# cpu.net
KiCad netlist of a schematic drawn in EAGLE
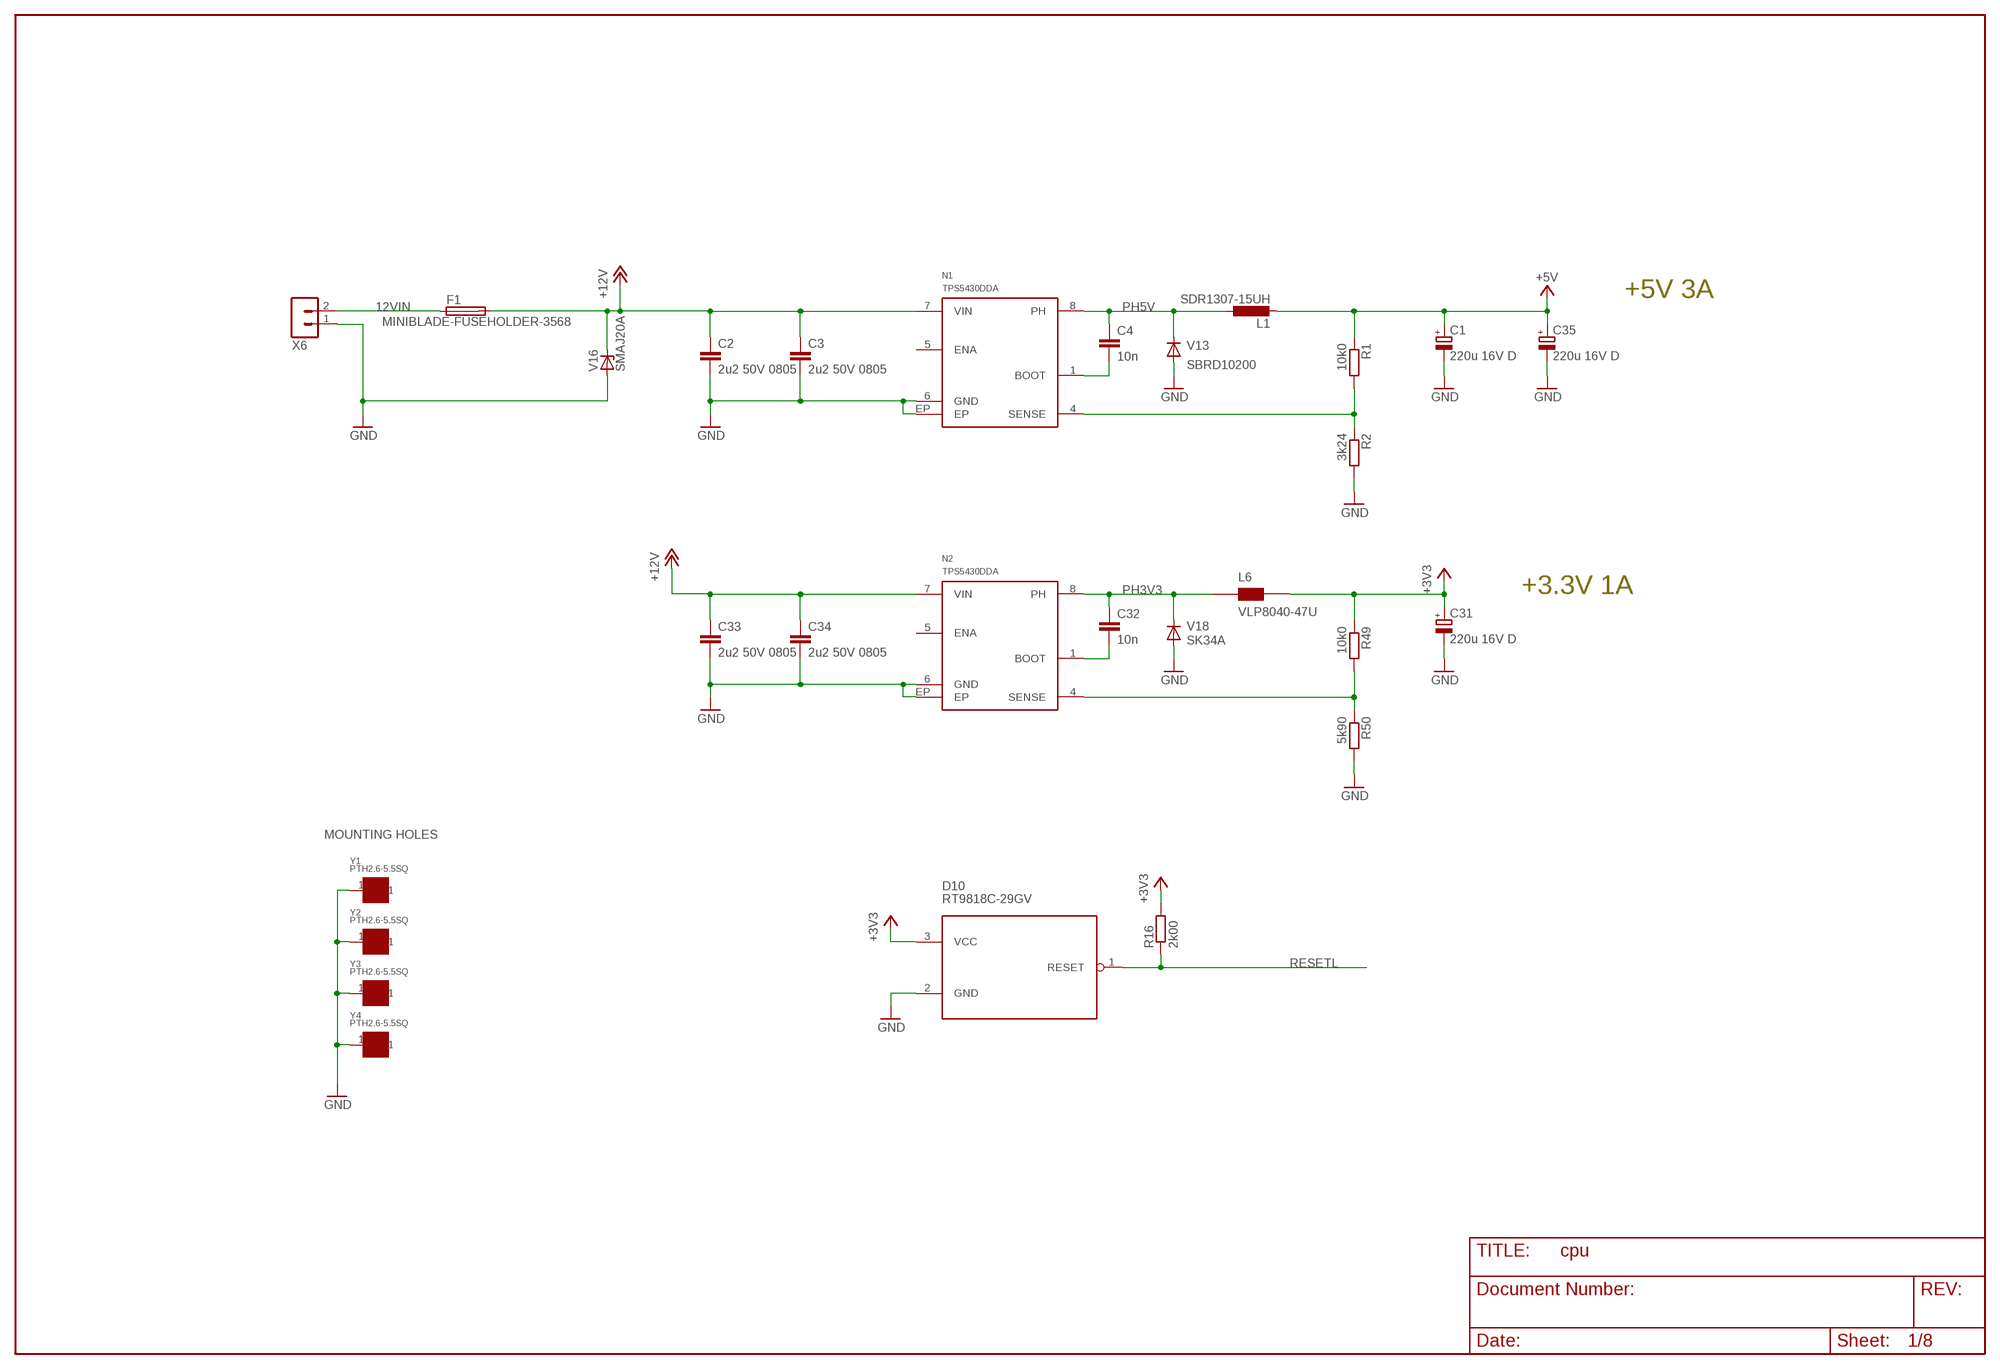
[diagram p0: schematic, sheet 1]
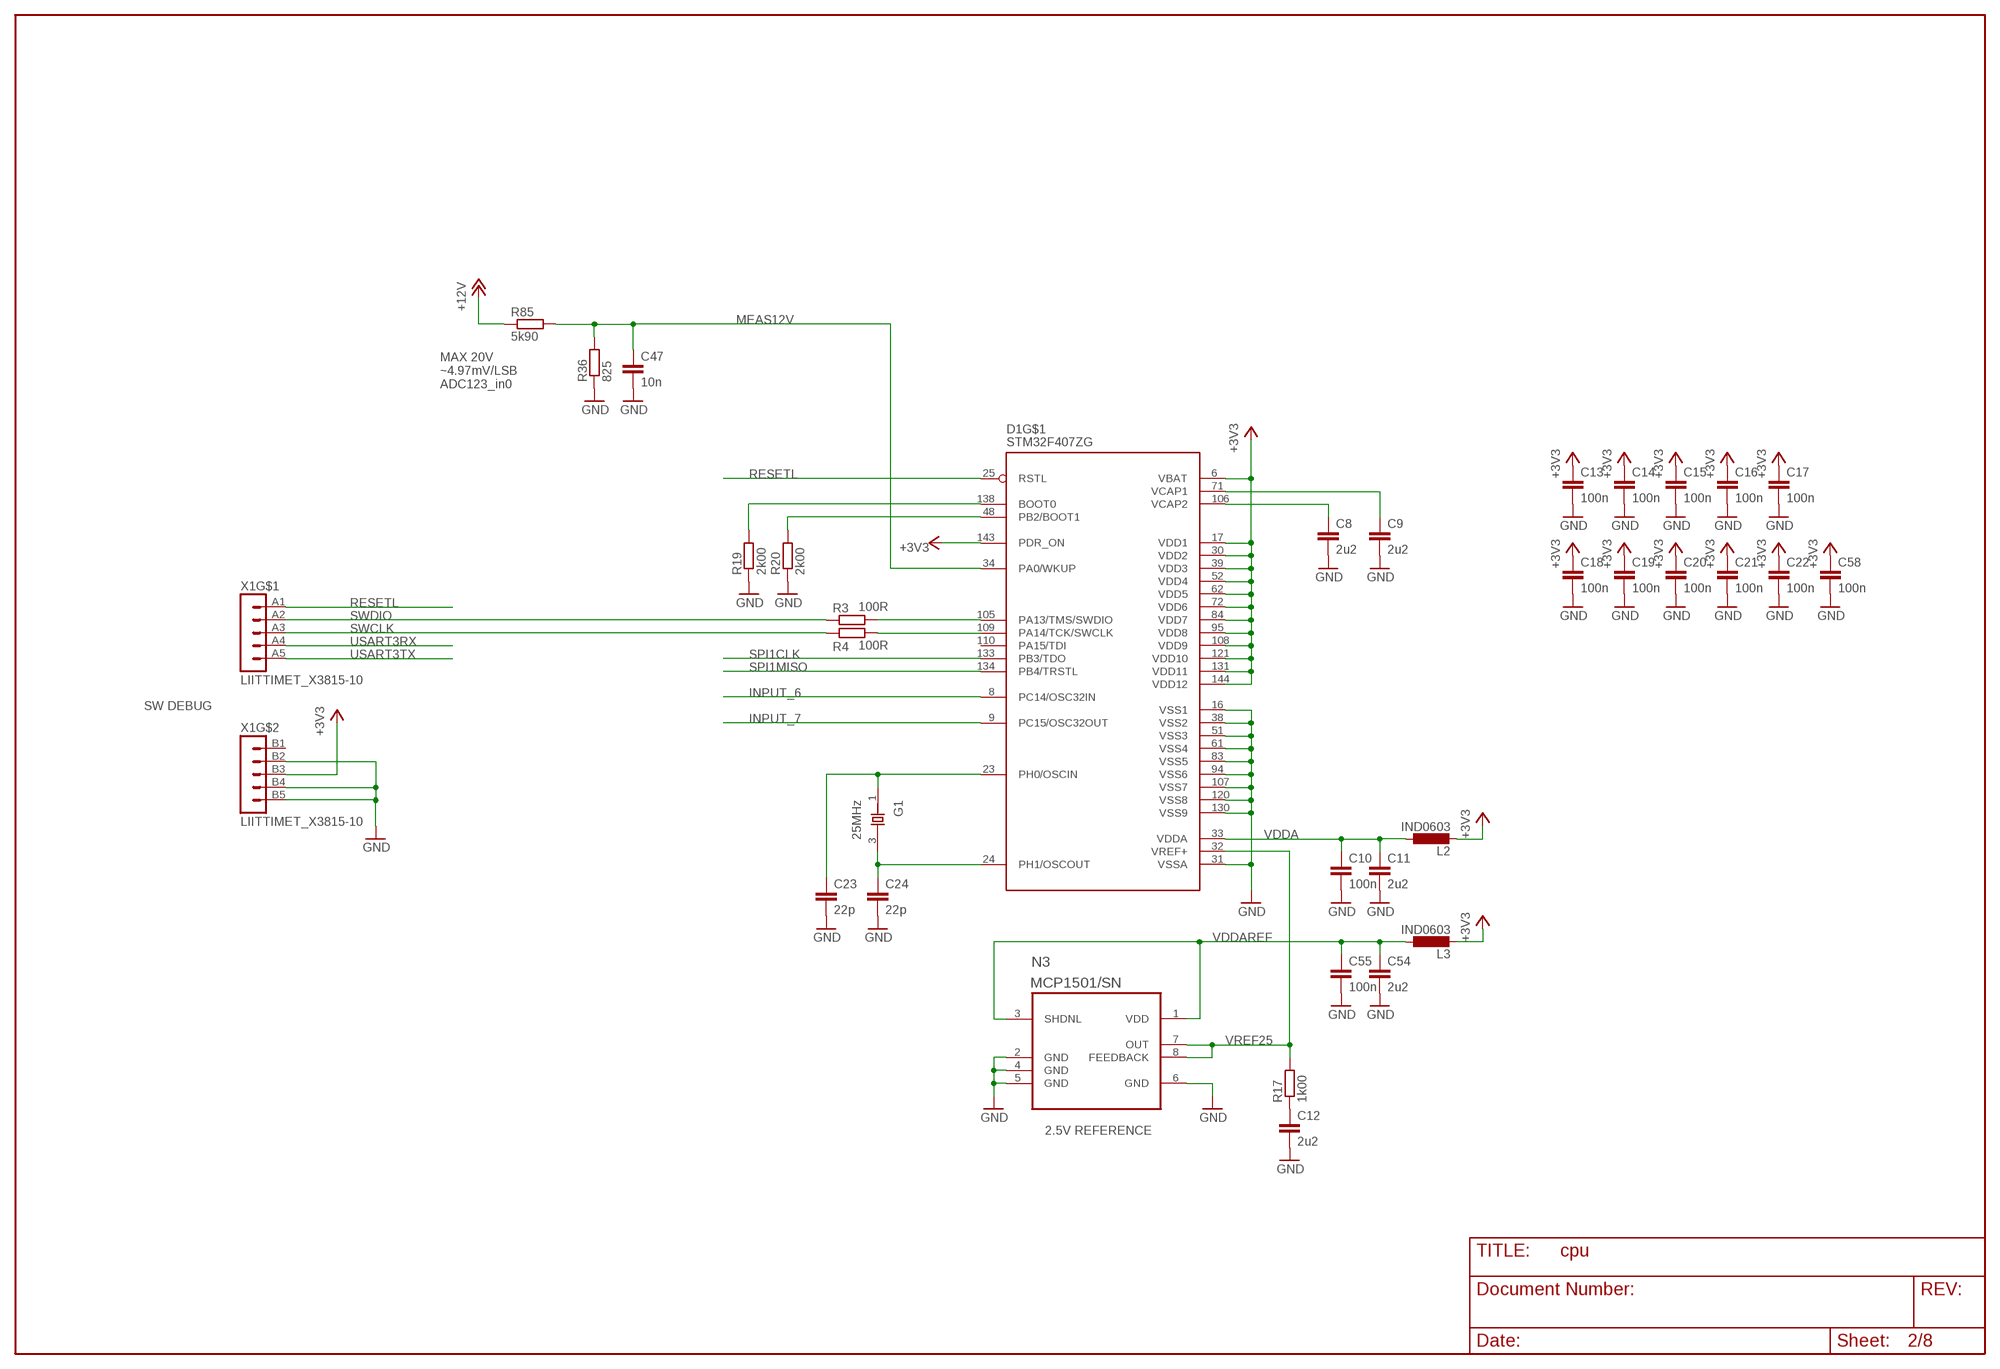
[diagram p1: schematic, sheet 2]
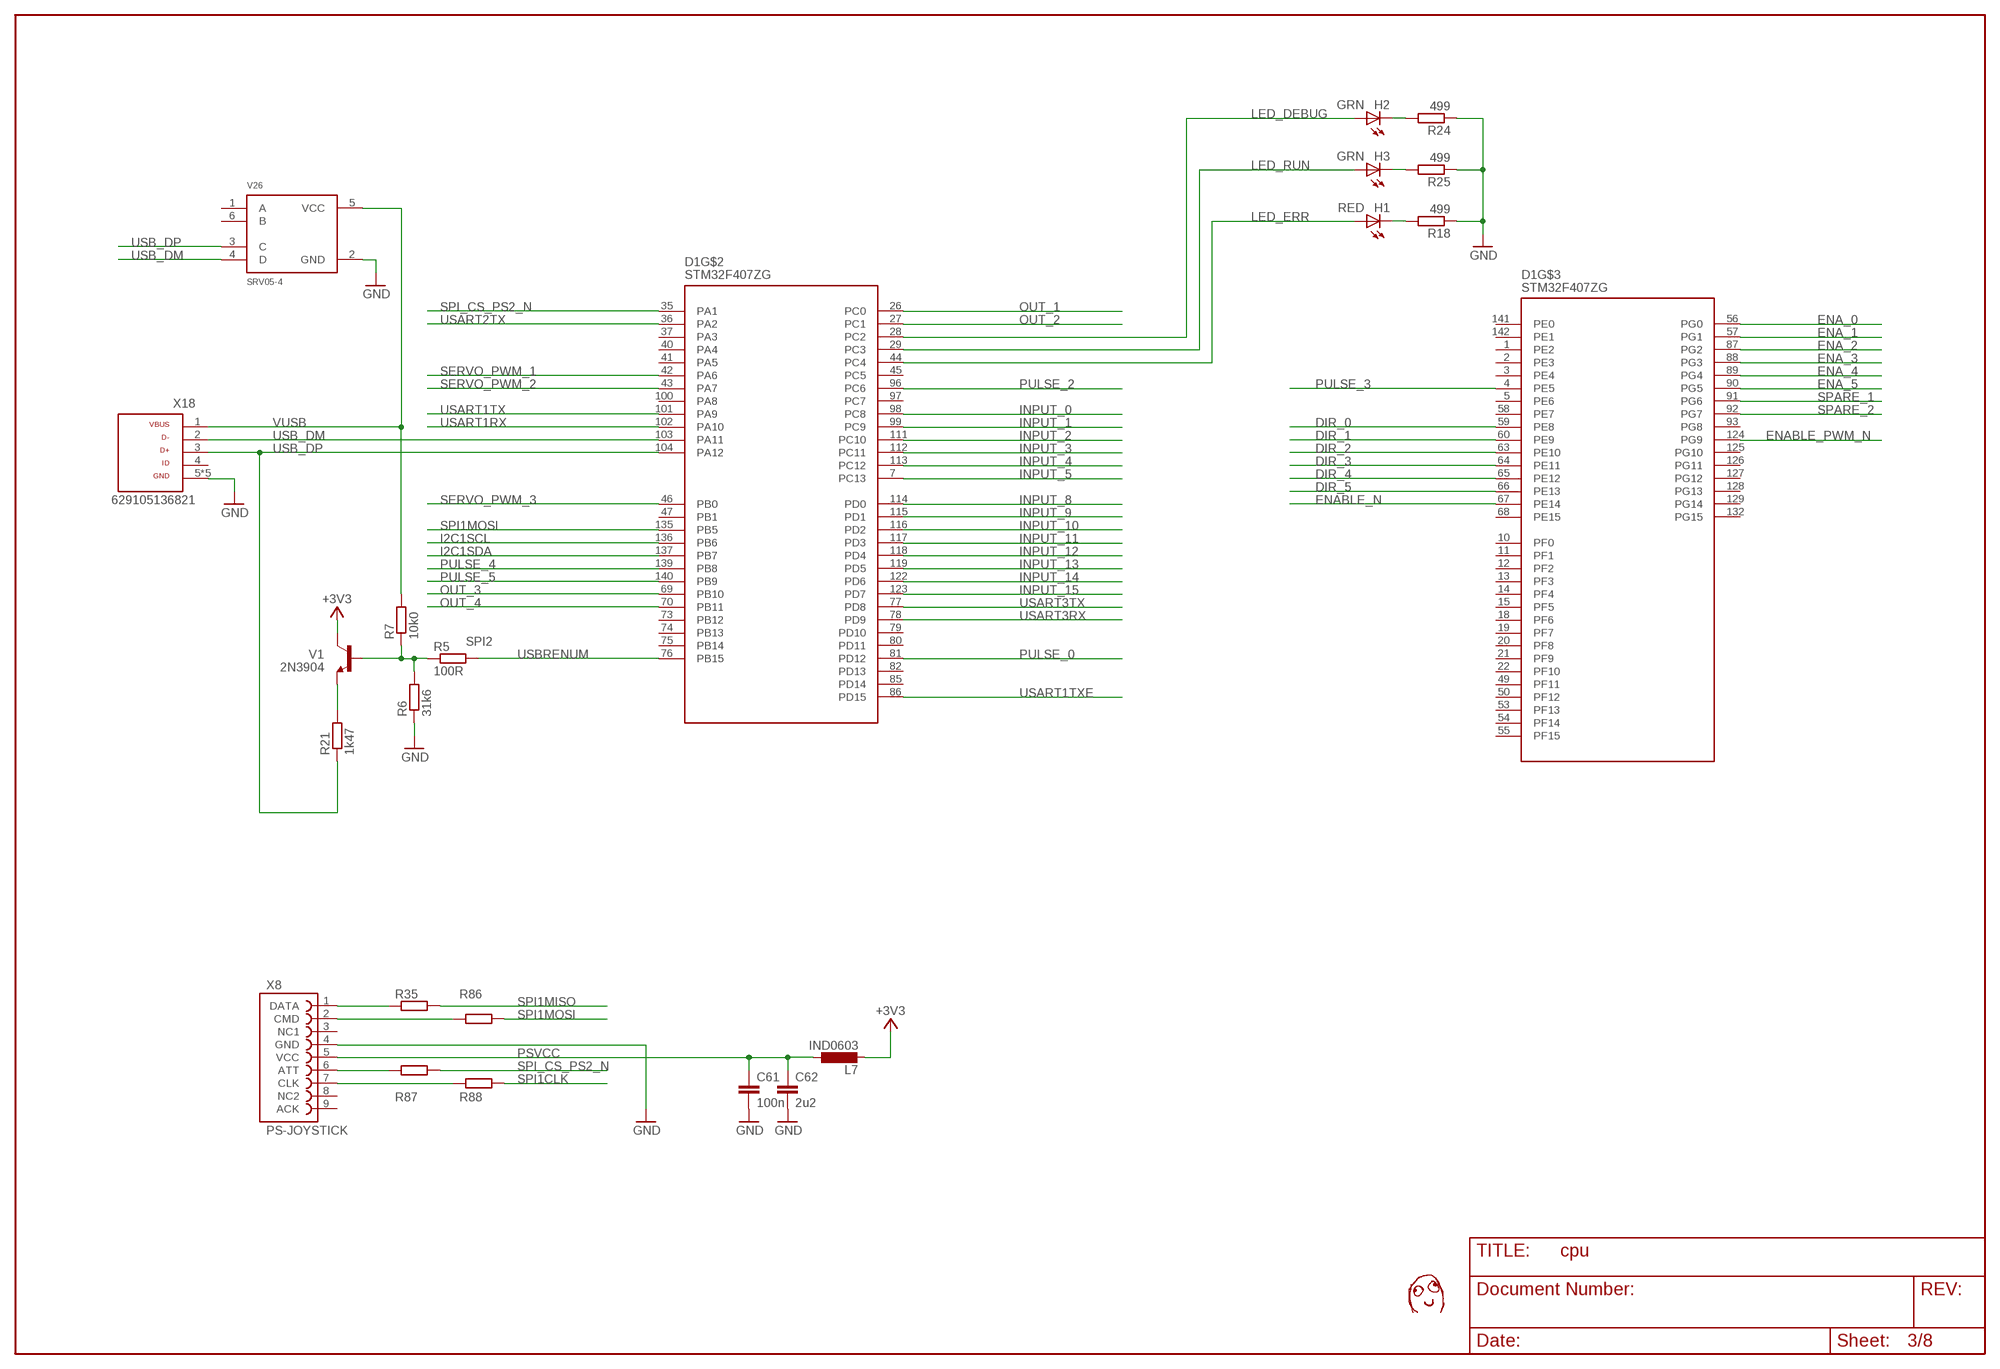
[diagram p2: schematic, sheet 3]
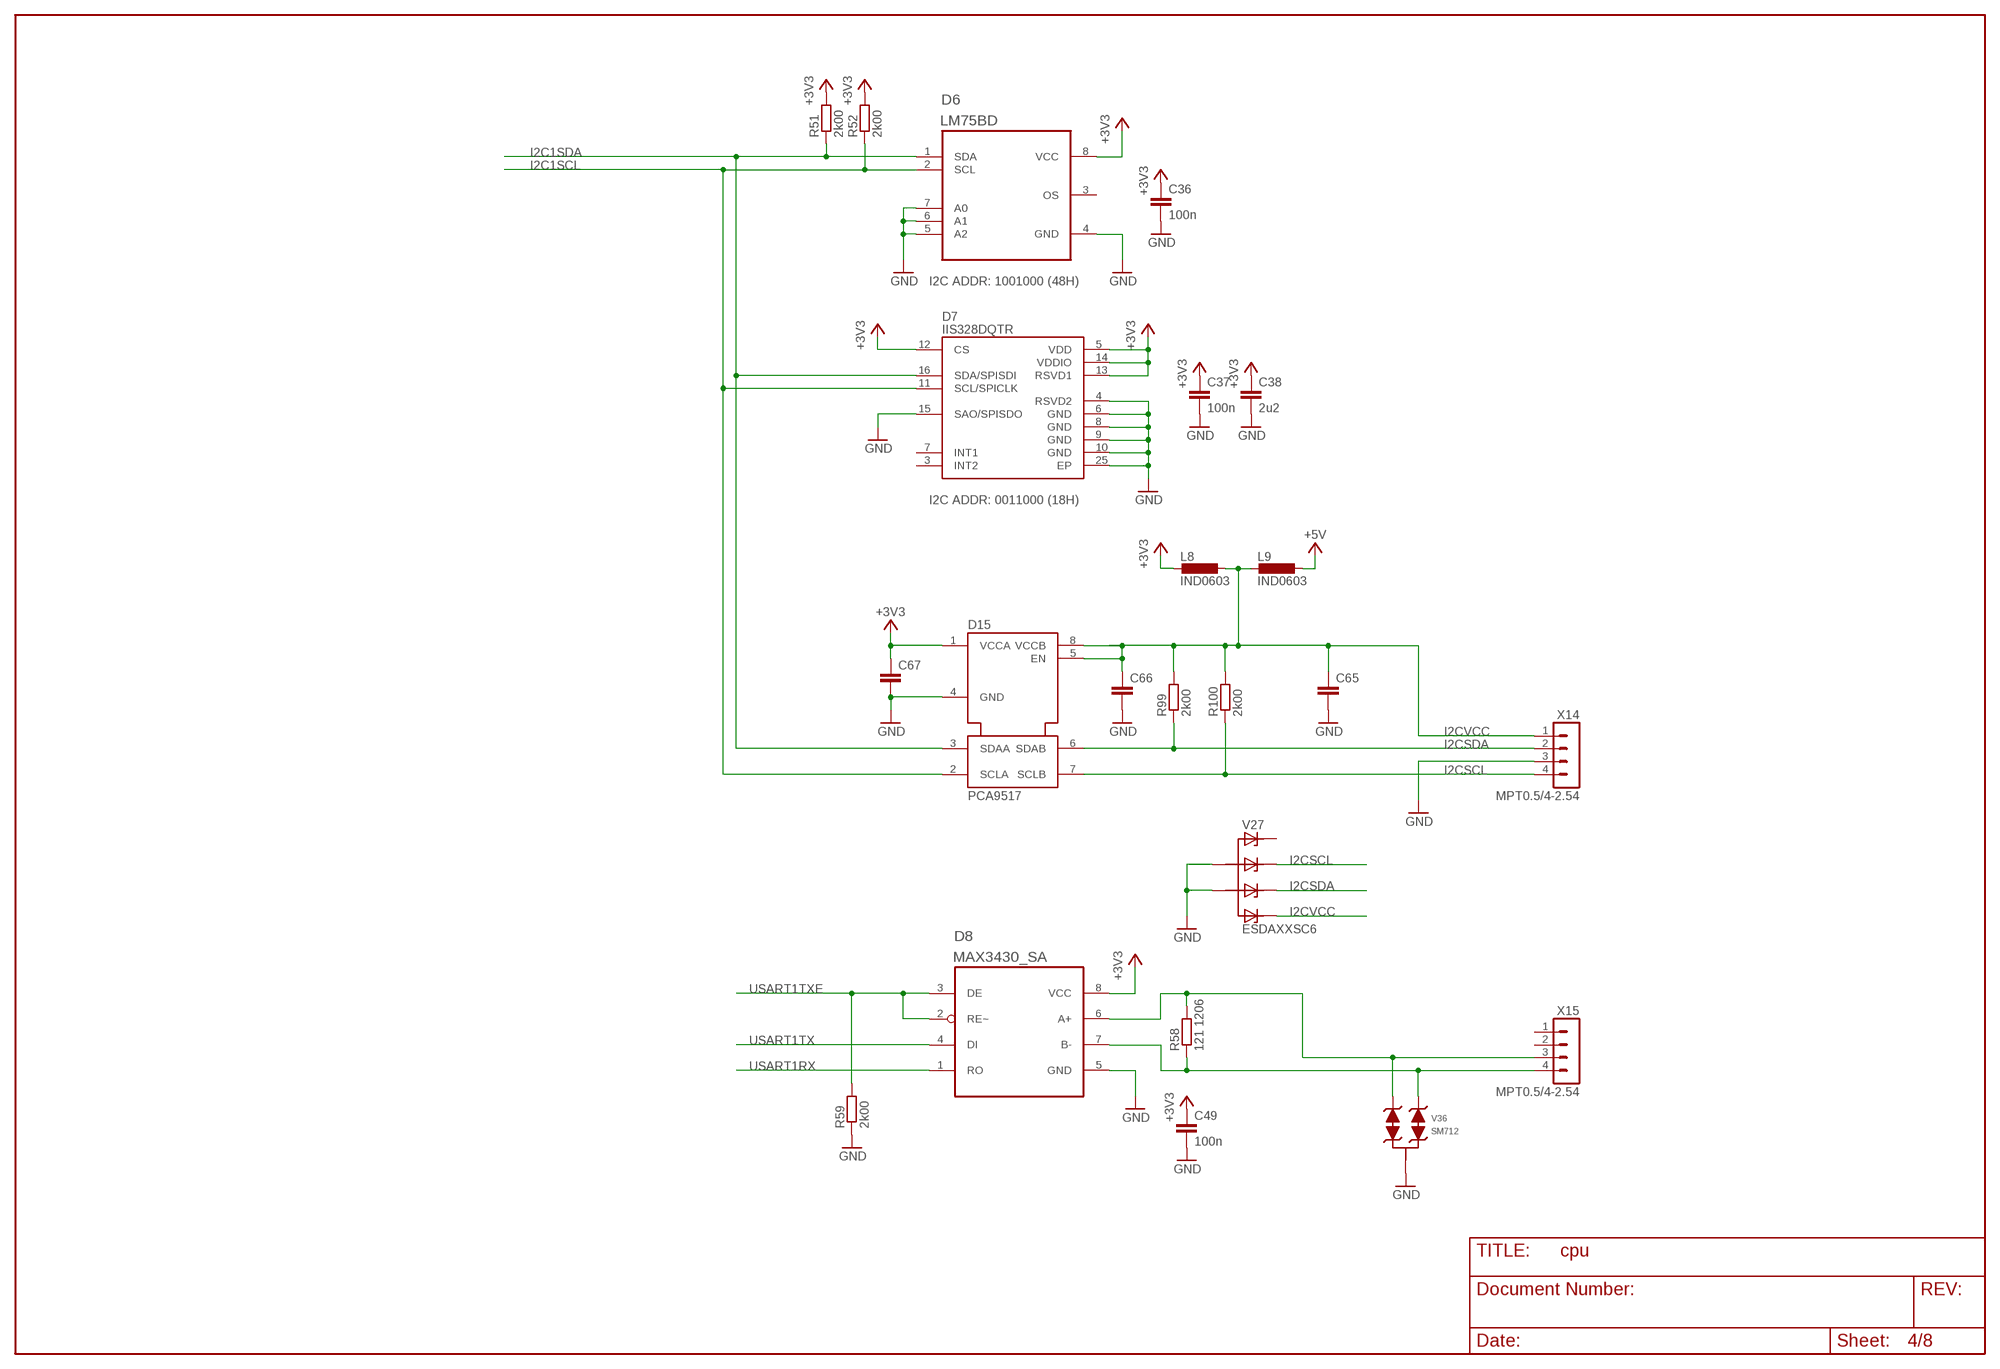
[diagram p3: schematic, sheet 4]
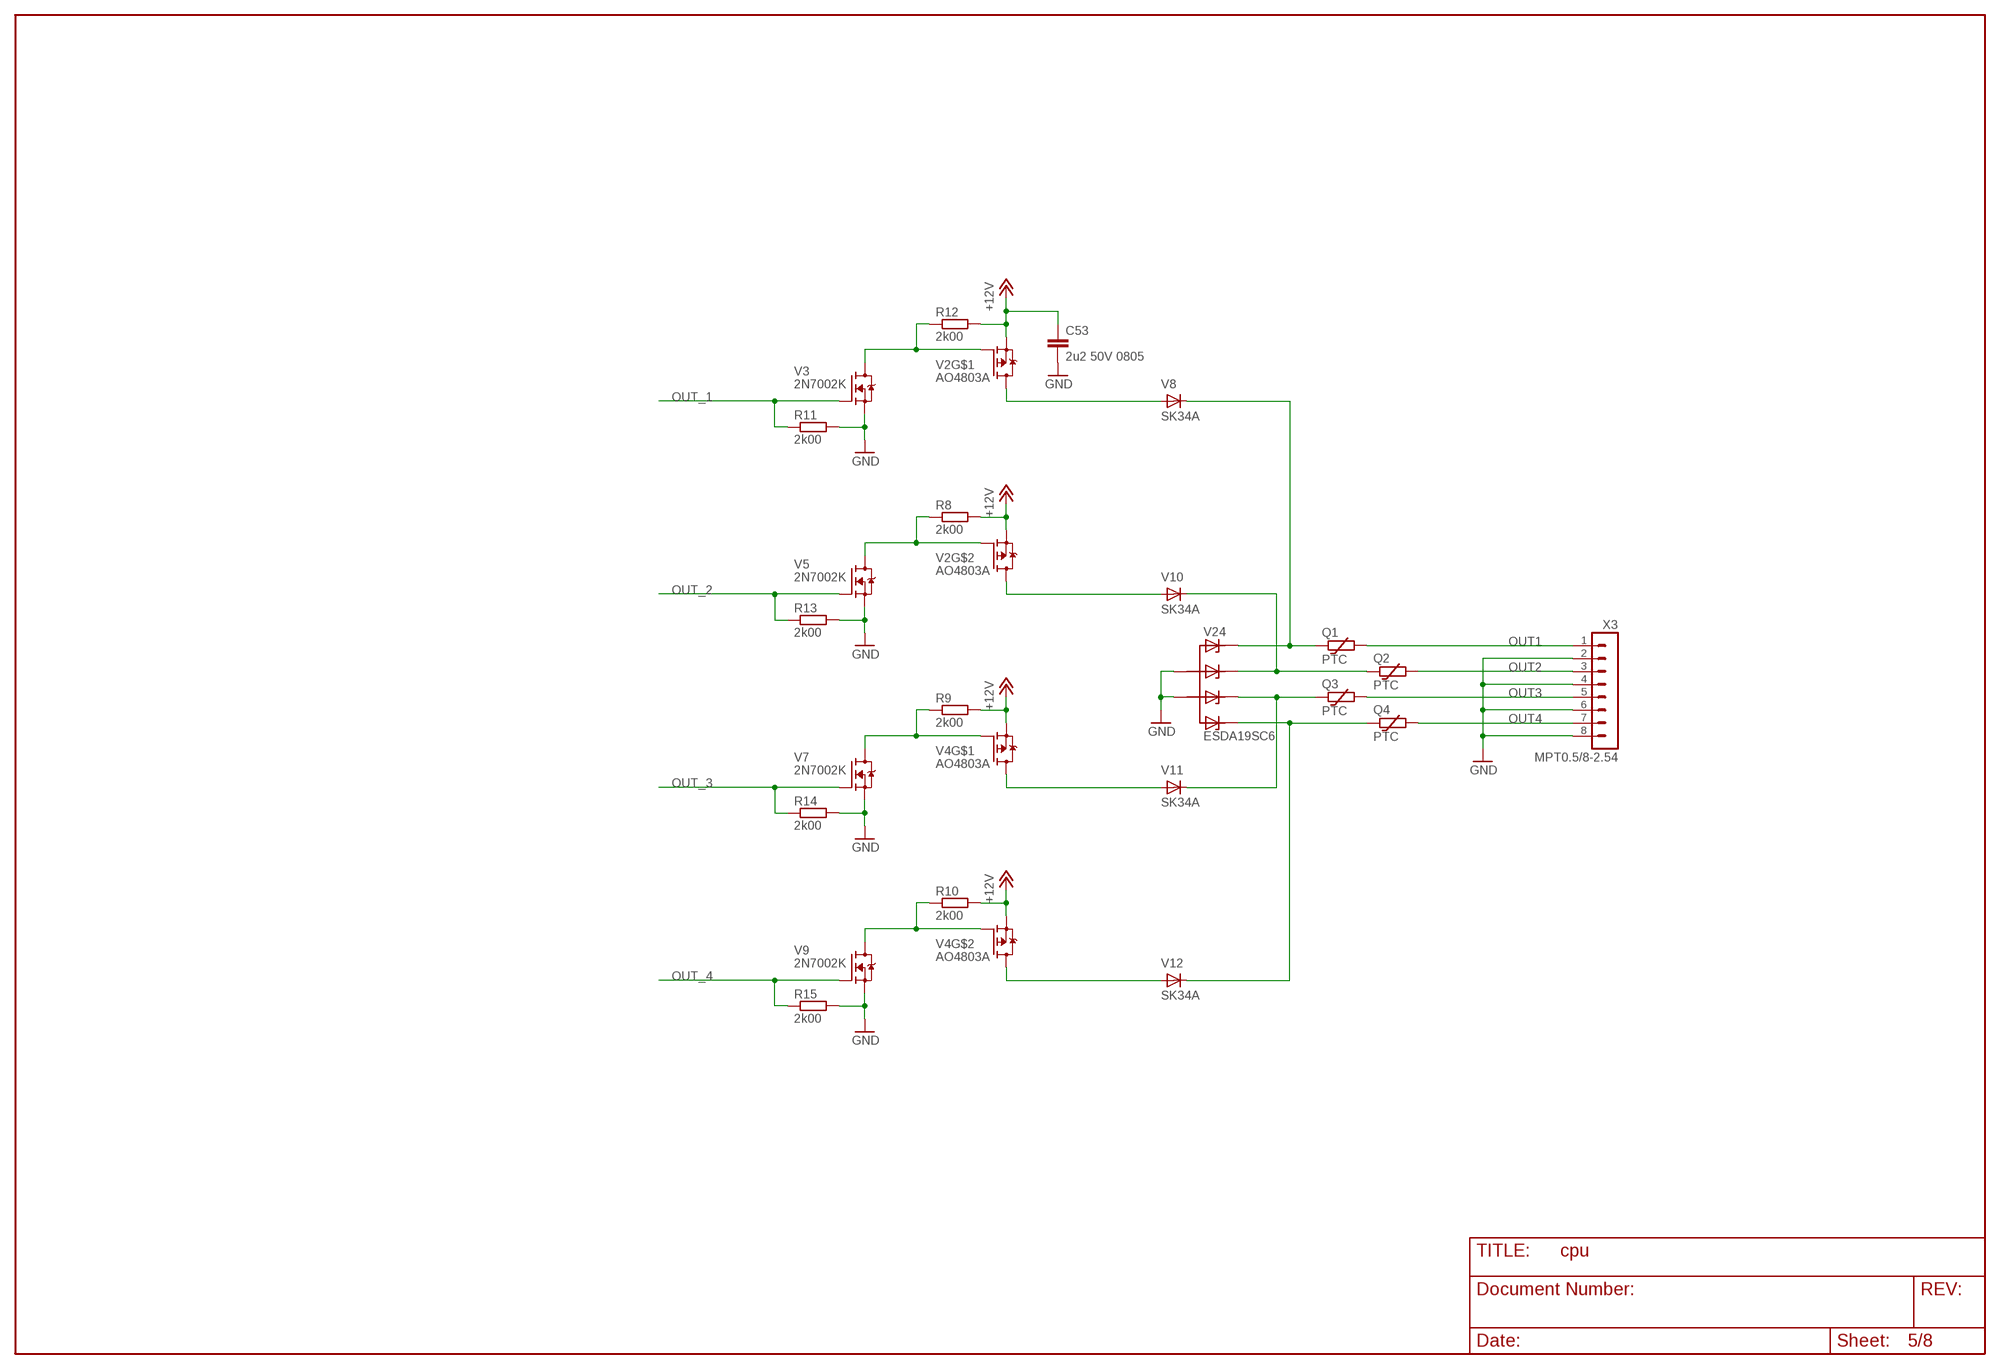
[diagram p4: schematic, sheet 5]
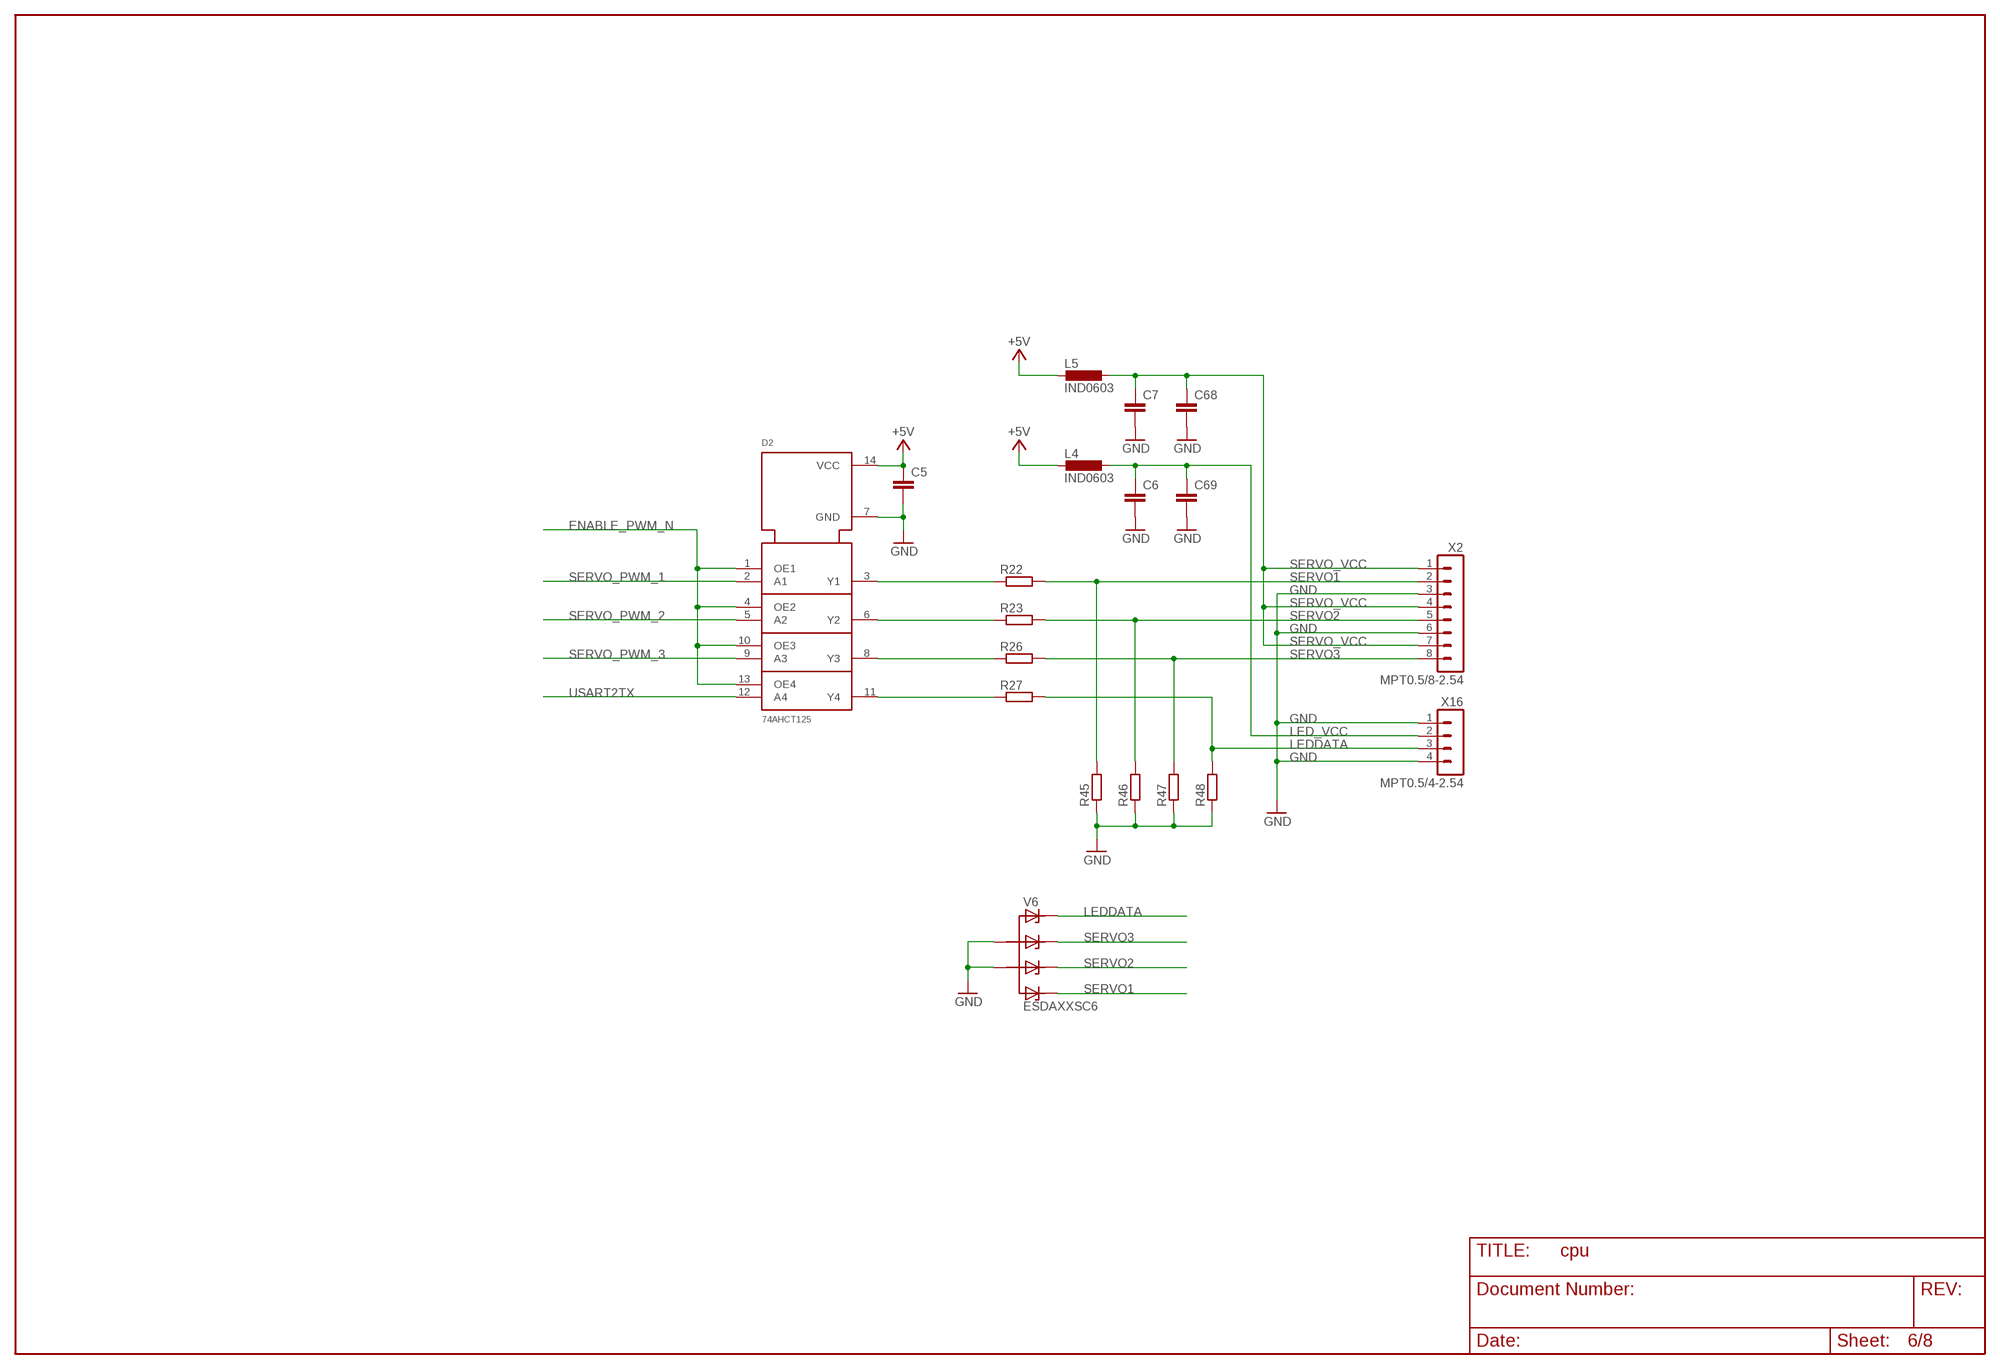
[diagram p5: schematic, sheet 6]
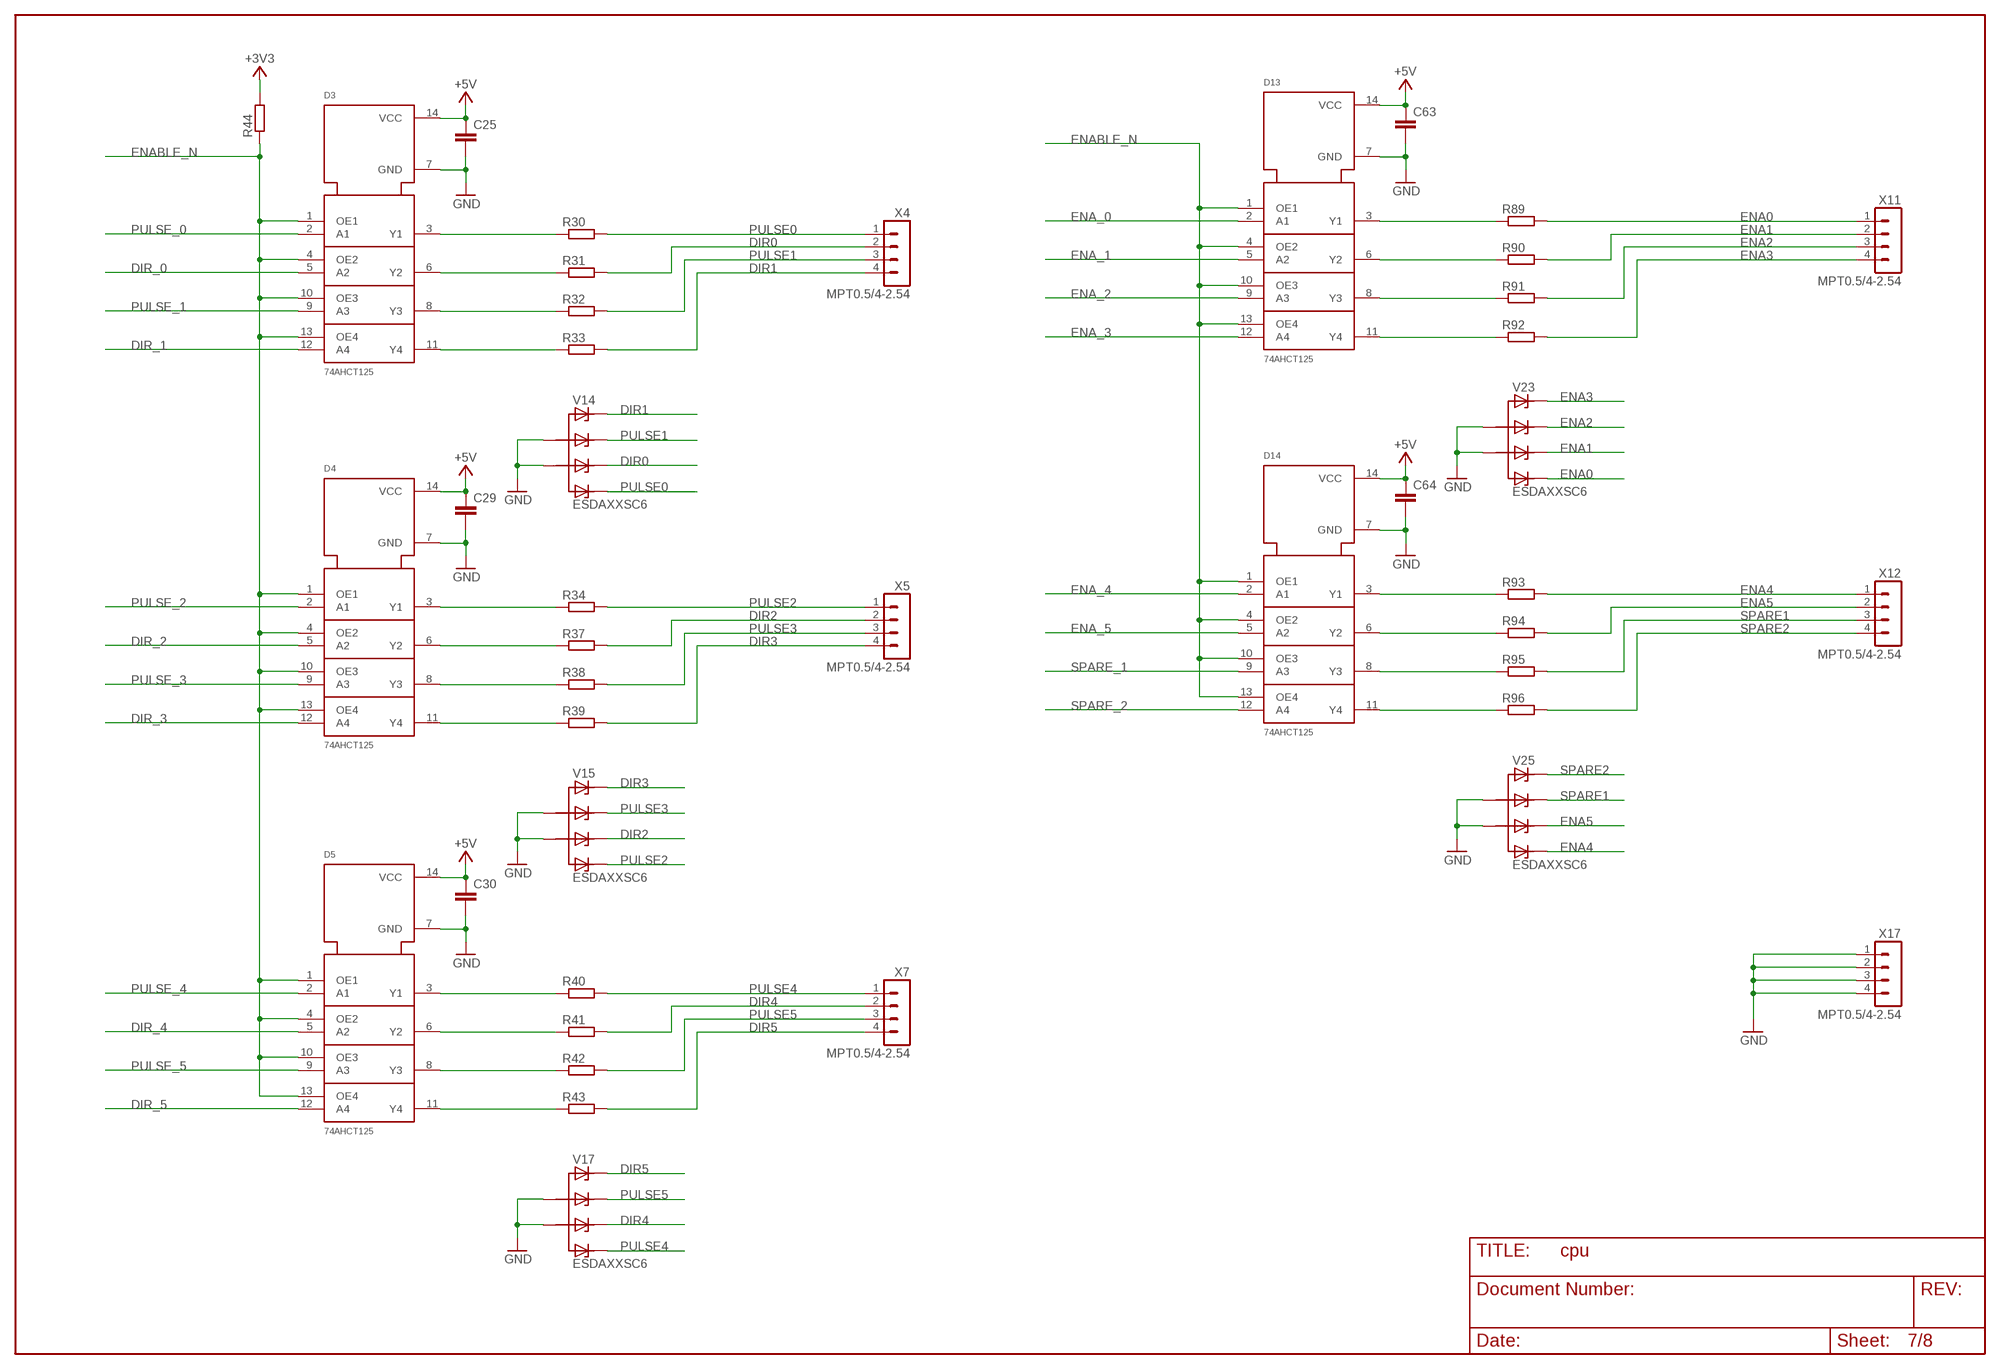
[diagram p6: schematic, sheet 7]
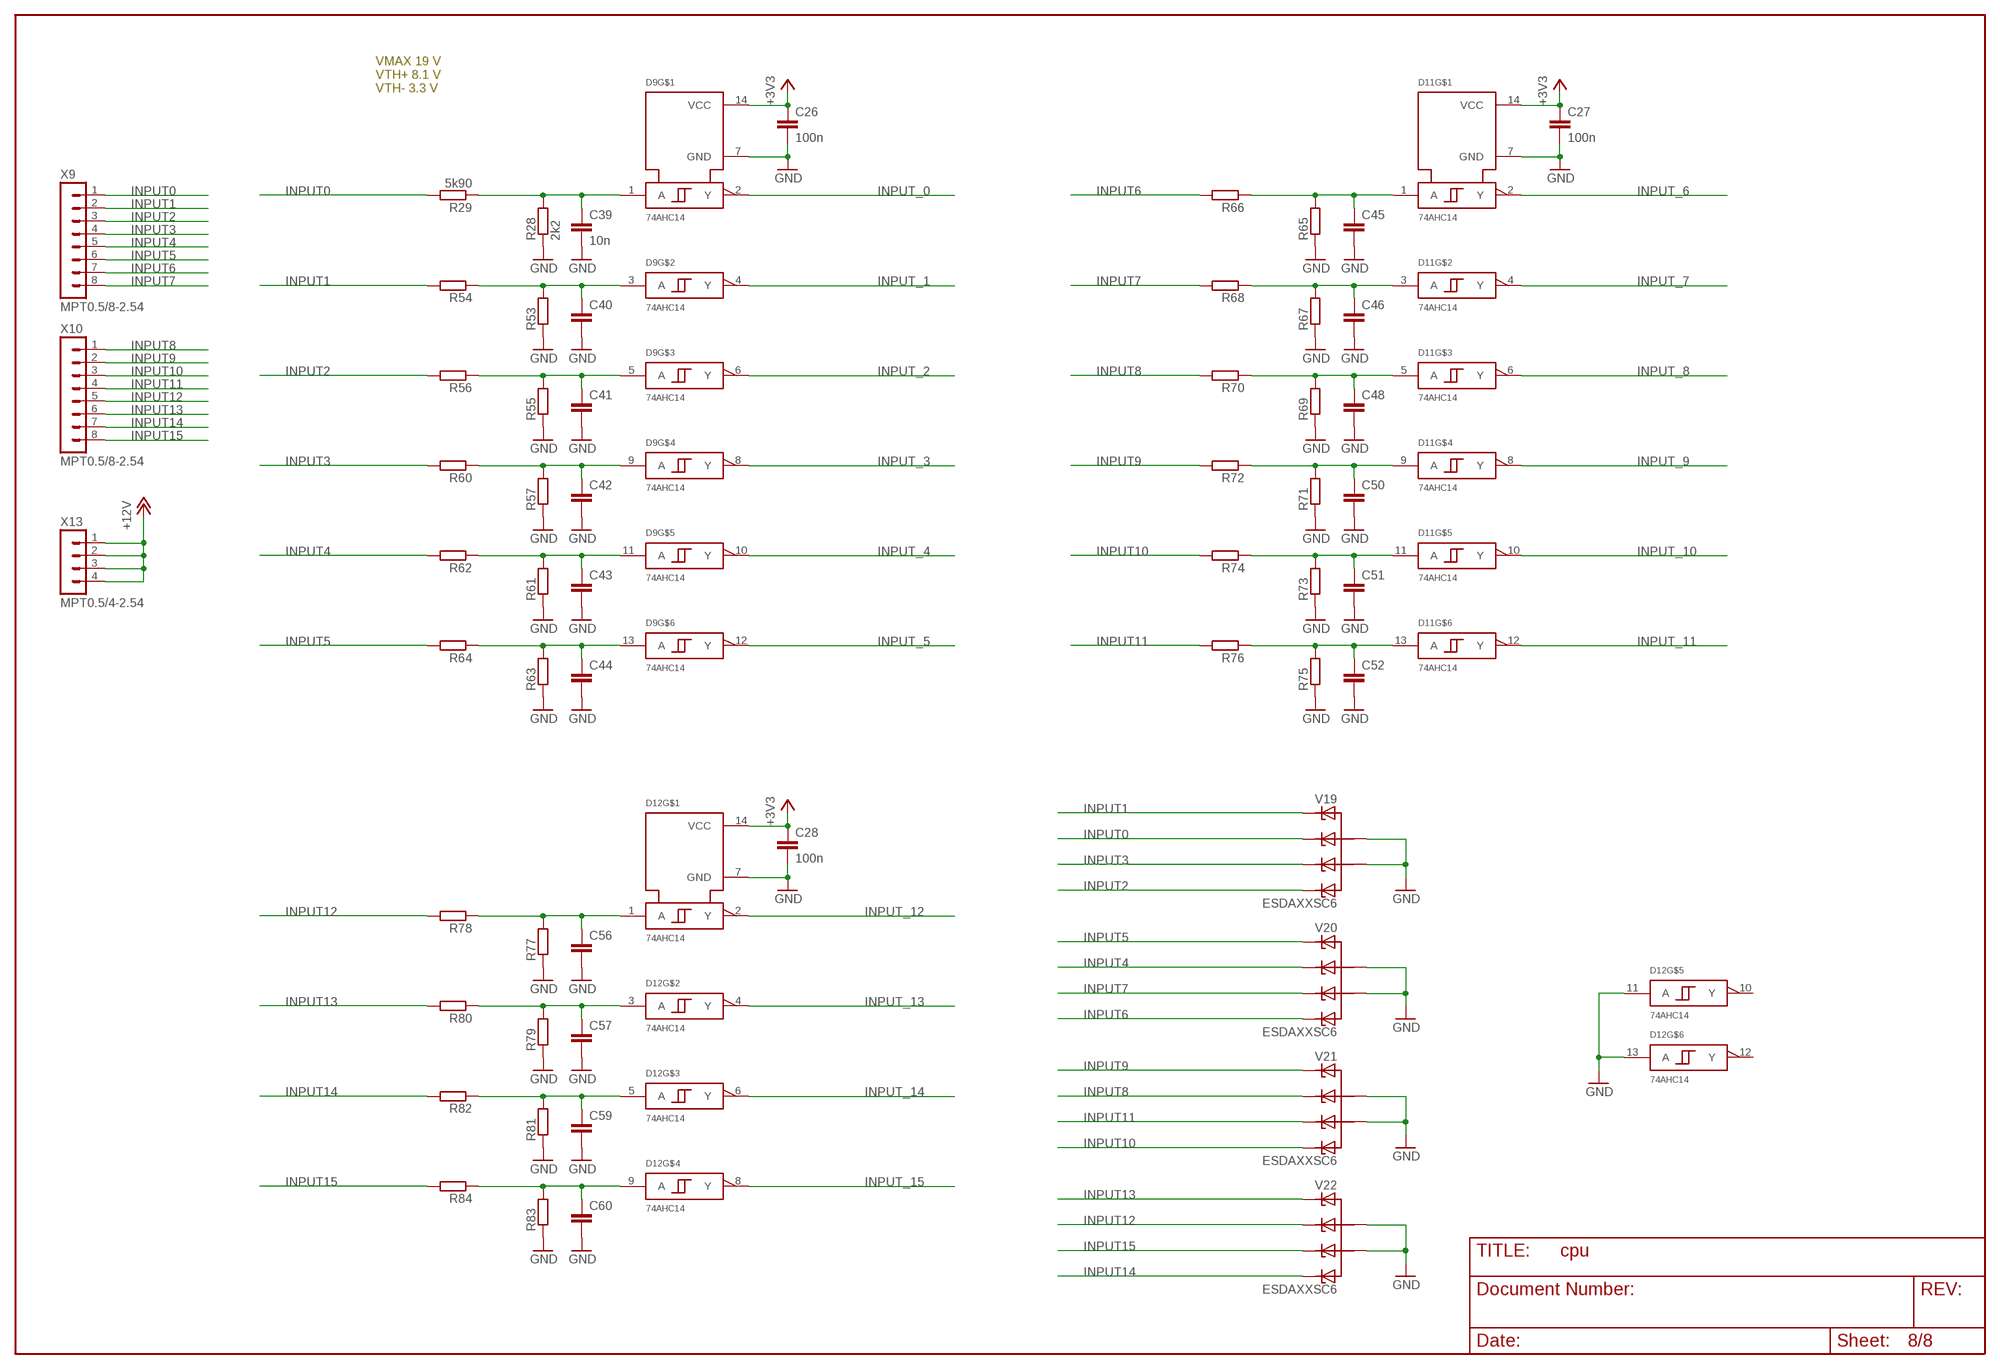
[diagram p7: schematic, sheet 8]

(export (version "E")
  (design (tool "Eeschema 10.0.6"))
  (components
    (comp (ref "C5")
      (value "CAP0603")
      (footprint "eagle-import:OMAT_IC_2_C0603")
      (libsource (lib "eagle-import") (part "CAP0603"))
    )
    (comp (ref "C6")
      (value "CAP0805")
      (footprint "eagle-import:OMAT_IC_2_C0805")
      (libsource (lib "eagle-import") (part "CAP0805"))
    )
    (comp (ref "C7")
      (value "CAP0805")
      (footprint "eagle-import:OMAT_IC_2_C0805")
      (libsource (lib "eagle-import") (part "CAP0805"))
    )
    (comp (ref "C68")
      (value "CAP0805")
      (footprint "eagle-import:OMAT_IC_2_C0805")
      (libsource (lib "eagle-import") (part "CAP0805"))
    )
    (comp (ref "C69")
      (value "CAP0805")
      (footprint "eagle-import:OMAT_IC_2_C0805")
      (libsource (lib "eagle-import") (part "CAP0805"))
    )
    (comp (ref "D2")
      (value "74AHCT125")
      (footprint "eagle-import:SO14")
      (libsource (lib "eagle-import") (part "74AHCT125"))
    )
    (comp (ref "L4")
      (value "IND0603")
      (footprint "eagle-import:OMAT_IC_2_R0603")
      (libsource (lib "eagle-import") (part "IND0603"))
    )
    (comp (ref "L5")
      (value "IND0603")
      (footprint "eagle-import:OMAT_IC_2_R0603")
      (libsource (lib "eagle-import") (part "IND0603"))
    )
    (comp (ref "R22")
      (value "RES0603")
      (footprint "eagle-import:OMAT_IC_2_R0603")
      (libsource (lib "eagle-import") (part "RES0603"))
    )
    (comp (ref "R23")
      (value "RES0603")
      (footprint "eagle-import:OMAT_IC_2_R0603")
      (libsource (lib "eagle-import") (part "RES0603"))
    )
    (comp (ref "R26")
      (value "RES0603")
      (footprint "eagle-import:OMAT_IC_2_R0603")
      (libsource (lib "eagle-import") (part "RES0603"))
    )
    (comp (ref "R27")
      (value "RES0603")
      (footprint "eagle-import:OMAT_IC_2_R0603")
      (libsource (lib "eagle-import") (part "RES0603"))
    )
    (comp (ref "R45")
      (value "RES0603")
      (footprint "eagle-import:OMAT_IC_2_R0603")
      (libsource (lib "eagle-import") (part "RES0603"))
    )
    (comp (ref "R46")
      (value "RES0603")
      (footprint "eagle-import:OMAT_IC_2_R0603")
      (libsource (lib "eagle-import") (part "RES0603"))
    )
    (comp (ref "R47")
      (value "RES0603")
      (footprint "eagle-import:OMAT_IC_2_R0603")
      (libsource (lib "eagle-import") (part "RES0603"))
    )
    (comp (ref "R48")
      (value "RES0603")
      (footprint "eagle-import:OMAT_IC_2_R0603")
      (libsource (lib "eagle-import") (part "RES0603"))
    )
    (comp (ref "V6")
      (value "ESDAXXSC6")
      (footprint "eagle-import:OMAT_IC_2_SOT23-6")
      (libsource (lib "eagle-import") (part "ESDAXXSC6"))
    )
    (comp (ref "X2")
      (value "MPT0.5/8-2.54")
      (footprint "eagle-import:OMAT_IC_2_MPT0.5_8-2.54")
      (libsource (lib "eagle-import") (part "MPT0.5/8-2.54"))
    )
    (comp (ref "X16")
      (value "MPT0.5/4-2.54")
      (footprint "eagle-import:MPT0.5_4-2.54")
      (libsource (lib "eagle-import") (part "MPT0.5/4-2.54"))
    )
    (comp (ref "C8")
      (value "2u2")
      (footprint "eagle-import:C0603")
      (libsource (lib "eagle-import") (part "omat_ic_2_CAP0603"))
    )
    (comp (ref "C9")
      (value "2u2")
      (footprint "eagle-import:C0603")
      (libsource (lib "eagle-import") (part "omat_ic_2_CAP0603"))
    )
    (comp (ref "C10")
      (value "100n")
      (footprint "eagle-import:C0603")
      (libsource (lib "eagle-import") (part "omat_ic_2_CAP0603"))
    )
    (comp (ref "C11")
      (value "2u2")
      (footprint "eagle-import:C0603")
      (libsource (lib "eagle-import") (part "omat_ic_2_CAP0603"))
    )
    (comp (ref "C12")
      (value "2u2")
      (footprint "eagle-import:C0603")
      (libsource (lib "eagle-import") (part "omat_ic_2_CAP0603"))
    )
    (comp (ref "C13")
      (value "100n")
      (footprint "eagle-import:C0603")
      (libsource (lib "eagle-import") (part "omat_ic_2_CAP0603"))
    )
    (comp (ref "C14")
      (value "100n")
      (footprint "eagle-import:C0603")
      (libsource (lib "eagle-import") (part "omat_ic_2_CAP0603"))
    )
    (comp (ref "C15")
      (value "100n")
      (footprint "eagle-import:C0603")
      (libsource (lib "eagle-import") (part "omat_ic_2_CAP0603"))
    )
    (comp (ref "C16")
      (value "100n")
      (footprint "eagle-import:C0603")
      (libsource (lib "eagle-import") (part "omat_ic_2_CAP0603"))
    )
    (comp (ref "C17")
      (value "100n")
      (footprint "eagle-import:C0603")
      (libsource (lib "eagle-import") (part "omat_ic_2_CAP0603"))
    )
    (comp (ref "C18")
      (value "100n")
      (footprint "eagle-import:C0603")
      (libsource (lib "eagle-import") (part "omat_ic_2_CAP0603"))
    )
    (comp (ref "C19")
      (value "100n")
      (footprint "eagle-import:C0603")
      (libsource (lib "eagle-import") (part "omat_ic_2_CAP0603"))
    )
    (comp (ref "C20")
      (value "100n")
      (footprint "eagle-import:C0603")
      (libsource (lib "eagle-import") (part "omat_ic_2_CAP0603"))
    )
    (comp (ref "C21")
      (value "100n")
      (footprint "eagle-import:C0603")
      (libsource (lib "eagle-import") (part "omat_ic_2_CAP0603"))
    )
    (comp (ref "C22")
      (value "100n")
      (footprint "eagle-import:C0603")
      (libsource (lib "eagle-import") (part "omat_ic_2_CAP0603"))
    )
    (comp (ref "C23")
      (value "22p")
      (footprint "eagle-import:C0603")
      (libsource (lib "eagle-import") (part "omat_ic_2_CAP0603"))
    )
    (comp (ref "C24")
      (value "22p")
      (footprint "eagle-import:C0603")
      (libsource (lib "eagle-import") (part "omat_ic_2_CAP0603"))
    )
    (comp (ref "C47")
      (value "10n")
      (footprint "eagle-import:C0603")
      (libsource (lib "eagle-import") (part "omat_ic_2_CAP0603"))
    )
    (comp (ref "C54")
      (value "2u2")
      (footprint "eagle-import:C0603")
      (libsource (lib "eagle-import") (part "omat_ic_2_CAP0603"))
    )
    (comp (ref "C55")
      (value "100n")
      (footprint "eagle-import:C0603")
      (libsource (lib "eagle-import") (part "omat_ic_2_CAP0603"))
    )
    (comp (ref "C58")
      (value "100n")
      (footprint "eagle-import:C0603")
      (libsource (lib "eagle-import") (part "omat_ic_2_CAP0603"))
    )
    (comp (ref "D1")
      (value "STM32F407ZG")
      (footprint "eagle-import:LQFP-144")
      (libsource (lib "eagle-import") (part "STM32F407ZG"))
    )
    (comp (ref "G1")
      (value "25MHz")
      (footprint "eagle-import:X_3225")
      (libsource (lib "eagle-import") (part "XTAL_3225_SMD"))
    )
    (comp (ref "L2")
      (value "IND0603")
      (footprint "eagle-import:R0603")
      (libsource (lib "eagle-import") (part "omat_ic_2_IND0603"))
    )
    (comp (ref "L3")
      (value "IND0603")
      (footprint "eagle-import:R0603")
      (libsource (lib "eagle-import") (part "omat_ic_2_IND0603"))
    )
    (comp (ref "N3")
      (value "MCP1501/SN")
      (footprint "eagle-import:SOIC8-N_MC")
      (libsource (lib "eagle-import") (part "MCP1501/SN"))
    )
    (comp (ref "R3")
      (value "100R")
      (footprint "eagle-import:PASSIIVIT_R0603")
      (libsource (lib "eagle-import") (part "PASSIIVIT_RES0603"))
    )
    (comp (ref "R4")
      (value "100R")
      (footprint "eagle-import:PASSIIVIT_R0603")
      (libsource (lib "eagle-import") (part "PASSIIVIT_RES0603"))
    )
    (comp (ref "R17")
      (value "1k00")
      (footprint "eagle-import:R0603")
      (libsource (lib "eagle-import") (part "omat_ic_2_RES0603"))
    )
    (comp (ref "R19")
      (value "2k00")
      (footprint "eagle-import:R0603")
      (libsource (lib "eagle-import") (part "omat_ic_2_RES0603"))
    )
    (comp (ref "R20")
      (value "2k00")
      (footprint "eagle-import:R0603")
      (libsource (lib "eagle-import") (part "omat_ic_2_RES0603"))
    )
    (comp (ref "R36")
      (value "825")
      (footprint "eagle-import:R0603")
      (libsource (lib "eagle-import") (part "omat_ic_2_RES0603"))
    )
    (comp (ref "R85")
      (value "5k90")
      (footprint "eagle-import:R0603")
      (libsource (lib "eagle-import") (part "omat_ic_2_RES0603"))
    )
    (comp (ref "X1")
      (value "LIITTIMET_X3815-10")
      (footprint "eagle-import:LIITTIMET_15110102601")
      (libsource (lib "eagle-import") (part "LIITTIMET_X3815-10"))
    )
    (comp (ref "C53")
      (value "2u2 50V 0805")
      (footprint "eagle-import:C0805")
      (libsource (lib "eagle-import") (part "omat_ic_2_CAP0805"))
    )
    (comp (ref "Q1")
      (value "PTC")
      (footprint "eagle-import:OMAT_IC_2_R1812")
      (libsource (lib "eagle-import") (part "PTC"))
    )
    (comp (ref "Q2")
      (value "PTC")
      (footprint "eagle-import:OMAT_IC_2_R1812")
      (libsource (lib "eagle-import") (part "PTC"))
    )
    (comp (ref "Q3")
      (value "PTC")
      (footprint "eagle-import:OMAT_IC_2_R1812")
      (libsource (lib "eagle-import") (part "PTC"))
    )
    (comp (ref "Q4")
      (value "PTC")
      (footprint "eagle-import:OMAT_IC_2_R1812")
      (libsource (lib "eagle-import") (part "PTC"))
    )
    (comp (ref "R8")
      (value "2k00")
      (footprint "eagle-import:R0603")
      (libsource (lib "eagle-import") (part "omat_ic_2_RES0603"))
    )
    (comp (ref "R9")
      (value "2k00")
      (footprint "eagle-import:R0603")
      (libsource (lib "eagle-import") (part "omat_ic_2_RES0603"))
    )
    (comp (ref "R10")
      (value "2k00")
      (footprint "eagle-import:R0603")
      (libsource (lib "eagle-import") (part "omat_ic_2_RES0603"))
    )
    (comp (ref "R11")
      (value "2k00")
      (footprint "eagle-import:R0603")
      (libsource (lib "eagle-import") (part "omat_ic_2_RES0603"))
    )
    (comp (ref "R12")
      (value "2k00")
      (footprint "eagle-import:R0603")
      (libsource (lib "eagle-import") (part "omat_ic_2_RES0603"))
    )
    (comp (ref "R13")
      (value "2k00")
      (footprint "eagle-import:R0603")
      (libsource (lib "eagle-import") (part "omat_ic_2_RES0603"))
    )
    (comp (ref "R14")
      (value "2k00")
      (footprint "eagle-import:R0603")
      (libsource (lib "eagle-import") (part "omat_ic_2_RES0603"))
    )
    (comp (ref "R15")
      (value "2k00")
      (footprint "eagle-import:R0603")
      (libsource (lib "eagle-import") (part "omat_ic_2_RES0603"))
    )
    (comp (ref "V2")
      (value "AO4803A")
      (footprint "eagle-import:SOIC8-N_MC")
      (libsource (lib "eagle-import") (part "AO4803A"))
    )
    (comp (ref "V3")
      (value "2N7002K")
      (footprint "eagle-import:SOT23")
      (libsource (lib "eagle-import") (part "2N7002K"))
    )
    (comp (ref "V4")
      (value "AO4803A")
      (footprint "eagle-import:SOIC8-N_MC")
      (libsource (lib "eagle-import") (part "AO4803A"))
    )
    (comp (ref "V5")
      (value "2N7002K")
      (footprint "eagle-import:SOT23")
      (libsource (lib "eagle-import") (part "2N7002K"))
    )
    (comp (ref "V7")
      (value "2N7002K")
      (footprint "eagle-import:SOT23")
      (libsource (lib "eagle-import") (part "2N7002K"))
    )
    (comp (ref "V8")
      (value "SK34A")
      (footprint "eagle-import:DO214AC")
      (libsource (lib "eagle-import") (part "SK34A"))
    )
    (comp (ref "V9")
      (value "2N7002K")
      (footprint "eagle-import:SOT23")
      (libsource (lib "eagle-import") (part "2N7002K"))
    )
    (comp (ref "V10")
      (value "SK34A")
      (footprint "eagle-import:DO214AC")
      (libsource (lib "eagle-import") (part "SK34A"))
    )
    (comp (ref "V11")
      (value "SK34A")
      (footprint "eagle-import:DO214AC")
      (libsource (lib "eagle-import") (part "SK34A"))
    )
    (comp (ref "V12")
      (value "SK34A")
      (footprint "eagle-import:DO214AC")
      (libsource (lib "eagle-import") (part "SK34A"))
    )
    (comp (ref "V24")
      (value "ESDA19SC6")
      (footprint "eagle-import:SOT23-6")
      (libsource (lib "eagle-import") (part "omat_ic_2_ESDAXXSC6"))
    )
    (comp (ref "X3")
      (value "MPT0.5/8-2.54")
      (footprint "eagle-import:MPT0.5_8-2.54")
      (libsource (lib "eagle-import") (part "omat_ic_2_MPT0.5/8-2.54"))
    )
    (comp (ref "C26")
      (value "100n")
      (footprint "eagle-import:C0603")
      (libsource (lib "eagle-import") (part "omat_ic_2_CAP0603"))
    )
    (comp (ref "C27")
      (value "100n")
      (footprint "eagle-import:C0603")
      (libsource (lib "eagle-import") (part "omat_ic_2_CAP0603"))
    )
    (comp (ref "C28")
      (value "100n")
      (footprint "eagle-import:C0603")
      (libsource (lib "eagle-import") (part "omat_ic_2_CAP0603"))
    )
    (comp (ref "C39")
      (value "10n")
      (footprint "eagle-import:OMAT_IC_2_C0603")
      (libsource (lib "eagle-import") (part "CAP0603"))
    )
    (comp (ref "C40")
      (value "CAP0603")
      (footprint "eagle-import:OMAT_IC_2_C0603")
      (libsource (lib "eagle-import") (part "CAP0603"))
    )
    (comp (ref "C41")
      (value "CAP0603")
      (footprint "eagle-import:OMAT_IC_2_C0603")
      (libsource (lib "eagle-import") (part "CAP0603"))
    )
    (comp (ref "C42")
      (value "CAP0603")
      (footprint "eagle-import:OMAT_IC_2_C0603")
      (libsource (lib "eagle-import") (part "CAP0603"))
    )
    (comp (ref "C43")
      (value "CAP0603")
      (footprint "eagle-import:OMAT_IC_2_C0603")
      (libsource (lib "eagle-import") (part "CAP0603"))
    )
    (comp (ref "C44")
      (value "CAP0603")
      (footprint "eagle-import:OMAT_IC_2_C0603")
      (libsource (lib "eagle-import") (part "CAP0603"))
    )
    (comp (ref "C45")
      (value "CAP0603")
      (footprint "eagle-import:OMAT_IC_2_C0603")
      (libsource (lib "eagle-import") (part "CAP0603"))
    )
    (comp (ref "C46")
      (value "CAP0603")
      (footprint "eagle-import:OMAT_IC_2_C0603")
      (libsource (lib "eagle-import") (part "CAP0603"))
    )
    (comp (ref "C48")
      (value "CAP0603")
      (footprint "eagle-import:OMAT_IC_2_C0603")
      (libsource (lib "eagle-import") (part "CAP0603"))
    )
    (comp (ref "C50")
      (value "CAP0603")
      (footprint "eagle-import:OMAT_IC_2_C0603")
      (libsource (lib "eagle-import") (part "CAP0603"))
    )
    (comp (ref "C51")
      (value "CAP0603")
      (footprint "eagle-import:OMAT_IC_2_C0603")
      (libsource (lib "eagle-import") (part "CAP0603"))
    )
    (comp (ref "C52")
      (value "CAP0603")
      (footprint "eagle-import:OMAT_IC_2_C0603")
      (libsource (lib "eagle-import") (part "CAP0603"))
    )
    (comp (ref "C56")
      (value "CAP0603")
      (footprint "eagle-import:OMAT_IC_2_C0603")
      (libsource (lib "eagle-import") (part "CAP0603"))
    )
    (comp (ref "C57")
      (value "CAP0603")
      (footprint "eagle-import:OMAT_IC_2_C0603")
      (libsource (lib "eagle-import") (part "CAP0603"))
    )
    (comp (ref "C59")
      (value "CAP0603")
      (footprint "eagle-import:OMAT_IC_2_C0603")
      (libsource (lib "eagle-import") (part "CAP0603"))
    )
    (comp (ref "C60")
      (value "CAP0603")
      (footprint "eagle-import:OMAT_IC_2_C0603")
      (libsource (lib "eagle-import") (part "CAP0603"))
    )
    (comp (ref "D9")
      (value "74AHC14")
      (footprint "eagle-import:SO14")
      (libsource (lib "eagle-import") (part "74AHC14"))
    )
    (comp (ref "D11")
      (value "74AHC14")
      (footprint "eagle-import:SO14")
      (libsource (lib "eagle-import") (part "74AHC14"))
    )
    (comp (ref "D12")
      (value "74AHC14")
      (footprint "eagle-import:SO14")
      (libsource (lib "eagle-import") (part "74AHC14"))
    )
    (comp (ref "R28")
      (value "2k2")
      (footprint "eagle-import:OMAT_IC_2_R0603")
      (libsource (lib "eagle-import") (part "RES0603"))
    )
    (comp (ref "R29")
      (value "5k90")
      (footprint "eagle-import:OMAT_IC_2_R0603")
      (libsource (lib "eagle-import") (part "RES0603"))
    )
    (comp (ref "R53")
      (value "RES0603")
      (footprint "eagle-import:OMAT_IC_2_R0603")
      (libsource (lib "eagle-import") (part "RES0603"))
    )
    (comp (ref "R54")
      (value "RES0603")
      (footprint "eagle-import:OMAT_IC_2_R0603")
      (libsource (lib "eagle-import") (part "RES0603"))
    )
    (comp (ref "R55")
      (value "RES0603")
      (footprint "eagle-import:OMAT_IC_2_R0603")
      (libsource (lib "eagle-import") (part "RES0603"))
    )
    (comp (ref "R56")
      (value "RES0603")
      (footprint "eagle-import:OMAT_IC_2_R0603")
      (libsource (lib "eagle-import") (part "RES0603"))
    )
    (comp (ref "R57")
      (value "RES0603")
      (footprint "eagle-import:OMAT_IC_2_R0603")
      (libsource (lib "eagle-import") (part "RES0603"))
    )
    (comp (ref "R60")
      (value "RES0603")
      (footprint "eagle-import:OMAT_IC_2_R0603")
      (libsource (lib "eagle-import") (part "RES0603"))
    )
    (comp (ref "R61")
      (value "RES0603")
      (footprint "eagle-import:OMAT_IC_2_R0603")
      (libsource (lib "eagle-import") (part "RES0603"))
    )
    (comp (ref "R62")
      (value "RES0603")
      (footprint "eagle-import:OMAT_IC_2_R0603")
      (libsource (lib "eagle-import") (part "RES0603"))
    )
    (comp (ref "R63")
      (value "RES0603")
      (footprint "eagle-import:OMAT_IC_2_R0603")
      (libsource (lib "eagle-import") (part "RES0603"))
    )
    (comp (ref "R64")
      (value "RES0603")
      (footprint "eagle-import:OMAT_IC_2_R0603")
      (libsource (lib "eagle-import") (part "RES0603"))
    )
    (comp (ref "R65")
      (value "RES0603")
      (footprint "eagle-import:OMAT_IC_2_R0603")
      (libsource (lib "eagle-import") (part "RES0603"))
    )
    (comp (ref "R66")
      (value "RES0603")
      (footprint "eagle-import:OMAT_IC_2_R0603")
      (libsource (lib "eagle-import") (part "RES0603"))
    )
    (comp (ref "R67")
      (value "RES0603")
      (footprint "eagle-import:OMAT_IC_2_R0603")
      (libsource (lib "eagle-import") (part "RES0603"))
    )
    (comp (ref "R68")
      (value "RES0603")
      (footprint "eagle-import:OMAT_IC_2_R0603")
      (libsource (lib "eagle-import") (part "RES0603"))
    )
    (comp (ref "R69")
      (value "RES0603")
      (footprint "eagle-import:OMAT_IC_2_R0603")
      (libsource (lib "eagle-import") (part "RES0603"))
    )
    (comp (ref "R70")
      (value "RES0603")
      (footprint "eagle-import:OMAT_IC_2_R0603")
      (libsource (lib "eagle-import") (part "RES0603"))
    )
    (comp (ref "R71")
      (value "RES0603")
      (footprint "eagle-import:OMAT_IC_2_R0603")
      (libsource (lib "eagle-import") (part "RES0603"))
    )
    (comp (ref "R72")
      (value "RES0603")
      (footprint "eagle-import:OMAT_IC_2_R0603")
      (libsource (lib "eagle-import") (part "RES0603"))
    )
    (comp (ref "R73")
      (value "RES0603")
      (footprint "eagle-import:OMAT_IC_2_R0603")
      (libsource (lib "eagle-import") (part "RES0603"))
    )
    (comp (ref "R74")
      (value "RES0603")
      (footprint "eagle-import:OMAT_IC_2_R0603")
      (libsource (lib "eagle-import") (part "RES0603"))
    )
    (comp (ref "R75")
      (value "RES0603")
      (footprint "eagle-import:OMAT_IC_2_R0603")
      (libsource (lib "eagle-import") (part "RES0603"))
    )
    (comp (ref "R76")
      (value "RES0603")
      (footprint "eagle-import:OMAT_IC_2_R0603")
      (libsource (lib "eagle-import") (part "RES0603"))
    )
    (comp (ref "R77")
      (value "RES0603")
      (footprint "eagle-import:OMAT_IC_2_R0603")
      (libsource (lib "eagle-import") (part "RES0603"))
    )
    (comp (ref "R78")
      (value "RES0603")
      (footprint "eagle-import:OMAT_IC_2_R0603")
      (libsource (lib "eagle-import") (part "RES0603"))
    )
    (comp (ref "R79")
      (value "RES0603")
      (footprint "eagle-import:OMAT_IC_2_R0603")
      (libsource (lib "eagle-import") (part "RES0603"))
    )
    (comp (ref "R80")
      (value "RES0603")
      (footprint "eagle-import:OMAT_IC_2_R0603")
      (libsource (lib "eagle-import") (part "RES0603"))
    )
    (comp (ref "R81")
      (value "RES0603")
      (footprint "eagle-import:OMAT_IC_2_R0603")
      (libsource (lib "eagle-import") (part "RES0603"))
    )
    (comp (ref "R82")
      (value "RES0603")
      (footprint "eagle-import:OMAT_IC_2_R0603")
      (libsource (lib "eagle-import") (part "RES0603"))
    )
    (comp (ref "R83")
      (value "RES0603")
      (footprint "eagle-import:OMAT_IC_2_R0603")
      (libsource (lib "eagle-import") (part "RES0603"))
    )
    (comp (ref "R84")
      (value "RES0603")
      (footprint "eagle-import:OMAT_IC_2_R0603")
      (libsource (lib "eagle-import") (part "RES0603"))
    )
    (comp (ref "V19")
      (value "ESDAXXSC6")
      (footprint "eagle-import:OMAT_IC_2_SOT23-6")
      (libsource (lib "eagle-import") (part "ESDAXXSC6"))
    )
    (comp (ref "V20")
      (value "ESDAXXSC6")
      (footprint "eagle-import:OMAT_IC_2_SOT23-6")
      (libsource (lib "eagle-import") (part "ESDAXXSC6"))
    )
    (comp (ref "V21")
      (value "ESDAXXSC6")
      (footprint "eagle-import:OMAT_IC_2_SOT23-6")
      (libsource (lib "eagle-import") (part "ESDAXXSC6"))
    )
    (comp (ref "V22")
      (value "ESDAXXSC6")
      (footprint "eagle-import:OMAT_IC_2_SOT23-6")
      (libsource (lib "eagle-import") (part "ESDAXXSC6"))
    )
    (comp (ref "X9")
      (value "MPT0.5/8-2.54")
      (footprint "eagle-import:OMAT_IC_2_MPT0.5_8-2.54")
      (libsource (lib "eagle-import") (part "MPT0.5/8-2.54"))
    )
    (comp (ref "X10")
      (value "MPT0.5/8-2.54")
      (footprint "eagle-import:OMAT_IC_2_MPT0.5_8-2.54")
      (libsource (lib "eagle-import") (part "MPT0.5/8-2.54"))
    )
    (comp (ref "X13")
      (value "MPT0.5/4-2.54")
      (footprint "eagle-import:MPT0.5_4-2.54")
      (libsource (lib "eagle-import") (part "MPT0.5/4-2.54"))
    )
    (comp (ref "C61")
      (value "100n")
      (footprint "eagle-import:C0603")
      (libsource (lib "eagle-import") (part "omat_ic_2_CAP0603"))
    )
    (comp (ref "C62")
      (value "2u2")
      (footprint "eagle-import:C0603")
      (libsource (lib "eagle-import") (part "omat_ic_2_CAP0603"))
    )
    (comp (ref "H1")
      (value "RED")
      (footprint "eagle-import:CHIP-LED0603")
      (libsource (lib "eagle-import") (part "LEDCHIP-LED0603"))
    )
    (comp (ref "H2")
      (value "GRN")
      (footprint "eagle-import:CHIP-LED0603")
      (libsource (lib "eagle-import") (part "LEDCHIP-LED0603"))
    )
    (comp (ref "H3")
      (value "GRN")
      (footprint "eagle-import:CHIP-LED0603")
      (libsource (lib "eagle-import") (part "LEDCHIP-LED0603"))
    )
    (comp (ref "L7")
      (value "IND0603")
      (footprint "eagle-import:R0603")
      (libsource (lib "eagle-import") (part "omat_ic_2_IND0603"))
    )
    (comp (ref "R5")
      (value "100R")
      (footprint "eagle-import:PASSIIVIT_R0603")
      (libsource (lib "eagle-import") (part "PASSIIVIT_RES0603"))
    )
    (comp (ref "R6")
      (value "31k6")
      (footprint "eagle-import:PASSIIVIT_R0603")
      (libsource (lib "eagle-import") (part "PASSIIVIT_RES0603"))
    )
    (comp (ref "R7")
      (value "10k0")
      (footprint "eagle-import:PASSIIVIT_R0603")
      (libsource (lib "eagle-import") (part "PASSIIVIT_RES0603"))
    )
    (comp (ref "R18")
      (value "499")
      (footprint "eagle-import:R0603")
      (libsource (lib "eagle-import") (part "omat_ic_2_RES0603"))
    )
    (comp (ref "R21")
      (value "1k47")
      (footprint "eagle-import:PASSIIVIT_R0603")
      (libsource (lib "eagle-import") (part "PASSIIVIT_RES0603"))
    )
    (comp (ref "R24")
      (value "499")
      (footprint "eagle-import:R0603")
      (libsource (lib "eagle-import") (part "omat_ic_2_RES0603"))
    )
    (comp (ref "R25")
      (value "499")
      (footprint "eagle-import:R0603")
      (libsource (lib "eagle-import") (part "omat_ic_2_RES0603"))
    )
    (comp (ref "R35")
      (value "RES0603")
      (footprint "eagle-import:OMAT_IC_2_R0603")
      (libsource (lib "eagle-import") (part "RES0603"))
    )
    (comp (ref "R86")
      (value "RES0603")
      (footprint "eagle-import:OMAT_IC_2_R0603")
      (libsource (lib "eagle-import") (part "RES0603"))
    )
    (comp (ref "R87")
      (value "RES0603")
      (footprint "eagle-import:OMAT_IC_2_R0603")
      (libsource (lib "eagle-import") (part "RES0603"))
    )
    (comp (ref "R88")
      (value "RES0603")
      (footprint "eagle-import:OMAT_IC_2_R0603")
      (libsource (lib "eagle-import") (part "RES0603"))
    )
    (comp (ref "U$1")
      (value "DAFUG")
      (footprint "eagle-import:DAFUG")
      (libsource (lib "eagle-import") (part "DAFUG"))
    )
    (comp (ref "V1")
      (value "2N3904")
      (footprint "eagle-import:OMAT_IC_2_SOT23")
      (libsource (lib "eagle-import") (part "2N3904"))
    )
    (comp (ref "V26")
      (value "SRV05-4")
      (footprint "eagle-import:OMAT_IC_2_SOT23-6")
      (libsource (lib "eagle-import") (part "SRV05-4"))
    )
    (comp (ref "X8")
      (value "PS-JOYSTICK")
      (footprint "eagle-import:PS-JOYSTICK")
      (libsource (lib "eagle-import") (part "PS-JOYSTICK"))
    )
    (comp (ref "X18")
      (value "629105136821")
      (footprint "eagle-import:629105136821")
      (libsource (lib "eagle-import") (part "629105136821"))
    )
    (comp (ref "C1")
      (value "220u 16V D")
      (footprint "eagle-import:CT7343")
      (libsource (lib "eagle-import") (part "CPOL-EUCT7343"))
    )
    (comp (ref "C2")
      (value "2u2 50V 0805")
      (footprint "eagle-import:C0805")
      (libsource (lib "eagle-import") (part "omat_ic_2_CAP0805"))
    )
    (comp (ref "C3")
      (value "2u2 50V 0805")
      (footprint "eagle-import:C0805")
      (libsource (lib "eagle-import") (part "omat_ic_2_CAP0805"))
    )
    (comp (ref "C4")
      (value "10n")
      (footprint "eagle-import:C0603")
      (libsource (lib "eagle-import") (part "omat_ic_2_CAP0603"))
    )
    (comp (ref "C31")
      (value "220u 16V D")
      (footprint "eagle-import:CT7343")
      (libsource (lib "eagle-import") (part "CPOL-EUCT7343"))
    )
    (comp (ref "C32")
      (value "10n")
      (footprint "eagle-import:C0603")
      (libsource (lib "eagle-import") (part "omat_ic_2_CAP0603"))
    )
    (comp (ref "C33")
      (value "2u2 50V 0805")
      (footprint "eagle-import:C0805")
      (libsource (lib "eagle-import") (part "omat_ic_2_CAP0805"))
    )
    (comp (ref "C34")
      (value "2u2 50V 0805")
      (footprint "eagle-import:C0805")
      (libsource (lib "eagle-import") (part "omat_ic_2_CAP0805"))
    )
    (comp (ref "C35")
      (value "220u 16V D")
      (footprint "eagle-import:CT7343")
      (libsource (lib "eagle-import") (part "CPOL-EUCT7343"))
    )
    (comp (ref "D10")
      (value "RT9818C-29GV")
      (footprint "eagle-import:SOT23")
      (libsource (lib "eagle-import") (part "RT9818C-29GV"))
    )
    (comp (ref "F1")
      (value "MINIBLADE-FUSEHOLDER-3568")
      (footprint "eagle-import:KEYSTONE-3568")
      (libsource (lib "eagle-import") (part "MINIBLADE-FUSEHOLDER-3568"))
    )
    (comp (ref "L1")
      (value "SDR1307-15UH")
      (footprint "eagle-import:SDR1307")
      (libsource (lib "eagle-import") (part "INDSDR1307"))
    )
    (comp (ref "L6")
      (value "VLP8040-47U")
      (footprint "eagle-import:VLP8040")
      (libsource (lib "eagle-import") (part "VLP8040-47U"))
    )
    (comp (ref "N1")
      (value "TPS5430DDA")
      (footprint "eagle-import:SOIC8-N-EP")
      (libsource (lib "eagle-import") (part "TPS5430DDA"))
    )
    (comp (ref "N2")
      (value "TPS5430DDA")
      (footprint "eagle-import:SOIC8-N-EP")
      (libsource (lib "eagle-import") (part "TPS5430DDA"))
    )
    (comp (ref "R1")
      (value "10k0")
      (footprint "eagle-import:R0603")
      (libsource (lib "eagle-import") (part "omat_ic_2_RES0603"))
    )
    (comp (ref "R2")
      (value "3k24")
      (footprint "eagle-import:R0603")
      (libsource (lib "eagle-import") (part "omat_ic_2_RES0603"))
    )
    (comp (ref "R16")
      (value "2k00")
      (footprint "eagle-import:R0603")
      (libsource (lib "eagle-import") (part "omat_ic_2_RES0603"))
    )
    (comp (ref "R49")
      (value "10k0")
      (footprint "eagle-import:R0603")
      (libsource (lib "eagle-import") (part "omat_ic_2_RES0603"))
    )
    (comp (ref "R50")
      (value "5k90")
      (footprint "eagle-import:R0603")
      (libsource (lib "eagle-import") (part "omat_ic_2_RES0603"))
    )
    (comp (ref "V13")
      (value "SBRD10200")
      (footprint "eagle-import:DPACK")
      (libsource (lib "eagle-import") (part "SBRD10200"))
    )
    (comp (ref "V16")
      (value "SMAJ20A")
      (footprint "eagle-import:DO214AC")
      (libsource (lib "eagle-import") (part "SMAJXXA"))
    )
    (comp (ref "V18")
      (value "SK34A")
      (footprint "eagle-import:DO214AC")
      (libsource (lib "eagle-import") (part "SK34A"))
    )
    (comp (ref "X6")
      (value "TE_RUUVILIITIN2")
      (footprint "eagle-import:TE_RUUVILIITIN2")
      (libsource (lib "eagle-import") (part "TE_RUUVILIITIN2"))
    )
    (comp (ref "Y1")
      (value "PTH2.6-5.5SQ")
      (footprint "eagle-import:PTH-2.6-5.5SQ")
      (libsource (lib "eagle-import") (part "PTH2.6-5.5SQ"))
    )
    (comp (ref "Y2")
      (value "PTH2.6-5.5SQ")
      (footprint "eagle-import:PTH-2.6-5.5SQ")
      (libsource (lib "eagle-import") (part "PTH2.6-5.5SQ"))
    )
    (comp (ref "Y3")
      (value "PTH2.6-5.5SQ")
      (footprint "eagle-import:PTH-2.6-5.5SQ")
      (libsource (lib "eagle-import") (part "PTH2.6-5.5SQ"))
    )
    (comp (ref "Y4")
      (value "PTH2.6-5.5SQ")
      (footprint "eagle-import:PTH-2.6-5.5SQ")
      (libsource (lib "eagle-import") (part "PTH2.6-5.5SQ"))
    )
    (comp (ref "C36")
      (value "100n")
      (footprint "eagle-import:C0603")
      (libsource (lib "eagle-import") (part "omat_ic_2_CAP0603"))
    )
    (comp (ref "C37")
      (value "100n")
      (footprint "eagle-import:C0603")
      (libsource (lib "eagle-import") (part "omat_ic_2_CAP0603"))
    )
    (comp (ref "C38")
      (value "2u2")
      (footprint "eagle-import:C0603")
      (libsource (lib "eagle-import") (part "omat_ic_2_CAP0603"))
    )
    (comp (ref "C49")
      (value "100n")
      (footprint "eagle-import:C0603")
      (libsource (lib "eagle-import") (part "omat_ic_2_CAP0603"))
    )
    (comp (ref "C65")
      (value "CAP0805")
      (footprint "eagle-import:OMAT_IC_2_C0805")
      (libsource (lib "eagle-import") (part "CAP0805"))
    )
    (comp (ref "C66")
      (value "CAP0805")
      (footprint "eagle-import:OMAT_IC_2_C0805")
      (libsource (lib "eagle-import") (part "CAP0805"))
    )
    (comp (ref "C67")
      (value "CAP0805")
      (footprint "eagle-import:OMAT_IC_2_C0805")
      (libsource (lib "eagle-import") (part "CAP0805"))
    )
    (comp (ref "D6")
      (value "LM75BD")
      (footprint "eagle-import:SOIC8-N_MC")
      (libsource (lib "eagle-import") (part "LM75BD"))
    )
    (comp (ref "D7")
      (value "IIS328DQTR")
      (footprint "eagle-import:QFN50P400X400X100-25N")
      (libsource (lib "eagle-import") (part "IIS328DQTR"))
    )
    (comp (ref "D8")
      (value "MAX3430_SA")
      (footprint "eagle-import:SOIC8-N_MC")
      (libsource (lib "eagle-import") (part "MAX3088_SA"))
    )
    (comp (ref "D15")
      (value "PCA9517")
      (footprint "eagle-import:OMAT_IC_2_SOIC8-N_MC")
      (libsource (lib "eagle-import") (part "PCA9517"))
    )
    (comp (ref "L8")
      (value "IND0603")
      (footprint "eagle-import:OMAT_IC_2_R0603")
      (libsource (lib "eagle-import") (part "IND0603"))
    )
    (comp (ref "L9")
      (value "IND0603")
      (footprint "eagle-import:OMAT_IC_2_R0603")
      (libsource (lib "eagle-import") (part "IND0603"))
    )
    (comp (ref "R51")
      (value "2k00")
      (footprint "eagle-import:R0603")
      (libsource (lib "eagle-import") (part "omat_ic_2_RES0603"))
    )
    (comp (ref "R52")
      (value "2k00")
      (footprint "eagle-import:R0603")
      (libsource (lib "eagle-import") (part "omat_ic_2_RES0603"))
    )
    (comp (ref "R58")
      (value "121 1206")
      (footprint "eagle-import:R1206")
      (libsource (lib "eagle-import") (part "omat_ic_2_RES1206"))
    )
    (comp (ref "R59")
      (value "2k00")
      (footprint "eagle-import:R0603")
      (libsource (lib "eagle-import") (part "omat_ic_2_RES0603"))
    )
    (comp (ref "R99")
      (value "2k00")
      (footprint "eagle-import:R0603")
      (libsource (lib "eagle-import") (part "omat_ic_2_RES0603"))
    )
    (comp (ref "R100")
      (value "2k00")
      (footprint "eagle-import:R0603")
      (libsource (lib "eagle-import") (part "omat_ic_2_RES0603"))
    )
    (comp (ref "V27")
      (value "ESDAXXSC6")
      (footprint "eagle-import:OMAT_IC_2_SOT23-6")
      (libsource (lib "eagle-import") (part "ESDAXXSC6"))
    )
    (comp (ref "V36")
      (value "SM712")
      (footprint "eagle-import:SOT23")
      (libsource (lib "eagle-import") (part "SM712"))
    )
    (comp (ref "X14")
      (value "MPT0.5/4-2.54")
      (footprint "eagle-import:MPT0.5_4-2.54")
      (libsource (lib "eagle-import") (part "MPT0.5/4-2.54"))
    )
    (comp (ref "X15")
      (value "MPT0.5/4-2.54")
      (footprint "eagle-import:MPT0.5_4-2.54")
      (libsource (lib "eagle-import") (part "MPT0.5/4-2.54"))
    )
    (comp (ref "C25")
      (value "CAP0603")
      (footprint "eagle-import:OMAT_IC_2_C0603")
      (libsource (lib "eagle-import") (part "CAP0603"))
    )
    (comp (ref "C29")
      (value "CAP0603")
      (footprint "eagle-import:OMAT_IC_2_C0603")
      (libsource (lib "eagle-import") (part "CAP0603"))
    )
    (comp (ref "C30")
      (value "CAP0603")
      (footprint "eagle-import:OMAT_IC_2_C0603")
      (libsource (lib "eagle-import") (part "CAP0603"))
    )
    (comp (ref "C63")
      (value "CAP0603")
      (footprint "eagle-import:OMAT_IC_2_C0603")
      (libsource (lib "eagle-import") (part "CAP0603"))
    )
    (comp (ref "C64")
      (value "CAP0603")
      (footprint "eagle-import:OMAT_IC_2_C0603")
      (libsource (lib "eagle-import") (part "CAP0603"))
    )
    (comp (ref "D3")
      (value "74AHCT125")
      (footprint "eagle-import:SO14")
      (libsource (lib "eagle-import") (part "74AHCT125"))
    )
    (comp (ref "D4")
      (value "74AHCT125")
      (footprint "eagle-import:SO14")
      (libsource (lib "eagle-import") (part "74AHCT125"))
    )
    (comp (ref "D5")
      (value "74AHCT125")
      (footprint "eagle-import:SO14")
      (libsource (lib "eagle-import") (part "74AHCT125"))
    )
    (comp (ref "D13")
      (value "74AHCT125")
      (footprint "eagle-import:SO14")
      (libsource (lib "eagle-import") (part "74AHCT125"))
    )
    (comp (ref "D14")
      (value "74AHCT125")
      (footprint "eagle-import:SO14")
      (libsource (lib "eagle-import") (part "74AHCT125"))
    )
    (comp (ref "R30")
      (value "RES0603")
      (footprint "eagle-import:OMAT_IC_2_R0603")
      (libsource (lib "eagle-import") (part "RES0603"))
    )
    (comp (ref "R31")
      (value "RES0603")
      (footprint "eagle-import:OMAT_IC_2_R0603")
      (libsource (lib "eagle-import") (part "RES0603"))
    )
    (comp (ref "R32")
      (value "RES0603")
      (footprint "eagle-import:OMAT_IC_2_R0603")
      (libsource (lib "eagle-import") (part "RES0603"))
    )
    (comp (ref "R33")
      (value "RES0603")
      (footprint "eagle-import:OMAT_IC_2_R0603")
      (libsource (lib "eagle-import") (part "RES0603"))
    )
    (comp (ref "R34")
      (value "RES0603")
      (footprint "eagle-import:OMAT_IC_2_R0603")
      (libsource (lib "eagle-import") (part "RES0603"))
    )
    (comp (ref "R37")
      (value "RES0603")
      (footprint "eagle-import:OMAT_IC_2_R0603")
      (libsource (lib "eagle-import") (part "RES0603"))
    )
    (comp (ref "R38")
      (value "RES0603")
      (footprint "eagle-import:OMAT_IC_2_R0603")
      (libsource (lib "eagle-import") (part "RES0603"))
    )
    (comp (ref "R39")
      (value "RES0603")
      (footprint "eagle-import:OMAT_IC_2_R0603")
      (libsource (lib "eagle-import") (part "RES0603"))
    )
    (comp (ref "R40")
      (value "RES0603")
      (footprint "eagle-import:OMAT_IC_2_R0603")
      (libsource (lib "eagle-import") (part "RES0603"))
    )
    (comp (ref "R41")
      (value "RES0603")
      (footprint "eagle-import:OMAT_IC_2_R0603")
      (libsource (lib "eagle-import") (part "RES0603"))
    )
    (comp (ref "R42")
      (value "RES0603")
      (footprint "eagle-import:OMAT_IC_2_R0603")
      (libsource (lib "eagle-import") (part "RES0603"))
    )
    (comp (ref "R43")
      (value "RES0603")
      (footprint "eagle-import:OMAT_IC_2_R0603")
      (libsource (lib "eagle-import") (part "RES0603"))
    )
    (comp (ref "R44")
      (value "RES0603")
      (footprint "eagle-import:OMAT_IC_2_R0603")
      (libsource (lib "eagle-import") (part "RES0603"))
    )
    (comp (ref "R89")
      (value "RES0603")
      (footprint "eagle-import:OMAT_IC_2_R0603")
      (libsource (lib "eagle-import") (part "RES0603"))
    )
    (comp (ref "R90")
      (value "RES0603")
      (footprint "eagle-import:OMAT_IC_2_R0603")
      (libsource (lib "eagle-import") (part "RES0603"))
    )
    (comp (ref "R91")
      (value "RES0603")
      (footprint "eagle-import:OMAT_IC_2_R0603")
      (libsource (lib "eagle-import") (part "RES0603"))
    )
    (comp (ref "R92")
      (value "RES0603")
      (footprint "eagle-import:OMAT_IC_2_R0603")
      (libsource (lib "eagle-import") (part "RES0603"))
    )
    (comp (ref "R93")
      (value "RES0603")
      (footprint "eagle-import:OMAT_IC_2_R0603")
      (libsource (lib "eagle-import") (part "RES0603"))
    )
    (comp (ref "R94")
      (value "RES0603")
      (footprint "eagle-import:OMAT_IC_2_R0603")
      (libsource (lib "eagle-import") (part "RES0603"))
    )
    (comp (ref "R95")
      (value "RES0603")
      (footprint "eagle-import:OMAT_IC_2_R0603")
      (libsource (lib "eagle-import") (part "RES0603"))
    )
    (comp (ref "R96")
      (value "RES0603")
      (footprint "eagle-import:OMAT_IC_2_R0603")
      (libsource (lib "eagle-import") (part "RES0603"))
    )
    (comp (ref "V14")
      (value "ESDAXXSC6")
      (footprint "eagle-import:OMAT_IC_2_SOT23-6")
      (libsource (lib "eagle-import") (part "ESDAXXSC6"))
    )
    (comp (ref "V15")
      (value "ESDAXXSC6")
      (footprint "eagle-import:OMAT_IC_2_SOT23-6")
      (libsource (lib "eagle-import") (part "ESDAXXSC6"))
    )
    (comp (ref "V17")
      (value "ESDAXXSC6")
      (footprint "eagle-import:OMAT_IC_2_SOT23-6")
      (libsource (lib "eagle-import") (part "ESDAXXSC6"))
    )
    (comp (ref "V23")
      (value "ESDAXXSC6")
      (footprint "eagle-import:OMAT_IC_2_SOT23-6")
      (libsource (lib "eagle-import") (part "ESDAXXSC6"))
    )
    (comp (ref "V25")
      (value "ESDAXXSC6")
      (footprint "eagle-import:OMAT_IC_2_SOT23-6")
      (libsource (lib "eagle-import") (part "ESDAXXSC6"))
    )
    (comp (ref "X4")
      (value "MPT0.5/4-2.54")
      (footprint "eagle-import:MPT0.5_4-2.54")
      (libsource (lib "eagle-import") (part "MPT0.5/4-2.54"))
    )
    (comp (ref "X5")
      (value "MPT0.5/4-2.54")
      (footprint "eagle-import:MPT0.5_4-2.54")
      (libsource (lib "eagle-import") (part "MPT0.5/4-2.54"))
    )
    (comp (ref "X7")
      (value "MPT0.5/4-2.54")
      (footprint "eagle-import:MPT0.5_4-2.54")
      (libsource (lib "eagle-import") (part "MPT0.5/4-2.54"))
    )
    (comp (ref "X11")
      (value "MPT0.5/4-2.54")
      (footprint "eagle-import:MPT0.5_4-2.54")
      (libsource (lib "eagle-import") (part "MPT0.5/4-2.54"))
    )
    (comp (ref "X12")
      (value "MPT0.5/4-2.54")
      (footprint "eagle-import:MPT0.5_4-2.54")
      (libsource (lib "eagle-import") (part "MPT0.5/4-2.54"))
    )
    (comp (ref "X17")
      (value "MPT0.5/4-2.54")
      (footprint "eagle-import:MPT0.5_4-2.54")
      (libsource (lib "eagle-import") (part "MPT0.5/4-2.54"))
    )
  )
  (nets
    (net (code "1") (name "+3V3") (class "Default")
      (node (ref "C13") (pin "1") (pinfunction "1_1") (pintype "passive"))
      (node (ref "C14") (pin "1") (pinfunction "1_1") (pintype "passive"))
      (node (ref "C15") (pin "1") (pinfunction "1_1") (pintype "passive"))
      (node (ref "C16") (pin "1") (pinfunction "1_1") (pintype "passive"))
      (node (ref "C17") (pin "1") (pinfunction "1_1") (pintype "passive"))
      (node (ref "C18") (pin "1") (pinfunction "1_1") (pintype "passive"))
      (node (ref "C19") (pin "1") (pinfunction "1_1") (pintype "passive"))
      (node (ref "C20") (pin "1") (pinfunction "1_1") (pintype "passive"))
      (node (ref "C21") (pin "1") (pinfunction "1_1") (pintype "passive"))
      (node (ref "C22") (pin "1") (pinfunction "1_1") (pintype "passive"))
      (node (ref "C26") (pin "1") (pinfunction "1_1") (pintype "passive"))
      (node (ref "C27") (pin "1") (pinfunction "1_1") (pintype "passive"))
      (node (ref "C28") (pin "1") (pinfunction "1_1") (pintype "passive"))
      (node (ref "C31") (pin "+") (pinfunction "+_+") (pintype "passive"))
      (node (ref "C36") (pin "1") (pinfunction "1_1") (pintype "passive"))
      (node (ref "C37") (pin "1") (pinfunction "1_1") (pintype "passive"))
      (node (ref "C38") (pin "1") (pinfunction "1_1") (pintype "passive"))
      (node (ref "C49") (pin "1") (pinfunction "1_1") (pintype "passive"))
      (node (ref "C58") (pin "1") (pinfunction "1_1") (pintype "passive"))
      (node (ref "C67") (pin "1") (pinfunction "1_1") (pintype "passive"))
      (node (ref "D1") (pin "108") (pinfunction "VDD9_108") (pintype "bidirectional"))
      (node (ref "D1") (pin "121") (pinfunction "VDD10_121") (pintype "bidirectional"))
      (node (ref "D1") (pin "131") (pinfunction "VDD11_131") (pintype "bidirectional"))
      (node (ref "D1") (pin "143") (pinfunction "PDR_ON_143") (pintype "bidirectional"))
      (node (ref "D1") (pin "144") (pinfunction "VDD12_144") (pintype "bidirectional"))
      (node (ref "D1") (pin "17") (pinfunction "VDD1_17") (pintype "bidirectional"))
      (node (ref "D1") (pin "30") (pinfunction "VDD2_30") (pintype "bidirectional"))
      (node (ref "D1") (pin "39") (pinfunction "VDD3_39") (pintype "bidirectional"))
      (node (ref "D1") (pin "52") (pinfunction "VDD4_52") (pintype "bidirectional"))
      (node (ref "D1") (pin "6") (pinfunction "VBAT_6") (pintype "bidirectional"))
      (node (ref "D1") (pin "62") (pinfunction "VDD5_62") (pintype "bidirectional"))
      (node (ref "D1") (pin "72") (pinfunction "VDD6_72") (pintype "bidirectional"))
      (node (ref "D1") (pin "84") (pinfunction "VDD7_84") (pintype "bidirectional"))
      (node (ref "D1") (pin "95") (pinfunction "VDD8_95") (pintype "bidirectional"))
      (node (ref "D10") (pin "3") (pinfunction "VCC_3") (pintype "bidirectional"))
      (node (ref "D11") (pin "14") (pinfunction "VCC_14") (pintype "bidirectional"))
      (node (ref "D12") (pin "14") (pinfunction "VCC_14") (pintype "bidirectional"))
      (node (ref "D15") (pin "1") (pinfunction "VCCA_1") (pintype "bidirectional"))
      (node (ref "D6") (pin "8") (pinfunction "VCC_8") (pintype "bidirectional"))
      (node (ref "D7") (pin "12") (pinfunction "CS_12") (pintype "bidirectional"))
      (node (ref "D7") (pin "13") (pinfunction "RSVD1_13") (pintype "bidirectional"))
      (node (ref "D7") (pin "14") (pinfunction "VDDIO_14") (pintype "bidirectional"))
      (node (ref "D7") (pin "5") (pinfunction "VDD_5") (pintype "bidirectional"))
      (node (ref "D8") (pin "8") (pinfunction "VCC_8") (pintype "power_in"))
      (node (ref "D9") (pin "14") (pinfunction "VCC_14") (pintype "bidirectional"))
      (node (ref "L2") (pin "2") (pinfunction "2_2") (pintype "passive"))
      (node (ref "L3") (pin "2") (pinfunction "2_2") (pintype "passive"))
      (node (ref "L6") (pin "2") (pinfunction "B_2") (pintype "bidirectional"))
      (node (ref "L7") (pin "2") (pinfunction "2_2") (pintype "passive"))
      (node (ref "L8") (pin "2") (pinfunction "2_2") (pintype "passive"))
      (node (ref "R16") (pin "2") (pinfunction "2_2") (pintype "passive"))
      (node (ref "R44") (pin "2") (pinfunction "2_2") (pintype "passive"))
      (node (ref "R49") (pin "1") (pinfunction "1_1") (pintype "passive"))
      (node (ref "R51") (pin "2") (pinfunction "2_2") (pintype "passive"))
      (node (ref "R52") (pin "2") (pinfunction "2_2") (pintype "passive"))
      (node (ref "V1") (pin "3") (pinfunction "C_3") (pintype "passive"))
      (node (ref "X1") (pin "B3") (pinfunction "3_B3") (pintype "passive"))
    )
    (net (code "2") (name "+5V") (class "Default")
      (node (ref "C1") (pin "+") (pinfunction "+_+") (pintype "passive"))
      (node (ref "C25") (pin "1") (pinfunction "1_1") (pintype "passive"))
      (node (ref "C29") (pin "1") (pinfunction "1_1") (pintype "passive"))
      (node (ref "C30") (pin "1") (pinfunction "1_1") (pintype "passive"))
      (node (ref "C35") (pin "+") (pinfunction "+_+") (pintype "passive"))
      (node (ref "C5") (pin "1") (pinfunction "1_1") (pintype "passive"))
      (node (ref "C63") (pin "1") (pinfunction "1_1") (pintype "passive"))
      (node (ref "C64") (pin "1") (pinfunction "1_1") (pintype "passive"))
      (node (ref "D13") (pin "14") (pinfunction "VCC_14") (pintype "bidirectional"))
      (node (ref "D14") (pin "14") (pinfunction "VCC_14") (pintype "bidirectional"))
      (node (ref "D2") (pin "14") (pinfunction "VCC_14") (pintype "bidirectional"))
      (node (ref "D3") (pin "14") (pinfunction "VCC_14") (pintype "bidirectional"))
      (node (ref "D4") (pin "14") (pinfunction "VCC_14") (pintype "bidirectional"))
      (node (ref "D5") (pin "14") (pinfunction "VCC_14") (pintype "bidirectional"))
      (node (ref "L1") (pin "2") (pinfunction "2_2") (pintype "passive"))
      (node (ref "L4") (pin "2") (pinfunction "2_2") (pintype "passive"))
      (node (ref "L5") (pin "2") (pinfunction "2_2") (pintype "passive"))
      (node (ref "L9") (pin "1") (pinfunction "1_1") (pintype "passive"))
      (node (ref "R1") (pin "1") (pinfunction "1_1") (pintype "passive"))
    )
    (net (code "3") (name "+12V") (class "Default")
      (node (ref "C2") (pin "1") (pinfunction "1_1") (pintype "passive"))
      (node (ref "C3") (pin "1") (pinfunction "1_1") (pintype "passive"))
      (node (ref "C33") (pin "1") (pinfunction "1_1") (pintype "passive"))
      (node (ref "C34") (pin "1") (pinfunction "1_1") (pintype "passive"))
      (node (ref "C53") (pin "1") (pinfunction "1_1") (pintype "passive"))
      (node (ref "F1") (pin "2") (pinfunction "2_2") (pintype "passive"))
      (node (ref "F1") (pin "3") (pinfunction "2_3") (pintype "passive"))
      (node (ref "N1") (pin "7") (pinfunction "VIN_7") (pintype "bidirectional"))
      (node (ref "N2") (pin "7") (pinfunction "VIN_7") (pintype "bidirectional"))
      (node (ref "R10") (pin "2") (pinfunction "2_2") (pintype "passive"))
      (node (ref "R12") (pin "2") (pinfunction "2_2") (pintype "passive"))
      (node (ref "R8") (pin "2") (pinfunction "2_2") (pintype "passive"))
      (node (ref "R85") (pin "1") (pinfunction "1_1") (pintype "passive"))
      (node (ref "R9") (pin "2") (pinfunction "2_2") (pintype "passive"))
      (node (ref "V16") (pin "C") (pinfunction "C_C") (pintype "passive"))
      (node (ref "V2") (pin "1") (pinfunction "S_1") (pintype "passive"))
      (node (ref "V2") (pin "3") (pinfunction "S_3") (pintype "passive"))
      (node (ref "V4") (pin "1") (pinfunction "S_1") (pintype "passive"))
      (node (ref "V4") (pin "3") (pinfunction "S_3") (pintype "passive"))
      (node (ref "X13") (pin "1") (pinfunction "1_1") (pintype "passive"))
      (node (ref "X13") (pin "2") (pinfunction "2_2") (pintype "passive"))
      (node (ref "X13") (pin "3") (pinfunction "3_3") (pintype "passive"))
      (node (ref "X13") (pin "4") (pinfunction "4_4") (pintype "passive"))
    )
    (net (code "4") (name "12VIN") (class "Default")
      (node (ref "F1") (pin "1") (pinfunction "1_1") (pintype "passive"))
      (node (ref "F1") (pin "4") (pinfunction "1_4") (pintype "passive"))
      (node (ref "X6") (pin "2") (pinfunction "2_2") (pintype "passive"))
    )
    (net (code "5") (name "DIR0") (class "Default")
      (node (ref "R31") (pin "2") (pinfunction "2_2") (pintype "passive"))
      (node (ref "V14") (pin "4") (pinfunction "C2_4") (pintype "passive"))
      (node (ref "X4") (pin "2") (pinfunction "2_2") (pintype "passive"))
    )
    (net (code "6") (name "DIR1") (class "Default")
      (node (ref "R33") (pin "2") (pinfunction "2_2") (pintype "passive"))
      (node (ref "V14") (pin "1") (pinfunction "C_1") (pintype "passive"))
      (node (ref "X4") (pin "4") (pinfunction "4_4") (pintype "passive"))
    )
    (net (code "7") (name "DIR2") (class "Default")
      (node (ref "R37") (pin "2") (pinfunction "2_2") (pintype "passive"))
      (node (ref "V15") (pin "4") (pinfunction "C2_4") (pintype "passive"))
      (node (ref "X5") (pin "2") (pinfunction "2_2") (pintype "passive"))
    )
    (net (code "8") (name "DIR3") (class "Default")
      (node (ref "R39") (pin "2") (pinfunction "2_2") (pintype "passive"))
      (node (ref "V15") (pin "1") (pinfunction "C_1") (pintype "passive"))
      (node (ref "X5") (pin "4") (pinfunction "4_4") (pintype "passive"))
    )
    (net (code "9") (name "DIR4") (class "Default")
      (node (ref "R41") (pin "2") (pinfunction "2_2") (pintype "passive"))
      (node (ref "V17") (pin "4") (pinfunction "C2_4") (pintype "passive"))
      (node (ref "X7") (pin "2") (pinfunction "2_2") (pintype "passive"))
    )
    (net (code "10") (name "DIR5") (class "Default")
      (node (ref "R43") (pin "2") (pinfunction "2_2") (pintype "passive"))
      (node (ref "V17") (pin "1") (pinfunction "C_1") (pintype "passive"))
      (node (ref "X7") (pin "4") (pinfunction "4_4") (pintype "passive"))
    )
    (net (code "11") (name "DIR_0") (class "Default")
      (node (ref "D1") (pin "59") (pinfunction "PE8_59") (pintype "bidirectional"))
      (node (ref "D3") (pin "5") (pinfunction "A2_5") (pintype "bidirectional"))
    )
    (net (code "12") (name "DIR_1") (class "Default")
      (node (ref "D1") (pin "60") (pinfunction "PE9_60") (pintype "bidirectional"))
      (node (ref "D3") (pin "12") (pinfunction "A4_12") (pintype "bidirectional"))
    )
    (net (code "13") (name "DIR_2") (class "Default")
      (node (ref "D1") (pin "63") (pinfunction "PE10_63") (pintype "bidirectional"))
      (node (ref "D4") (pin "5") (pinfunction "A2_5") (pintype "bidirectional"))
    )
    (net (code "14") (name "DIR_3") (class "Default")
      (node (ref "D1") (pin "64") (pinfunction "PE11_64") (pintype "bidirectional"))
      (node (ref "D4") (pin "12") (pinfunction "A4_12") (pintype "bidirectional"))
    )
    (net (code "15") (name "DIR_4") (class "Default")
      (node (ref "D1") (pin "65") (pinfunction "PE12_65") (pintype "bidirectional"))
      (node (ref "D5") (pin "5") (pinfunction "A2_5") (pintype "bidirectional"))
    )
    (net (code "16") (name "DIR_5") (class "Default")
      (node (ref "D1") (pin "66") (pinfunction "PE13_66") (pintype "bidirectional"))
      (node (ref "D5") (pin "12") (pinfunction "A4_12") (pintype "bidirectional"))
    )
    (net (code "17") (name "ENA0") (class "Default")
      (node (ref "R89") (pin "2") (pinfunction "2_2") (pintype "passive"))
      (node (ref "V23") (pin "6") (pinfunction "C3_6") (pintype "passive"))
      (node (ref "X11") (pin "1") (pinfunction "1_1") (pintype "passive"))
    )
    (net (code "18") (name "ENA1") (class "Default")
      (node (ref "R90") (pin "2") (pinfunction "2_2") (pintype "passive"))
      (node (ref "V23") (pin "4") (pinfunction "C2_4") (pintype "passive"))
      (node (ref "X11") (pin "2") (pinfunction "2_2") (pintype "passive"))
    )
    (net (code "19") (name "ENA2") (class "Default")
      (node (ref "R91") (pin "2") (pinfunction "2_2") (pintype "passive"))
      (node (ref "V23") (pin "3") (pinfunction "C1_3") (pintype "passive"))
      (node (ref "X11") (pin "3") (pinfunction "3_3") (pintype "passive"))
    )
    (net (code "20") (name "ENA3") (class "Default")
      (node (ref "R92") (pin "2") (pinfunction "2_2") (pintype "passive"))
      (node (ref "V23") (pin "1") (pinfunction "C_1") (pintype "passive"))
      (node (ref "X11") (pin "4") (pinfunction "4_4") (pintype "passive"))
    )
    (net (code "21") (name "ENA4") (class "Default")
      (node (ref "R93") (pin "2") (pinfunction "2_2") (pintype "passive"))
      (node (ref "V25") (pin "6") (pinfunction "C3_6") (pintype "passive"))
      (node (ref "X12") (pin "1") (pinfunction "1_1") (pintype "passive"))
    )
    (net (code "22") (name "ENA5") (class "Default")
      (node (ref "R94") (pin "2") (pinfunction "2_2") (pintype "passive"))
      (node (ref "V25") (pin "4") (pinfunction "C2_4") (pintype "passive"))
      (node (ref "X12") (pin "2") (pinfunction "2_2") (pintype "passive"))
    )
    (net (code "23") (name "ENABLE_N") (class "Default")
      (node (ref "D1") (pin "67") (pinfunction "PE14_67") (pintype "bidirectional"))
      (node (ref "D13") (pin "1") (pinfunction "OE1_1") (pintype "bidirectional"))
      (node (ref "D13") (pin "10") (pinfunction "OE3_10") (pintype "bidirectional"))
      (node (ref "D13") (pin "13") (pinfunction "OE4_13") (pintype "bidirectional"))
      (node (ref "D13") (pin "4") (pinfunction "OE2_4") (pintype "bidirectional"))
      (node (ref "D14") (pin "1") (pinfunction "OE1_1") (pintype "bidirectional"))
      (node (ref "D14") (pin "10") (pinfunction "OE3_10") (pintype "bidirectional"))
      (node (ref "D14") (pin "13") (pinfunction "OE4_13") (pintype "bidirectional"))
      (node (ref "D14") (pin "4") (pinfunction "OE2_4") (pintype "bidirectional"))
      (node (ref "D3") (pin "1") (pinfunction "OE1_1") (pintype "bidirectional"))
      (node (ref "D3") (pin "10") (pinfunction "OE3_10") (pintype "bidirectional"))
      (node (ref "D3") (pin "13") (pinfunction "OE4_13") (pintype "bidirectional"))
      (node (ref "D3") (pin "4") (pinfunction "OE2_4") (pintype "bidirectional"))
      (node (ref "D4") (pin "1") (pinfunction "OE1_1") (pintype "bidirectional"))
      (node (ref "D4") (pin "10") (pinfunction "OE3_10") (pintype "bidirectional"))
      (node (ref "D4") (pin "13") (pinfunction "OE4_13") (pintype "bidirectional"))
      (node (ref "D4") (pin "4") (pinfunction "OE2_4") (pintype "bidirectional"))
      (node (ref "D5") (pin "1") (pinfunction "OE1_1") (pintype "bidirectional"))
      (node (ref "D5") (pin "10") (pinfunction "OE3_10") (pintype "bidirectional"))
      (node (ref "D5") (pin "13") (pinfunction "OE4_13") (pintype "bidirectional"))
      (node (ref "D5") (pin "4") (pinfunction "OE2_4") (pintype "bidirectional"))
      (node (ref "R44") (pin "1") (pinfunction "1_1") (pintype "passive"))
    )
    (net (code "24") (name "ENABLE_PWM_N") (class "Default")
      (node (ref "D1") (pin "124") (pinfunction "PG9_124") (pintype "bidirectional"))
      (node (ref "D2") (pin "1") (pinfunction "OE1_1") (pintype "bidirectional"))
      (node (ref "D2") (pin "10") (pinfunction "OE3_10") (pintype "bidirectional"))
      (node (ref "D2") (pin "13") (pinfunction "OE4_13") (pintype "bidirectional"))
      (node (ref "D2") (pin "4") (pinfunction "OE2_4") (pintype "bidirectional"))
    )
    (net (code "25") (name "ENA_0") (class "Default")
      (node (ref "D1") (pin "56") (pinfunction "PG0_56") (pintype "bidirectional"))
      (node (ref "D13") (pin "2") (pinfunction "A1_2") (pintype "bidirectional"))
    )
    (net (code "26") (name "ENA_1") (class "Default")
      (node (ref "D1") (pin "57") (pinfunction "PG1_57") (pintype "bidirectional"))
      (node (ref "D13") (pin "5") (pinfunction "A2_5") (pintype "bidirectional"))
    )
    (net (code "27") (name "ENA_2") (class "Default")
      (node (ref "D1") (pin "87") (pinfunction "PG2_87") (pintype "bidirectional"))
      (node (ref "D13") (pin "9") (pinfunction "A3_9") (pintype "bidirectional"))
    )
    (net (code "28") (name "ENA_3") (class "Default")
      (node (ref "D1") (pin "88") (pinfunction "PG3_88") (pintype "bidirectional"))
      (node (ref "D13") (pin "12") (pinfunction "A4_12") (pintype "bidirectional"))
    )
    (net (code "29") (name "ENA_4") (class "Default")
      (node (ref "D1") (pin "89") (pinfunction "PG4_89") (pintype "bidirectional"))
      (node (ref "D14") (pin "2") (pinfunction "A1_2") (pintype "bidirectional"))
    )
    (net (code "30") (name "ENA_5") (class "Default")
      (node (ref "D1") (pin "90") (pinfunction "PG5_90") (pintype "bidirectional"))
      (node (ref "D14") (pin "5") (pinfunction "A2_5") (pintype "bidirectional"))
    )
    (net (code "31") (name "GND") (class "Default")
      (node (ref "C1") (pin "-") (pinfunction "-_-") (pintype "passive"))
      (node (ref "C10") (pin "2") (pinfunction "2_2") (pintype "passive"))
      (node (ref "C11") (pin "2") (pinfunction "2_2") (pintype "passive"))
      (node (ref "C12") (pin "2") (pinfunction "2_2") (pintype "passive"))
      (node (ref "C13") (pin "2") (pinfunction "2_2") (pintype "passive"))
      (node (ref "C14") (pin "2") (pinfunction "2_2") (pintype "passive"))
      (node (ref "C15") (pin "2") (pinfunction "2_2") (pintype "passive"))
      (node (ref "C16") (pin "2") (pinfunction "2_2") (pintype "passive"))
      (node (ref "C17") (pin "2") (pinfunction "2_2") (pintype "passive"))
      (node (ref "C18") (pin "2") (pinfunction "2_2") (pintype "passive"))
      (node (ref "C19") (pin "2") (pinfunction "2_2") (pintype "passive"))
      (node (ref "C2") (pin "2") (pinfunction "2_2") (pintype "passive"))
      (node (ref "C20") (pin "2") (pinfunction "2_2") (pintype "passive"))
      (node (ref "C21") (pin "2") (pinfunction "2_2") (pintype "passive"))
      (node (ref "C22") (pin "2") (pinfunction "2_2") (pintype "passive"))
      (node (ref "C23") (pin "2") (pinfunction "2_2") (pintype "passive"))
      (node (ref "C24") (pin "2") (pinfunction "2_2") (pintype "passive"))
      (node (ref "C25") (pin "2") (pinfunction "2_2") (pintype "passive"))
      (node (ref "C26") (pin "2") (pinfunction "2_2") (pintype "passive"))
      (node (ref "C27") (pin "2") (pinfunction "2_2") (pintype "passive"))
      (node (ref "C28") (pin "2") (pinfunction "2_2") (pintype "passive"))
      (node (ref "C29") (pin "2") (pinfunction "2_2") (pintype "passive"))
      (node (ref "C3") (pin "2") (pinfunction "2_2") (pintype "passive"))
      (node (ref "C30") (pin "2") (pinfunction "2_2") (pintype "passive"))
      (node (ref "C31") (pin "-") (pinfunction "-_-") (pintype "passive"))
      (node (ref "C33") (pin "2") (pinfunction "2_2") (pintype "passive"))
      (node (ref "C34") (pin "2") (pinfunction "2_2") (pintype "passive"))
      (node (ref "C35") (pin "-") (pinfunction "-_-") (pintype "passive"))
      (node (ref "C36") (pin "2") (pinfunction "2_2") (pintype "passive"))
      (node (ref "C37") (pin "2") (pinfunction "2_2") (pintype "passive"))
      (node (ref "C38") (pin "2") (pinfunction "2_2") (pintype "passive"))
      (node (ref "C39") (pin "2") (pinfunction "2_2") (pintype "passive"))
      (node (ref "C40") (pin "2") (pinfunction "2_2") (pintype "passive"))
      (node (ref "C41") (pin "2") (pinfunction "2_2") (pintype "passive"))
      (node (ref "C42") (pin "2") (pinfunction "2_2") (pintype "passive"))
      (node (ref "C43") (pin "2") (pinfunction "2_2") (pintype "passive"))
      (node (ref "C44") (pin "2") (pinfunction "2_2") (pintype "passive"))
      (node (ref "C45") (pin "2") (pinfunction "2_2") (pintype "passive"))
      (node (ref "C46") (pin "2") (pinfunction "2_2") (pintype "passive"))
      (node (ref "C47") (pin "2") (pinfunction "2_2") (pintype "passive"))
      (node (ref "C48") (pin "2") (pinfunction "2_2") (pintype "passive"))
      (node (ref "C49") (pin "2") (pinfunction "2_2") (pintype "passive"))
      (node (ref "C5") (pin "2") (pinfunction "2_2") (pintype "passive"))
      (node (ref "C50") (pin "2") (pinfunction "2_2") (pintype "passive"))
      (node (ref "C51") (pin "2") (pinfunction "2_2") (pintype "passive"))
      (node (ref "C52") (pin "2") (pinfunction "2_2") (pintype "passive"))
      (node (ref "C53") (pin "2") (pinfunction "2_2") (pintype "passive"))
      (node (ref "C54") (pin "2") (pinfunction "2_2") (pintype "passive"))
      (node (ref "C55") (pin "2") (pinfunction "2_2") (pintype "passive"))
      (node (ref "C56") (pin "2") (pinfunction "2_2") (pintype "passive"))
      (node (ref "C57") (pin "2") (pinfunction "2_2") (pintype "passive"))
      (node (ref "C58") (pin "2") (pinfunction "2_2") (pintype "passive"))
      (node (ref "C59") (pin "2") (pinfunction "2_2") (pintype "passive"))
      (node (ref "C6") (pin "2") (pinfunction "2_2") (pintype "passive"))
      (node (ref "C60") (pin "2") (pinfunction "2_2") (pintype "passive"))
      (node (ref "C61") (pin "2") (pinfunction "2_2") (pintype "passive"))
      (node (ref "C62") (pin "2") (pinfunction "2_2") (pintype "passive"))
      (node (ref "C63") (pin "2") (pinfunction "2_2") (pintype "passive"))
      (node (ref "C64") (pin "2") (pinfunction "2_2") (pintype "passive"))
      (node (ref "C65") (pin "2") (pinfunction "2_2") (pintype "passive"))
      (node (ref "C66") (pin "2") (pinfunction "2_2") (pintype "passive"))
      (node (ref "C67") (pin "2") (pinfunction "2_2") (pintype "passive"))
      (node (ref "C68") (pin "2") (pinfunction "2_2") (pintype "passive"))
      (node (ref "C69") (pin "2") (pinfunction "2_2") (pintype "passive"))
      (node (ref "C7") (pin "2") (pinfunction "2_2") (pintype "passive"))
      (node (ref "C8") (pin "2") (pinfunction "2_2") (pintype "passive"))
      (node (ref "C9") (pin "2") (pinfunction "2_2") (pintype "passive"))
      (node (ref "D1") (pin "107") (pinfunction "VSS7_107") (pintype "bidirectional"))
      (node (ref "D1") (pin "120") (pinfunction "VSS8_120") (pintype "bidirectional"))
      (node (ref "D1") (pin "130") (pinfunction "VSS9_130") (pintype "bidirectional"))
      (node (ref "D1") (pin "16") (pinfunction "VSS1_16") (pintype "bidirectional"))
      (node (ref "D1") (pin "31") (pinfunction "VSSA_31") (pintype "bidirectional"))
      (node (ref "D1") (pin "38") (pinfunction "VSS2_38") (pintype "bidirectional"))
      (node (ref "D1") (pin "51") (pinfunction "VSS3_51") (pintype "bidirectional"))
      (node (ref "D1") (pin "61") (pinfunction "VSS4_61") (pintype "bidirectional"))
      (node (ref "D1") (pin "83") (pinfunction "VSS5_83") (pintype "bidirectional"))
      (node (ref "D1") (pin "94") (pinfunction "VSS6_94") (pintype "bidirectional"))
      (node (ref "D10") (pin "2") (pinfunction "GND_2") (pintype "bidirectional"))
      (node (ref "D11") (pin "7") (pinfunction "GND_7") (pintype "bidirectional"))
      (node (ref "D12") (pin "11") (pinfunction "A_11") (pintype "bidirectional"))
      (node (ref "D12") (pin "13") (pinfunction "A_13") (pintype "bidirectional"))
      (node (ref "D12") (pin "7") (pinfunction "GND_7") (pintype "bidirectional"))
      (node (ref "D13") (pin "7") (pinfunction "GND_7") (pintype "bidirectional"))
      (node (ref "D14") (pin "7") (pinfunction "GND_7") (pintype "bidirectional"))
      (node (ref "D15") (pin "4") (pinfunction "GND_4") (pintype "bidirectional"))
      (node (ref "D2") (pin "7") (pinfunction "GND_7") (pintype "bidirectional"))
      (node (ref "D3") (pin "7") (pinfunction "GND_7") (pintype "bidirectional"))
      (node (ref "D4") (pin "7") (pinfunction "GND_7") (pintype "bidirectional"))
      (node (ref "D5") (pin "7") (pinfunction "GND_7") (pintype "bidirectional"))
      (node (ref "D6") (pin "4") (pinfunction "GND_4") (pintype "input"))
      (node (ref "D6") (pin "5") (pinfunction "A2_5") (pintype "bidirectional"))
      (node (ref "D6") (pin "6") (pinfunction "A1_6") (pintype "bidirectional"))
      (node (ref "D6") (pin "7") (pinfunction "A0_7") (pintype "bidirectional"))
      (node (ref "D7") (pin "10") (pinfunction "GND_10") (pintype "bidirectional"))
      (node (ref "D7") (pin "15") (pinfunction "SAO/SPISDO_15") (pintype "bidirectional"))
      (node (ref "D7") (pin "25") (pinfunction "EP_25") (pintype "bidirectional"))
      (node (ref "D7") (pin "4") (pinfunction "RSVD2_4") (pintype "bidirectional"))
      (node (ref "D7") (pin "6") (pinfunction "GND_6") (pintype "bidirectional"))
      (node (ref "D7") (pin "8") (pinfunction "GND_8") (pintype "bidirectional"))
      (node (ref "D7") (pin "9") (pinfunction "GND_9") (pintype "bidirectional"))
      (node (ref "D8") (pin "5") (pinfunction "GND_5") (pintype "power_in"))
      (node (ref "D9") (pin "7") (pinfunction "GND_7") (pintype "bidirectional"))
      (node (ref "N1") (pin "6") (pinfunction "GND_6") (pintype "bidirectional"))
      (node (ref "N1") (pin "EP") (pinfunction "EP_EP") (pintype "bidirectional"))
      (node (ref "N2") (pin "6") (pinfunction "GND_6") (pintype "bidirectional"))
      (node (ref "N2") (pin "EP") (pinfunction "EP_EP") (pintype "bidirectional"))
      (node (ref "N3") (pin "2") (pinfunction "GND_2") (pintype "bidirectional"))
      (node (ref "N3") (pin "4") (pinfunction "GND_4") (pintype "bidirectional"))
      (node (ref "N3") (pin "5") (pinfunction "GND_5") (pintype "bidirectional"))
      (node (ref "N3") (pin "6") (pinfunction "GND_6") (pintype "input"))
      (node (ref "R11") (pin "2") (pinfunction "2_2") (pintype "passive"))
      (node (ref "R13") (pin "2") (pinfunction "2_2") (pintype "passive"))
      (node (ref "R14") (pin "2") (pinfunction "2_2") (pintype "passive"))
      (node (ref "R15") (pin "2") (pinfunction "2_2") (pintype "passive"))
      (node (ref "R18") (pin "1") (pinfunction "1_1") (pintype "passive"))
      (node (ref "R19") (pin "1") (pinfunction "1_1") (pintype "passive"))
      (node (ref "R2") (pin "2") (pinfunction "2_2") (pintype "passive"))
      (node (ref "R20") (pin "1") (pinfunction "1_1") (pintype "passive"))
      (node (ref "R24") (pin "1") (pinfunction "1_1") (pintype "passive"))
      (node (ref "R25") (pin "1") (pinfunction "1_1") (pintype "passive"))
      (node (ref "R28") (pin "1") (pinfunction "1_1") (pintype "passive"))
      (node (ref "R36") (pin "1") (pinfunction "1_1") (pintype "passive"))
      (node (ref "R45") (pin "1") (pinfunction "1_1") (pintype "passive"))
      (node (ref "R46") (pin "1") (pinfunction "1_1") (pintype "passive"))
      (node (ref "R47") (pin "1") (pinfunction "1_1") (pintype "passive"))
      (node (ref "R48") (pin "1") (pinfunction "1_1") (pintype "passive"))
      (node (ref "R50") (pin "2") (pinfunction "2_2") (pintype "passive"))
      (node (ref "R53") (pin "1") (pinfunction "1_1") (pintype "passive"))
      (node (ref "R55") (pin "1") (pinfunction "1_1") (pintype "passive"))
      (node (ref "R57") (pin "1") (pinfunction "1_1") (pintype "passive"))
      (node (ref "R59") (pin "1") (pinfunction "1_1") (pintype "passive"))
      (node (ref "R6") (pin "1") (pinfunction "1_1") (pintype "passive"))
      (node (ref "R61") (pin "1") (pinfunction "1_1") (pintype "passive"))
      (node (ref "R63") (pin "1") (pinfunction "1_1") (pintype "passive"))
      (node (ref "R65") (pin "1") (pinfunction "1_1") (pintype "passive"))
      (node (ref "R67") (pin "1") (pinfunction "1_1") (pintype "passive"))
      (node (ref "R69") (pin "1") (pinfunction "1_1") (pintype "passive"))
      (node (ref "R71") (pin "1") (pinfunction "1_1") (pintype "passive"))
      (node (ref "R73") (pin "1") (pinfunction "1_1") (pintype "passive"))
      (node (ref "R75") (pin "1") (pinfunction "1_1") (pintype "passive"))
      (node (ref "R77") (pin "1") (pinfunction "1_1") (pintype "passive"))
      (node (ref "R79") (pin "1") (pinfunction "1_1") (pintype "passive"))
      (node (ref "R81") (pin "1") (pinfunction "1_1") (pintype "passive"))
      (node (ref "R83") (pin "1") (pinfunction "1_1") (pintype "passive"))
      (node (ref "V13") (pin "1") (pinfunction "A_1") (pintype "passive"))
      (node (ref "V13") (pin "3") (pinfunction "A_3") (pintype "passive"))
      (node (ref "V14") (pin "2") (pinfunction "A_2") (pintype "passive"))
      (node (ref "V14") (pin "5") (pinfunction "A1_5") (pintype "passive"))
      (node (ref "V15") (pin "2") (pinfunction "A_2") (pintype "passive"))
      (node (ref "V15") (pin "5") (pinfunction "A1_5") (pintype "passive"))
      (node (ref "V16") (pin "A") (pinfunction "A_A") (pintype "passive"))
      (node (ref "V17") (pin "2") (pinfunction "A_2") (pintype "passive"))
      (node (ref "V17") (pin "5") (pinfunction "A1_5") (pintype "passive"))
      (node (ref "V18") (pin "A") (pinfunction "A_A") (pintype "passive"))
      (node (ref "V19") (pin "2") (pinfunction "A_2") (pintype "passive"))
      (node (ref "V19") (pin "5") (pinfunction "A1_5") (pintype "passive"))
      (node (ref "V20") (pin "2") (pinfunction "A_2") (pintype "passive"))
      (node (ref "V20") (pin "5") (pinfunction "A1_5") (pintype "passive"))
      (node (ref "V21") (pin "2") (pinfunction "A_2") (pintype "passive"))
      (node (ref "V21") (pin "5") (pinfunction "A1_5") (pintype "passive"))
      (node (ref "V22") (pin "2") (pinfunction "A_2") (pintype "passive"))
      (node (ref "V22") (pin "5") (pinfunction "A1_5") (pintype "passive"))
      (node (ref "V23") (pin "2") (pinfunction "A_2") (pintype "passive"))
      (node (ref "V23") (pin "5") (pinfunction "A1_5") (pintype "passive"))
      (node (ref "V24") (pin "2") (pinfunction "A_2") (pintype "passive"))
      (node (ref "V24") (pin "5") (pinfunction "A1_5") (pintype "passive"))
      (node (ref "V25") (pin "2") (pinfunction "A_2") (pintype "passive"))
      (node (ref "V25") (pin "5") (pinfunction "A1_5") (pintype "passive"))
      (node (ref "V26") (pin "2") (pinfunction "GND_2") (pintype "bidirectional"))
      (node (ref "V27") (pin "2") (pinfunction "A_2") (pintype "passive"))
      (node (ref "V27") (pin "5") (pinfunction "A1_5") (pintype "passive"))
      (node (ref "V3") (pin "2") (pinfunction "S_2") (pintype "passive"))
      (node (ref "V36") (pin "3") (pinfunction "3_3") (pintype "bidirectional"))
      (node (ref "V5") (pin "2") (pinfunction "S_2") (pintype "passive"))
      (node (ref "V6") (pin "2") (pinfunction "A_2") (pintype "passive"))
      (node (ref "V6") (pin "5") (pinfunction "A1_5") (pintype "passive"))
      (node (ref "V7") (pin "2") (pinfunction "S_2") (pintype "passive"))
      (node (ref "V9") (pin "2") (pinfunction "S_2") (pintype "passive"))
      (node (ref "X1") (pin "B2") (pinfunction "2_B2") (pintype "passive"))
      (node (ref "X1") (pin "B4") (pinfunction "4_B4") (pintype "passive"))
      (node (ref "X1") (pin "B5") (pinfunction "5_B5") (pintype "passive"))
      (node (ref "X14") (pin "3") (pinfunction "3_3") (pintype "passive"))
      (node (ref "X16") (pin "1") (pinfunction "1_1") (pintype "passive"))
      (node (ref "X16") (pin "4") (pinfunction "4_4") (pintype "passive"))
      (node (ref "X17") (pin "1") (pinfunction "1_1") (pintype "passive"))
      (node (ref "X17") (pin "2") (pinfunction "2_2") (pintype "passive"))
      (node (ref "X17") (pin "3") (pinfunction "3_3") (pintype "passive"))
      (node (ref "X17") (pin "4") (pinfunction "4_4") (pintype "passive"))
      (node (ref "X18") (pin "5") (pinfunction "5_5") (pintype "passive"))
      (node (ref "X18") (pin "Z1") (pinfunction "5_Z1") (pintype "passive"))
      (node (ref "X18") (pin "Z2") (pinfunction "5_Z2") (pintype "passive"))
      (node (ref "X18") (pin "Z3") (pinfunction "5_Z3") (pintype "passive"))
      (node (ref "X18") (pin "Z4") (pinfunction "5_Z4") (pintype "passive"))
      (node (ref "X2") (pin "3") (pinfunction "3_3") (pintype "passive"))
      (node (ref "X2") (pin "6") (pinfunction "6_6") (pintype "passive"))
      (node (ref "X3") (pin "2") (pinfunction "2_2") (pintype "passive"))
      (node (ref "X3") (pin "4") (pinfunction "4_4") (pintype "passive"))
      (node (ref "X3") (pin "6") (pinfunction "6_6") (pintype "passive"))
      (node (ref "X3") (pin "8") (pinfunction "8_8") (pintype "passive"))
      (node (ref "X6") (pin "1") (pinfunction "1_1") (pintype "passive"))
      (node (ref "X8") (pin "4") (pinfunction "GND_4") (pintype "passive"))
      (node (ref "Y1") (pin "1") (pinfunction "1_1") (pintype "bidirectional"))
      (node (ref "Y2") (pin "1") (pinfunction "1_1") (pintype "bidirectional"))
      (node (ref "Y3") (pin "1") (pinfunction "1_1") (pintype "bidirectional"))
      (node (ref "Y4") (pin "1") (pinfunction "1_1") (pintype "bidirectional"))
    )
    (net (code "32") (name "I2C1SCL") (class "Default")
      (node (ref "D1") (pin "136") (pinfunction "PB6_136") (pintype "bidirectional"))
      (node (ref "D15") (pin "2") (pinfunction "SCLA_2") (pintype "bidirectional"))
      (node (ref "D6") (pin "2") (pinfunction "SCL_2") (pintype "bidirectional"))
      (node (ref "D7") (pin "11") (pinfunction "SCL/SPICLK_11") (pintype "bidirectional"))
      (node (ref "R52") (pin "1") (pinfunction "1_1") (pintype "passive"))
    )
    (net (code "33") (name "I2C1SDA") (class "Default")
      (node (ref "D1") (pin "137") (pinfunction "PB7_137") (pintype "bidirectional"))
      (node (ref "D15") (pin "3") (pinfunction "SDAA_3") (pintype "bidirectional"))
      (node (ref "D6") (pin "1") (pinfunction "SDA_1") (pintype "power_in"))
      (node (ref "D7") (pin "16") (pinfunction "SDA/SPISDI_16") (pintype "bidirectional"))
      (node (ref "R51") (pin "1") (pinfunction "1_1") (pintype "passive"))
    )
    (net (code "34") (name "I2CSCL") (class "Default")
      (node (ref "D15") (pin "7") (pinfunction "SCLB_7") (pintype "bidirectional"))
      (node (ref "R100") (pin "1") (pinfunction "1_1") (pintype "passive"))
      (node (ref "V27") (pin "3") (pinfunction "C1_3") (pintype "passive"))
      (node (ref "X14") (pin "4") (pinfunction "4_4") (pintype "passive"))
    )
    (net (code "35") (name "I2CSDA") (class "Default")
      (node (ref "D15") (pin "6") (pinfunction "SDAB_6") (pintype "bidirectional"))
      (node (ref "R99") (pin "1") (pinfunction "1_1") (pintype "passive"))
      (node (ref "V27") (pin "4") (pinfunction "C2_4") (pintype "passive"))
      (node (ref "X14") (pin "2") (pinfunction "2_2") (pintype "passive"))
    )
    (net (code "36") (name "I2CVCC") (class "Default")
      (node (ref "C65") (pin "1") (pinfunction "1_1") (pintype "passive"))
      (node (ref "C66") (pin "1") (pinfunction "1_1") (pintype "passive"))
      (node (ref "D15") (pin "5") (pinfunction "EN_5") (pintype "bidirectional"))
      (node (ref "D15") (pin "8") (pinfunction "VCCB_8") (pintype "bidirectional"))
      (node (ref "L8") (pin "1") (pinfunction "1_1") (pintype "passive"))
      (node (ref "L9") (pin "2") (pinfunction "2_2") (pintype "passive"))
      (node (ref "R100") (pin "2") (pinfunction "2_2") (pintype "passive"))
      (node (ref "R99") (pin "2") (pinfunction "2_2") (pintype "passive"))
      (node (ref "V27") (pin "6") (pinfunction "C3_6") (pintype "passive"))
      (node (ref "X14") (pin "1") (pinfunction "1_1") (pintype "passive"))
    )
    (net (code "37") (name "INPUT0") (class "Default")
      (node (ref "R29") (pin "2") (pinfunction "2_2") (pintype "passive"))
      (node (ref "V19") (pin "3") (pinfunction "C1_3") (pintype "passive"))
      (node (ref "X9") (pin "1") (pinfunction "1_1") (pintype "passive"))
    )
    (net (code "38") (name "INPUT1") (class "Default")
      (node (ref "R54") (pin "2") (pinfunction "2_2") (pintype "passive"))
      (node (ref "V19") (pin "1") (pinfunction "C_1") (pintype "passive"))
      (node (ref "X9") (pin "2") (pinfunction "2_2") (pintype "passive"))
    )
    (net (code "39") (name "INPUT2") (class "Default")
      (node (ref "R56") (pin "2") (pinfunction "2_2") (pintype "passive"))
      (node (ref "V19") (pin "6") (pinfunction "C3_6") (pintype "passive"))
      (node (ref "X9") (pin "3") (pinfunction "3_3") (pintype "passive"))
    )
    (net (code "40") (name "INPUT3") (class "Default")
      (node (ref "R60") (pin "2") (pinfunction "2_2") (pintype "passive"))
      (node (ref "V19") (pin "4") (pinfunction "C2_4") (pintype "passive"))
      (node (ref "X9") (pin "4") (pinfunction "4_4") (pintype "passive"))
    )
    (net (code "41") (name "INPUT4") (class "Default")
      (node (ref "R62") (pin "2") (pinfunction "2_2") (pintype "passive"))
      (node (ref "V20") (pin "3") (pinfunction "C1_3") (pintype "passive"))
      (node (ref "X9") (pin "5") (pinfunction "5_5") (pintype "passive"))
    )
    (net (code "42") (name "INPUT5") (class "Default")
      (node (ref "R64") (pin "2") (pinfunction "2_2") (pintype "passive"))
      (node (ref "V20") (pin "1") (pinfunction "C_1") (pintype "passive"))
      (node (ref "X9") (pin "6") (pinfunction "6_6") (pintype "passive"))
    )
    (net (code "43") (name "INPUT6") (class "Default")
      (node (ref "R66") (pin "2") (pinfunction "2_2") (pintype "passive"))
      (node (ref "V20") (pin "6") (pinfunction "C3_6") (pintype "passive"))
      (node (ref "X9") (pin "7") (pinfunction "7_7") (pintype "passive"))
    )
    (net (code "44") (name "INPUT7") (class "Default")
      (node (ref "R68") (pin "2") (pinfunction "2_2") (pintype "passive"))
      (node (ref "V20") (pin "4") (pinfunction "C2_4") (pintype "passive"))
      (node (ref "X9") (pin "8") (pinfunction "8_8") (pintype "passive"))
    )
    (net (code "45") (name "INPUT8") (class "Default")
      (node (ref "R70") (pin "2") (pinfunction "2_2") (pintype "passive"))
      (node (ref "V21") (pin "3") (pinfunction "C1_3") (pintype "passive"))
      (node (ref "X10") (pin "1") (pinfunction "1_1") (pintype "passive"))
    )
    (net (code "46") (name "INPUT9") (class "Default")
      (node (ref "R72") (pin "2") (pinfunction "2_2") (pintype "passive"))
      (node (ref "V21") (pin "1") (pinfunction "C_1") (pintype "passive"))
      (node (ref "X10") (pin "2") (pinfunction "2_2") (pintype "passive"))
    )
    (net (code "47") (name "INPUT10") (class "Default")
      (node (ref "R74") (pin "2") (pinfunction "2_2") (pintype "passive"))
      (node (ref "V21") (pin "6") (pinfunction "C3_6") (pintype "passive"))
      (node (ref "X10") (pin "3") (pinfunction "3_3") (pintype "passive"))
    )
    (net (code "48") (name "INPUT11") (class "Default")
      (node (ref "R76") (pin "2") (pinfunction "2_2") (pintype "passive"))
      (node (ref "V21") (pin "4") (pinfunction "C2_4") (pintype "passive"))
      (node (ref "X10") (pin "4") (pinfunction "4_4") (pintype "passive"))
    )
    (net (code "49") (name "INPUT12") (class "Default")
      (node (ref "R78") (pin "2") (pinfunction "2_2") (pintype "passive"))
      (node (ref "V22") (pin "3") (pinfunction "C1_3") (pintype "passive"))
      (node (ref "X10") (pin "5") (pinfunction "5_5") (pintype "passive"))
    )
    (net (code "50") (name "INPUT13") (class "Default")
      (node (ref "R80") (pin "2") (pinfunction "2_2") (pintype "passive"))
      (node (ref "V22") (pin "1") (pinfunction "C_1") (pintype "passive"))
      (node (ref "X10") (pin "6") (pinfunction "6_6") (pintype "passive"))
    )
    (net (code "51") (name "INPUT14") (class "Default")
      (node (ref "R82") (pin "2") (pinfunction "2_2") (pintype "passive"))
      (node (ref "V22") (pin "6") (pinfunction "C3_6") (pintype "passive"))
      (node (ref "X10") (pin "7") (pinfunction "7_7") (pintype "passive"))
    )
    (net (code "52") (name "INPUT15") (class "Default")
      (node (ref "R84") (pin "2") (pinfunction "2_2") (pintype "passive"))
      (node (ref "V22") (pin "4") (pinfunction "C2_4") (pintype "passive"))
      (node (ref "X10") (pin "8") (pinfunction "8_8") (pintype "passive"))
    )
    (net (code "53") (name "INPUT_0") (class "Default")
      (node (ref "D1") (pin "98") (pinfunction "PC8_98") (pintype "bidirectional"))
      (node (ref "D9") (pin "2") (pinfunction "Y_2") (pintype "bidirectional"))
    )
    (net (code "54") (name "INPUT_1") (class "Default")
      (node (ref "D1") (pin "99") (pinfunction "PC9_99") (pintype "bidirectional"))
      (node (ref "D9") (pin "4") (pinfunction "Y_4") (pintype "bidirectional"))
    )
    (net (code "55") (name "INPUT_2") (class "Default")
      (node (ref "D1") (pin "111") (pinfunction "PC10_111") (pintype "bidirectional"))
      (node (ref "D9") (pin "6") (pinfunction "Y_6") (pintype "bidirectional"))
    )
    (net (code "56") (name "INPUT_3") (class "Default")
      (node (ref "D1") (pin "112") (pinfunction "PC11_112") (pintype "bidirectional"))
      (node (ref "D9") (pin "8") (pinfunction "Y_8") (pintype "bidirectional"))
    )
    (net (code "57") (name "INPUT_4") (class "Default")
      (node (ref "D1") (pin "113") (pinfunction "PC12_113") (pintype "bidirectional"))
      (node (ref "D9") (pin "10") (pinfunction "Y_10") (pintype "bidirectional"))
    )
    (net (code "58") (name "INPUT_5") (class "Default")
      (node (ref "D1") (pin "7") (pinfunction "PC13_7") (pintype "bidirectional"))
      (node (ref "D9") (pin "12") (pinfunction "Y_12") (pintype "bidirectional"))
    )
    (net (code "59") (name "INPUT_6") (class "Default")
      (node (ref "D1") (pin "8") (pinfunction "PC14/OSC32IN_8") (pintype "bidirectional"))
      (node (ref "D11") (pin "2") (pinfunction "Y_2") (pintype "bidirectional"))
    )
    (net (code "60") (name "INPUT_7") (class "Default")
      (node (ref "D1") (pin "9") (pinfunction "PC15/OSC32OUT_9") (pintype "bidirectional"))
      (node (ref "D11") (pin "4") (pinfunction "Y_4") (pintype "bidirectional"))
    )
    (net (code "61") (name "INPUT_8") (class "Default")
      (node (ref "D1") (pin "114") (pinfunction "PD0_114") (pintype "bidirectional"))
      (node (ref "D11") (pin "6") (pinfunction "Y_6") (pintype "bidirectional"))
    )
    (net (code "62") (name "INPUT_9") (class "Default")
      (node (ref "D1") (pin "115") (pinfunction "PD1_115") (pintype "bidirectional"))
      (node (ref "D11") (pin "8") (pinfunction "Y_8") (pintype "bidirectional"))
    )
    (net (code "63") (name "INPUT_10") (class "Default")
      (node (ref "D1") (pin "116") (pinfunction "PD2_116") (pintype "bidirectional"))
      (node (ref "D11") (pin "10") (pinfunction "Y_10") (pintype "bidirectional"))
    )
    (net (code "64") (name "INPUT_11") (class "Default")
      (node (ref "D1") (pin "117") (pinfunction "PD3_117") (pintype "bidirectional"))
      (node (ref "D11") (pin "12") (pinfunction "Y_12") (pintype "bidirectional"))
    )
    (net (code "65") (name "INPUT_12") (class "Default")
      (node (ref "D1") (pin "118") (pinfunction "PD4_118") (pintype "bidirectional"))
      (node (ref "D12") (pin "2") (pinfunction "Y_2") (pintype "bidirectional"))
    )
    (net (code "66") (name "INPUT_13") (class "Default")
      (node (ref "D1") (pin "119") (pinfunction "PD5_119") (pintype "bidirectional"))
      (node (ref "D12") (pin "4") (pinfunction "Y_4") (pintype "bidirectional"))
    )
    (net (code "67") (name "INPUT_14") (class "Default")
      (node (ref "D1") (pin "122") (pinfunction "PD6_122") (pintype "bidirectional"))
      (node (ref "D12") (pin "6") (pinfunction "Y_6") (pintype "bidirectional"))
    )
    (net (code "68") (name "INPUT_15") (class "Default")
      (node (ref "D1") (pin "123") (pinfunction "PD7_123") (pintype "bidirectional"))
      (node (ref "D12") (pin "8") (pinfunction "Y_8") (pintype "bidirectional"))
    )
    (net (code "69") (name "LEDDATA") (class "Default")
      (node (ref "R27") (pin "2") (pinfunction "2_2") (pintype "passive"))
      (node (ref "R48") (pin "2") (pinfunction "2_2") (pintype "passive"))
      (node (ref "V6") (pin "1") (pinfunction "C_1") (pintype "passive"))
      (node (ref "X16") (pin "3") (pinfunction "3_3") (pintype "passive"))
    )
    (net (code "70") (name "LED_DEBUG") (class "Default")
      (node (ref "D1") (pin "28") (pinfunction "PC2_28") (pintype "bidirectional"))
      (node (ref "H2") (pin "A") (pinfunction "A_A") (pintype "passive"))
    )
    (net (code "71") (name "LED_ERR") (class "Default")
      (node (ref "D1") (pin "44") (pinfunction "PC4_44") (pintype "bidirectional"))
      (node (ref "H1") (pin "A") (pinfunction "A_A") (pintype "passive"))
    )
    (net (code "72") (name "LED_RUN") (class "Default")
      (node (ref "D1") (pin "29") (pinfunction "PC3_29") (pintype "bidirectional"))
      (node (ref "H3") (pin "A") (pinfunction "A_A") (pintype "passive"))
    )
    (net (code "73") (name "LED_VCC") (class "Default")
      (node (ref "C6") (pin "1") (pinfunction "1_1") (pintype "passive"))
      (node (ref "C69") (pin "1") (pinfunction "1_1") (pintype "passive"))
      (node (ref "L4") (pin "1") (pinfunction "1_1") (pintype "passive"))
      (node (ref "X16") (pin "2") (pinfunction "2_2") (pintype "passive"))
    )
    (net (code "74") (name "MEAS12V") (class "Default")
      (node (ref "C47") (pin "1") (pinfunction "1_1") (pintype "passive"))
      (node (ref "D1") (pin "34") (pinfunction "PA0/WKUP_34") (pintype "bidirectional"))
      (node (ref "R36") (pin "2") (pinfunction "2_2") (pintype "passive"))
      (node (ref "R85") (pin "2") (pinfunction "2_2") (pintype "passive"))
    )
    (net (code "75") (name "Net-(C12-Pad1)") (class "Default")
      (node (ref "C12") (pin "1") (pinfunction "1_1") (pintype "passive"))
      (node (ref "R17") (pin "1") (pinfunction "1_1") (pintype "passive"))
    )
    (net (code "76") (name "Net-(D1A-BOOT0)") (class "Default")
      (node (ref "D1") (pin "138") (pinfunction "BOOT0_138") (pintype "bidirectional"))
      (node (ref "R19") (pin "2") (pinfunction "2_2") (pintype "passive"))
    )
    (net (code "77") (name "Net-(D1A-PA13{slash}TMS{slash}SWDIO)") (class "Default")
      (node (ref "D1") (pin "105") (pinfunction "PA13/TMS/SWDIO_105") (pintype "bidirectional"))
      (node (ref "R3") (pin "2") (pinfunction "2_2") (pintype "passive"))
    )
    (net (code "78") (name "Net-(D1A-PA14{slash}TCK{slash}SWCLK)") (class "Default")
      (node (ref "D1") (pin "109") (pinfunction "PA14/TCK/SWCLK_109") (pintype "bidirectional"))
      (node (ref "R4") (pin "2") (pinfunction "2_2") (pintype "passive"))
    )
    (net (code "79") (name "Net-(D1A-PB2{slash}BOOT1)") (class "Default")
      (node (ref "D1") (pin "48") (pinfunction "PB2/BOOT1_48") (pintype "bidirectional"))
      (node (ref "R20") (pin "2") (pinfunction "2_2") (pintype "passive"))
    )
    (net (code "80") (name "Net-(D1A-PH0{slash}OSCIN)") (class "Default")
      (node (ref "C23") (pin "1") (pinfunction "1_1") (pintype "passive"))
      (node (ref "D1") (pin "23") (pinfunction "PH0/OSCIN_23") (pintype "bidirectional"))
      (node (ref "G1") (pin "1") (pinfunction "X1_1") (pintype "bidirectional"))
    )
    (net (code "81") (name "Net-(D1A-PH1{slash}OSCOUT)") (class "Default")
      (node (ref "C24") (pin "1") (pinfunction "1_1") (pintype "passive"))
      (node (ref "D1") (pin "24") (pinfunction "PH1/OSCOUT_24") (pintype "bidirectional"))
      (node (ref "G1") (pin "3") (pinfunction "X2_3") (pintype "bidirectional"))
    )
    (net (code "82") (name "Net-(D1A-VCAP1)") (class "Default")
      (node (ref "C9") (pin "1") (pinfunction "1_1") (pintype "passive"))
      (node (ref "D1") (pin "71") (pinfunction "VCAP1_71") (pintype "bidirectional"))
    )
    (net (code "83") (name "Net-(D1A-VCAP2)") (class "Default")
      (node (ref "C8") (pin "1") (pinfunction "1_1") (pintype "passive"))
      (node (ref "D1") (pin "106") (pinfunction "VCAP2_106") (pintype "bidirectional"))
    )
    (net (code "84") (name "Net-(D2-Y1)") (class "Default")
      (node (ref "D2") (pin "3") (pinfunction "Y1_3") (pintype "bidirectional"))
      (node (ref "R22") (pin "1") (pinfunction "1_1") (pintype "passive"))
    )
    (net (code "85") (name "Net-(D2-Y2)") (class "Default")
      (node (ref "D2") (pin "6") (pinfunction "Y2_6") (pintype "bidirectional"))
      (node (ref "R23") (pin "1") (pinfunction "1_1") (pintype "passive"))
    )
    (net (code "86") (name "Net-(D2-Y3)") (class "Default")
      (node (ref "D2") (pin "8") (pinfunction "Y3_8") (pintype "bidirectional"))
      (node (ref "R26") (pin "1") (pinfunction "1_1") (pintype "passive"))
    )
    (net (code "87") (name "Net-(D2-Y4)") (class "Default")
      (node (ref "D2") (pin "11") (pinfunction "Y4_11") (pintype "bidirectional"))
      (node (ref "R27") (pin "1") (pinfunction "1_1") (pintype "passive"))
    )
    (net (code "88") (name "Net-(D3-Y1)") (class "Default")
      (node (ref "D3") (pin "3") (pinfunction "Y1_3") (pintype "bidirectional"))
      (node (ref "R30") (pin "1") (pinfunction "1_1") (pintype "passive"))
    )
    (net (code "89") (name "Net-(D3-Y2)") (class "Default")
      (node (ref "D3") (pin "6") (pinfunction "Y2_6") (pintype "bidirectional"))
      (node (ref "R31") (pin "1") (pinfunction "1_1") (pintype "passive"))
    )
    (net (code "90") (name "Net-(D3-Y3)") (class "Default")
      (node (ref "D3") (pin "8") (pinfunction "Y3_8") (pintype "bidirectional"))
      (node (ref "R32") (pin "1") (pinfunction "1_1") (pintype "passive"))
    )
    (net (code "91") (name "Net-(D3-Y4)") (class "Default")
      (node (ref "D3") (pin "11") (pinfunction "Y4_11") (pintype "bidirectional"))
      (node (ref "R33") (pin "1") (pinfunction "1_1") (pintype "passive"))
    )
    (net (code "92") (name "Net-(D4-Y1)") (class "Default")
      (node (ref "D4") (pin "3") (pinfunction "Y1_3") (pintype "bidirectional"))
      (node (ref "R34") (pin "1") (pinfunction "1_1") (pintype "passive"))
    )
    (net (code "93") (name "Net-(D4-Y2)") (class "Default")
      (node (ref "D4") (pin "6") (pinfunction "Y2_6") (pintype "bidirectional"))
      (node (ref "R37") (pin "1") (pinfunction "1_1") (pintype "passive"))
    )
    (net (code "94") (name "Net-(D4-Y3)") (class "Default")
      (node (ref "D4") (pin "8") (pinfunction "Y3_8") (pintype "bidirectional"))
      (node (ref "R38") (pin "1") (pinfunction "1_1") (pintype "passive"))
    )
    (net (code "95") (name "Net-(D4-Y4)") (class "Default")
      (node (ref "D4") (pin "11") (pinfunction "Y4_11") (pintype "bidirectional"))
      (node (ref "R39") (pin "1") (pinfunction "1_1") (pintype "passive"))
    )
    (net (code "96") (name "Net-(D5-Y1)") (class "Default")
      (node (ref "D5") (pin "3") (pinfunction "Y1_3") (pintype "bidirectional"))
      (node (ref "R40") (pin "1") (pinfunction "1_1") (pintype "passive"))
    )
    (net (code "97") (name "Net-(D5-Y2)") (class "Default")
      (node (ref "D5") (pin "6") (pinfunction "Y2_6") (pintype "bidirectional"))
      (node (ref "R41") (pin "1") (pinfunction "1_1") (pintype "passive"))
    )
    (net (code "98") (name "Net-(D5-Y3)") (class "Default")
      (node (ref "D5") (pin "8") (pinfunction "Y3_8") (pintype "bidirectional"))
      (node (ref "R42") (pin "1") (pinfunction "1_1") (pintype "passive"))
    )
    (net (code "99") (name "Net-(D5-Y4)") (class "Default")
      (node (ref "D5") (pin "11") (pinfunction "Y4_11") (pintype "bidirectional"))
      (node (ref "R43") (pin "1") (pinfunction "1_1") (pintype "passive"))
    )
    (net (code "100") (name "Net-(D8-A+)") (class "Default")
      (node (ref "D8") (pin "6") (pinfunction "A+_6") (pintype "bidirectional"))
      (node (ref "R58") (pin "2") (pinfunction "2_2") (pintype "passive"))
      (node (ref "V36") (pin "2") (pinfunction "2_2") (pintype "bidirectional"))
      (node (ref "X15") (pin "3") (pinfunction "3_3") (pintype "passive"))
    )
    (net (code "101") (name "Net-(D8-B-)") (class "Default")
      (node (ref "D8") (pin "7") (pinfunction "B-_7") (pintype "bidirectional"))
      (node (ref "R58") (pin "1") (pinfunction "1_1") (pintype "passive"))
      (node (ref "V36") (pin "1") (pinfunction "1_1") (pintype "bidirectional"))
      (node (ref "X15") (pin "4") (pinfunction "4_4") (pintype "passive"))
    )
    (net (code "102") (name "Net-(D9A-A)") (class "Default")
      (node (ref "C39") (pin "1") (pinfunction "1_1") (pintype "passive"))
      (node (ref "D9") (pin "1") (pinfunction "A_1") (pintype "bidirectional"))
      (node (ref "R28") (pin "2") (pinfunction "2_2") (pintype "passive"))
      (node (ref "R29") (pin "1") (pinfunction "1_1") (pintype "passive"))
    )
    (net (code "103") (name "Net-(D9B-A)") (class "Default")
      (node (ref "C40") (pin "1") (pinfunction "1_1") (pintype "passive"))
      (node (ref "D9") (pin "3") (pinfunction "A_3") (pintype "bidirectional"))
      (node (ref "R53") (pin "2") (pinfunction "2_2") (pintype "passive"))
      (node (ref "R54") (pin "1") (pinfunction "1_1") (pintype "passive"))
    )
    (net (code "104") (name "Net-(D9C-A)") (class "Default")
      (node (ref "C41") (pin "1") (pinfunction "1_1") (pintype "passive"))
      (node (ref "D9") (pin "5") (pinfunction "A_5") (pintype "bidirectional"))
      (node (ref "R55") (pin "2") (pinfunction "2_2") (pintype "passive"))
      (node (ref "R56") (pin "1") (pinfunction "1_1") (pintype "passive"))
    )
    (net (code "105") (name "Net-(D9D-A)") (class "Default")
      (node (ref "C42") (pin "1") (pinfunction "1_1") (pintype "passive"))
      (node (ref "D9") (pin "9") (pinfunction "A_9") (pintype "bidirectional"))
      (node (ref "R57") (pin "2") (pinfunction "2_2") (pintype "passive"))
      (node (ref "R60") (pin "1") (pinfunction "1_1") (pintype "passive"))
    )
    (net (code "106") (name "Net-(D9E-A)") (class "Default")
      (node (ref "C43") (pin "1") (pinfunction "1_1") (pintype "passive"))
      (node (ref "D9") (pin "11") (pinfunction "A_11") (pintype "bidirectional"))
      (node (ref "R61") (pin "2") (pinfunction "2_2") (pintype "passive"))
      (node (ref "R62") (pin "1") (pinfunction "1_1") (pintype "passive"))
    )
    (net (code "107") (name "Net-(D9F-A)") (class "Default")
      (node (ref "C44") (pin "1") (pinfunction "1_1") (pintype "passive"))
      (node (ref "D9") (pin "13") (pinfunction "A_13") (pintype "bidirectional"))
      (node (ref "R63") (pin "2") (pinfunction "2_2") (pintype "passive"))
      (node (ref "R64") (pin "1") (pinfunction "1_1") (pintype "passive"))
    )
    (net (code "108") (name "Net-(D11A-A)") (class "Default")
      (node (ref "C45") (pin "1") (pinfunction "1_1") (pintype "passive"))
      (node (ref "D11") (pin "1") (pinfunction "A_1") (pintype "bidirectional"))
      (node (ref "R65") (pin "2") (pinfunction "2_2") (pintype "passive"))
      (node (ref "R66") (pin "1") (pinfunction "1_1") (pintype "passive"))
    )
    (net (code "109") (name "Net-(D11B-A)") (class "Default")
      (node (ref "C46") (pin "1") (pinfunction "1_1") (pintype "passive"))
      (node (ref "D11") (pin "3") (pinfunction "A_3") (pintype "bidirectional"))
      (node (ref "R67") (pin "2") (pinfunction "2_2") (pintype "passive"))
      (node (ref "R68") (pin "1") (pinfunction "1_1") (pintype "passive"))
    )
    (net (code "110") (name "Net-(D11C-A)") (class "Default")
      (node (ref "C48") (pin "1") (pinfunction "1_1") (pintype "passive"))
      (node (ref "D11") (pin "5") (pinfunction "A_5") (pintype "bidirectional"))
      (node (ref "R69") (pin "2") (pinfunction "2_2") (pintype "passive"))
      (node (ref "R70") (pin "1") (pinfunction "1_1") (pintype "passive"))
    )
    (net (code "111") (name "Net-(D11D-A)") (class "Default")
      (node (ref "C50") (pin "1") (pinfunction "1_1") (pintype "passive"))
      (node (ref "D11") (pin "9") (pinfunction "A_9") (pintype "bidirectional"))
      (node (ref "R71") (pin "2") (pinfunction "2_2") (pintype "passive"))
      (node (ref "R72") (pin "1") (pinfunction "1_1") (pintype "passive"))
    )
    (net (code "112") (name "Net-(D11E-A)") (class "Default")
      (node (ref "C51") (pin "1") (pinfunction "1_1") (pintype "passive"))
      (node (ref "D11") (pin "11") (pinfunction "A_11") (pintype "bidirectional"))
      (node (ref "R73") (pin "2") (pinfunction "2_2") (pintype "passive"))
      (node (ref "R74") (pin "1") (pinfunction "1_1") (pintype "passive"))
    )
    (net (code "113") (name "Net-(D11F-A)") (class "Default")
      (node (ref "C52") (pin "1") (pinfunction "1_1") (pintype "passive"))
      (node (ref "D11") (pin "13") (pinfunction "A_13") (pintype "bidirectional"))
      (node (ref "R75") (pin "2") (pinfunction "2_2") (pintype "passive"))
      (node (ref "R76") (pin "1") (pinfunction "1_1") (pintype "passive"))
    )
    (net (code "114") (name "Net-(D12A-A)") (class "Default")
      (node (ref "C56") (pin "1") (pinfunction "1_1") (pintype "passive"))
      (node (ref "D12") (pin "1") (pinfunction "A_1") (pintype "bidirectional"))
      (node (ref "R77") (pin "2") (pinfunction "2_2") (pintype "passive"))
      (node (ref "R78") (pin "1") (pinfunction "1_1") (pintype "passive"))
    )
    (net (code "115") (name "Net-(D12B-A)") (class "Default")
      (node (ref "C57") (pin "1") (pinfunction "1_1") (pintype "passive"))
      (node (ref "D12") (pin "3") (pinfunction "A_3") (pintype "bidirectional"))
      (node (ref "R79") (pin "2") (pinfunction "2_2") (pintype "passive"))
      (node (ref "R80") (pin "1") (pinfunction "1_1") (pintype "passive"))
    )
    (net (code "116") (name "Net-(D12C-A)") (class "Default")
      (node (ref "C59") (pin "1") (pinfunction "1_1") (pintype "passive"))
      (node (ref "D12") (pin "5") (pinfunction "A_5") (pintype "bidirectional"))
      (node (ref "R81") (pin "2") (pinfunction "2_2") (pintype "passive"))
      (node (ref "R82") (pin "1") (pinfunction "1_1") (pintype "passive"))
    )
    (net (code "117") (name "Net-(D12D-A)") (class "Default")
      (node (ref "C60") (pin "1") (pinfunction "1_1") (pintype "passive"))
      (node (ref "D12") (pin "9") (pinfunction "A_9") (pintype "bidirectional"))
      (node (ref "R83") (pin "2") (pinfunction "2_2") (pintype "passive"))
      (node (ref "R84") (pin "1") (pinfunction "1_1") (pintype "passive"))
    )
    (net (code "118") (name "Net-(D13-Y1)") (class "Default")
      (node (ref "D13") (pin "3") (pinfunction "Y1_3") (pintype "bidirectional"))
      (node (ref "R89") (pin "1") (pinfunction "1_1") (pintype "passive"))
    )
    (net (code "119") (name "Net-(D13-Y2)") (class "Default")
      (node (ref "D13") (pin "6") (pinfunction "Y2_6") (pintype "bidirectional"))
      (node (ref "R90") (pin "1") (pinfunction "1_1") (pintype "passive"))
    )
    (net (code "120") (name "Net-(D13-Y3)") (class "Default")
      (node (ref "D13") (pin "8") (pinfunction "Y3_8") (pintype "bidirectional"))
      (node (ref "R91") (pin "1") (pinfunction "1_1") (pintype "passive"))
    )
    (net (code "121") (name "Net-(D13-Y4)") (class "Default")
      (node (ref "D13") (pin "11") (pinfunction "Y4_11") (pintype "bidirectional"))
      (node (ref "R92") (pin "1") (pinfunction "1_1") (pintype "passive"))
    )
    (net (code "122") (name "Net-(D14-Y1)") (class "Default")
      (node (ref "D14") (pin "3") (pinfunction "Y1_3") (pintype "bidirectional"))
      (node (ref "R93") (pin "1") (pinfunction "1_1") (pintype "passive"))
    )
    (net (code "123") (name "Net-(D14-Y2)") (class "Default")
      (node (ref "D14") (pin "6") (pinfunction "Y2_6") (pintype "bidirectional"))
      (node (ref "R94") (pin "1") (pinfunction "1_1") (pintype "passive"))
    )
    (net (code "124") (name "Net-(D14-Y3)") (class "Default")
      (node (ref "D14") (pin "8") (pinfunction "Y3_8") (pintype "bidirectional"))
      (node (ref "R95") (pin "1") (pinfunction "1_1") (pintype "passive"))
    )
    (net (code "125") (name "Net-(D14-Y4)") (class "Default")
      (node (ref "D14") (pin "11") (pinfunction "Y4_11") (pintype "bidirectional"))
      (node (ref "R96") (pin "1") (pinfunction "1_1") (pintype "passive"))
    )
    (net (code "126") (name "Net-(H1-PadC)") (class "Default")
      (node (ref "H1") (pin "C") (pinfunction "C_C") (pintype "passive"))
      (node (ref "R18") (pin "2") (pinfunction "2_2") (pintype "passive"))
    )
    (net (code "127") (name "Net-(H2-PadC)") (class "Default")
      (node (ref "H2") (pin "C") (pinfunction "C_C") (pintype "passive"))
      (node (ref "R24") (pin "2") (pinfunction "2_2") (pintype "passive"))
    )
    (net (code "128") (name "Net-(H3-PadC)") (class "Default")
      (node (ref "H3") (pin "C") (pinfunction "C_C") (pintype "passive"))
      (node (ref "R25") (pin "2") (pinfunction "2_2") (pintype "passive"))
    )
    (net (code "129") (name "Net-(N1-BOOT)") (class "Default")
      (node (ref "C4") (pin "2") (pinfunction "2_2") (pintype "passive"))
      (node (ref "N1") (pin "1") (pinfunction "BOOT_1") (pintype "bidirectional"))
    )
    (net (code "130") (name "Net-(N1-SENSE)") (class "Default")
      (node (ref "N1") (pin "4") (pinfunction "SENSE_4") (pintype "bidirectional"))
      (node (ref "R1") (pin "2") (pinfunction "2_2") (pintype "passive"))
      (node (ref "R2") (pin "1") (pinfunction "1_1") (pintype "passive"))
    )
    (net (code "131") (name "Net-(N2-BOOT)") (class "Default")
      (node (ref "C32") (pin "2") (pinfunction "2_2") (pintype "passive"))
      (node (ref "N2") (pin "1") (pinfunction "BOOT_1") (pintype "bidirectional"))
    )
    (net (code "132") (name "Net-(N2-SENSE)") (class "Default")
      (node (ref "N2") (pin "4") (pinfunction "SENSE_4") (pintype "bidirectional"))
      (node (ref "R49") (pin "2") (pinfunction "2_2") (pintype "passive"))
      (node (ref "R50") (pin "1") (pinfunction "1_1") (pintype "passive"))
    )
    (net (code "133") (name "Net-(V1-B)") (class "Default")
      (node (ref "R5") (pin "1") (pinfunction "1_1") (pintype "passive"))
      (node (ref "R6") (pin "2") (pinfunction "2_2") (pintype "passive"))
      (node (ref "R7") (pin "1") (pinfunction "1_1") (pintype "passive"))
      (node (ref "V1") (pin "1") (pinfunction "B_1") (pintype "passive"))
    )
    (net (code "134") (name "Net-(V1-E)") (class "Default")
      (node (ref "R21") (pin "2") (pinfunction "2_2") (pintype "passive"))
      (node (ref "V1") (pin "2") (pinfunction "E_2") (pintype "passive"))
    )
    (net (code "135") (name "Net-(V2A-D-Pad5)") (class "Default")
      (node (ref "V2") (pin "5") (pinfunction "D_5") (pintype "passive"))
      (node (ref "V2") (pin "6") (pinfunction "D_6") (pintype "passive"))
      (node (ref "V8") (pin "A") (pinfunction "A_A") (pintype "passive"))
    )
    (net (code "136") (name "Net-(V2A-G)") (class "Default")
      (node (ref "R12") (pin "1") (pinfunction "1_1") (pintype "passive"))
      (node (ref "V2") (pin "4") (pinfunction "G_4") (pintype "passive"))
      (node (ref "V3") (pin "3") (pinfunction "D_3") (pintype "passive"))
    )
    (net (code "137") (name "Net-(V2B-G)") (class "Default")
      (node (ref "R8") (pin "1") (pinfunction "1_1") (pintype "passive"))
      (node (ref "V2") (pin "2") (pinfunction "G_2") (pintype "passive"))
      (node (ref "V5") (pin "3") (pinfunction "D_3") (pintype "passive"))
    )
    (net (code "138") (name "Net-(V4A-G)") (class "Default")
      (node (ref "R9") (pin "1") (pinfunction "1_1") (pintype "passive"))
      (node (ref "V4") (pin "4") (pinfunction "G_4") (pintype "passive"))
      (node (ref "V7") (pin "3") (pinfunction "D_3") (pintype "passive"))
    )
    (net (code "139") (name "Net-(V4B-G)") (class "Default")
      (node (ref "R10") (pin "1") (pinfunction "1_1") (pintype "passive"))
      (node (ref "V4") (pin "2") (pinfunction "G_2") (pintype "passive"))
      (node (ref "V9") (pin "3") (pinfunction "D_3") (pintype "passive"))
    )
    (net (code "140") (name "Net-(V10-PadA)") (class "Default")
      (node (ref "V10") (pin "A") (pinfunction "A_A") (pintype "passive"))
      (node (ref "V2") (pin "7") (pinfunction "D_7") (pintype "passive"))
      (node (ref "V2") (pin "8") (pinfunction "D_8") (pintype "passive"))
    )
    (net (code "141") (name "Net-(V11-PadA)") (class "Default")
      (node (ref "V11") (pin "A") (pinfunction "A_A") (pintype "passive"))
      (node (ref "V4") (pin "5") (pinfunction "D_5") (pintype "passive"))
      (node (ref "V4") (pin "6") (pinfunction "D_6") (pintype "passive"))
    )
    (net (code "142") (name "Net-(V12-PadA)") (class "Default")
      (node (ref "V12") (pin "A") (pinfunction "A_A") (pintype "passive"))
      (node (ref "V4") (pin "7") (pinfunction "D_7") (pintype "passive"))
      (node (ref "V4") (pin "8") (pinfunction "D_8") (pintype "passive"))
    )
    (net (code "143") (name "Net-(V24-C)") (class "Default")
      (node (ref "Q1") (pin "1") (pinfunction "1_1") (pintype "passive"))
      (node (ref "V24") (pin "1") (pinfunction "C_1") (pintype "passive"))
      (node (ref "V8") (pin "C") (pinfunction "C_C") (pintype "passive"))
    )
    (net (code "144") (name "Net-(V24-C1)") (class "Default")
      (node (ref "Q2") (pin "1") (pinfunction "1_1") (pintype "passive"))
      (node (ref "V10") (pin "C") (pinfunction "C_C") (pintype "passive"))
      (node (ref "V24") (pin "3") (pinfunction "C1_3") (pintype "passive"))
    )
    (net (code "145") (name "Net-(V24-C2)") (class "Default")
      (node (ref "Q3") (pin "1") (pinfunction "1_1") (pintype "passive"))
      (node (ref "V11") (pin "C") (pinfunction "C_C") (pintype "passive"))
      (node (ref "V24") (pin "4") (pinfunction "C2_4") (pintype "passive"))
    )
    (net (code "146") (name "Net-(V24-C3)") (class "Default")
      (node (ref "Q4") (pin "1") (pinfunction "1_1") (pintype "passive"))
      (node (ref "V12") (pin "C") (pinfunction "C_C") (pintype "passive"))
      (node (ref "V24") (pin "6") (pinfunction "C3_6") (pintype "passive"))
    )
    (net (code "147") (name "Net-(X8-ATT)") (class "Default")
      (node (ref "R87") (pin "1") (pinfunction "1_1") (pintype "passive"))
      (node (ref "X8") (pin "6") (pinfunction "ATT_6") (pintype "passive"))
    )
    (net (code "148") (name "Net-(X8-CLK)") (class "Default")
      (node (ref "R88") (pin "1") (pinfunction "1_1") (pintype "passive"))
      (node (ref "X8") (pin "7") (pinfunction "CLK_7") (pintype "passive"))
    )
    (net (code "149") (name "Net-(X8-CMD)") (class "Default")
      (node (ref "R86") (pin "1") (pinfunction "1_1") (pintype "passive"))
      (node (ref "X8") (pin "2") (pinfunction "CMD_2") (pintype "passive"))
    )
    (net (code "150") (name "Net-(X8-DATA)") (class "Default")
      (node (ref "R35") (pin "1") (pinfunction "1_1") (pintype "passive"))
      (node (ref "X8") (pin "1") (pinfunction "DATA_1") (pintype "passive"))
    )
    (net (code "151") (name "OUT1") (class "Default")
      (node (ref "Q1") (pin "2") (pinfunction "2_2") (pintype "passive"))
      (node (ref "X3") (pin "1") (pinfunction "1_1") (pintype "passive"))
    )
    (net (code "152") (name "OUT2") (class "Default")
      (node (ref "Q2") (pin "2") (pinfunction "2_2") (pintype "passive"))
      (node (ref "X3") (pin "3") (pinfunction "3_3") (pintype "passive"))
    )
    (net (code "153") (name "OUT3") (class "Default")
      (node (ref "Q3") (pin "2") (pinfunction "2_2") (pintype "passive"))
      (node (ref "X3") (pin "5") (pinfunction "5_5") (pintype "passive"))
    )
    (net (code "154") (name "OUT4") (class "Default")
      (node (ref "Q4") (pin "2") (pinfunction "2_2") (pintype "passive"))
      (node (ref "X3") (pin "7") (pinfunction "7_7") (pintype "passive"))
    )
    (net (code "155") (name "OUT_1") (class "Default")
      (node (ref "D1") (pin "26") (pinfunction "PC0_26") (pintype "bidirectional"))
      (node (ref "R11") (pin "1") (pinfunction "1_1") (pintype "passive"))
      (node (ref "V3") (pin "1") (pinfunction "G_1") (pintype "passive"))
    )
    (net (code "156") (name "OUT_2") (class "Default")
      (node (ref "D1") (pin "27") (pinfunction "PC1_27") (pintype "bidirectional"))
      (node (ref "R13") (pin "1") (pinfunction "1_1") (pintype "passive"))
      (node (ref "V5") (pin "1") (pinfunction "G_1") (pintype "passive"))
    )
    (net (code "157") (name "OUT_3") (class "Default")
      (node (ref "D1") (pin "69") (pinfunction "PB10_69") (pintype "bidirectional"))
      (node (ref "R14") (pin "1") (pinfunction "1_1") (pintype "passive"))
      (node (ref "V7") (pin "1") (pinfunction "G_1") (pintype "passive"))
    )
    (net (code "158") (name "OUT_4") (class "Default")
      (node (ref "D1") (pin "70") (pinfunction "PB11_70") (pintype "bidirectional"))
      (node (ref "R15") (pin "1") (pinfunction "1_1") (pintype "passive"))
      (node (ref "V9") (pin "1") (pinfunction "G_1") (pintype "passive"))
    )
    (net (code "159") (name "PH3V3") (class "Default")
      (node (ref "C32") (pin "1") (pinfunction "1_1") (pintype "passive"))
      (node (ref "L6") (pin "1") (pinfunction "A_1") (pintype "bidirectional"))
      (node (ref "N2") (pin "8") (pinfunction "PH_8") (pintype "bidirectional"))
      (node (ref "V18") (pin "C") (pinfunction "C_C") (pintype "passive"))
    )
    (net (code "160") (name "PH5V") (class "Default")
      (node (ref "C4") (pin "1") (pinfunction "1_1") (pintype "passive"))
      (node (ref "L1") (pin "1") (pinfunction "1_1") (pintype "passive"))
      (node (ref "N1") (pin "8") (pinfunction "PH_8") (pintype "bidirectional"))
      (node (ref "V13") (pin "2") (pinfunction "C_2") (pintype "passive"))
    )
    (net (code "161") (name "PSVCC") (class "Default")
      (node (ref "C61") (pin "1") (pinfunction "1_1") (pintype "passive"))
      (node (ref "C62") (pin "1") (pinfunction "1_1") (pintype "passive"))
      (node (ref "L7") (pin "1") (pinfunction "1_1") (pintype "passive"))
      (node (ref "X8") (pin "5") (pinfunction "VCC_5") (pintype "passive"))
    )
    (net (code "162") (name "PULSE0") (class "Default")
      (node (ref "R30") (pin "2") (pinfunction "2_2") (pintype "passive"))
      (node (ref "V14") (pin "6") (pinfunction "C3_6") (pintype "passive"))
      (node (ref "X4") (pin "1") (pinfunction "1_1") (pintype "passive"))
    )
    (net (code "163") (name "PULSE1") (class "Default")
      (node (ref "R32") (pin "2") (pinfunction "2_2") (pintype "passive"))
      (node (ref "V14") (pin "3") (pinfunction "C1_3") (pintype "passive"))
      (node (ref "X4") (pin "3") (pinfunction "3_3") (pintype "passive"))
    )
    (net (code "164") (name "PULSE2") (class "Default")
      (node (ref "R34") (pin "2") (pinfunction "2_2") (pintype "passive"))
      (node (ref "V15") (pin "6") (pinfunction "C3_6") (pintype "passive"))
      (node (ref "X5") (pin "1") (pinfunction "1_1") (pintype "passive"))
    )
    (net (code "165") (name "PULSE3") (class "Default")
      (node (ref "R38") (pin "2") (pinfunction "2_2") (pintype "passive"))
      (node (ref "V15") (pin "3") (pinfunction "C1_3") (pintype "passive"))
      (node (ref "X5") (pin "3") (pinfunction "3_3") (pintype "passive"))
    )
    (net (code "166") (name "PULSE4") (class "Default")
      (node (ref "R40") (pin "2") (pinfunction "2_2") (pintype "passive"))
      (node (ref "V17") (pin "6") (pinfunction "C3_6") (pintype "passive"))
      (node (ref "X7") (pin "1") (pinfunction "1_1") (pintype "passive"))
    )
    (net (code "167") (name "PULSE5") (class "Default")
      (node (ref "R42") (pin "2") (pinfunction "2_2") (pintype "passive"))
      (node (ref "V17") (pin "3") (pinfunction "C1_3") (pintype "passive"))
      (node (ref "X7") (pin "3") (pinfunction "3_3") (pintype "passive"))
    )
    (net (code "168") (name "PULSE_0") (class "Default")
      (node (ref "D1") (pin "81") (pinfunction "PD12_81") (pintype "bidirectional"))
      (node (ref "D3") (pin "2") (pinfunction "A1_2") (pintype "bidirectional"))
    )
    (net (code "169") (name "PULSE_1") (class "Default")
      (node (ref "D3") (pin "9") (pinfunction "A3_9") (pintype "bidirectional"))
    )
    (net (code "170") (name "PULSE_2") (class "Default")
      (node (ref "D1") (pin "96") (pinfunction "PC6_96") (pintype "bidirectional"))
      (node (ref "D4") (pin "2") (pinfunction "A1_2") (pintype "bidirectional"))
    )
    (net (code "171") (name "PULSE_3") (class "Default")
      (node (ref "D1") (pin "4") (pinfunction "PE5_4") (pintype "bidirectional"))
      (node (ref "D4") (pin "9") (pinfunction "A3_9") (pintype "bidirectional"))
    )
    (net (code "172") (name "PULSE_4") (class "Default")
      (node (ref "D1") (pin "139") (pinfunction "PB8_139") (pintype "bidirectional"))
      (node (ref "D5") (pin "2") (pinfunction "A1_2") (pintype "bidirectional"))
    )
    (net (code "173") (name "PULSE_5") (class "Default")
      (node (ref "D1") (pin "140") (pinfunction "PB9_140") (pintype "bidirectional"))
      (node (ref "D5") (pin "9") (pinfunction "A3_9") (pintype "bidirectional"))
    )
    (net (code "174") (name "RESETL") (class "Default")
      (node (ref "D1") (pin "25") (pinfunction "RSTL_25") (pintype "bidirectional"))
      (node (ref "D10") (pin "1") (pinfunction "RESET_1") (pintype "bidirectional"))
      (node (ref "R16") (pin "1") (pinfunction "1_1") (pintype "passive"))
      (node (ref "X1") (pin "A1") (pinfunction "1_A1") (pintype "passive"))
    )
    (net (code "175") (name "SERVO1") (class "Default")
      (node (ref "R22") (pin "2") (pinfunction "2_2") (pintype "passive"))
      (node (ref "R45") (pin "2") (pinfunction "2_2") (pintype "passive"))
      (node (ref "V6") (pin "6") (pinfunction "C3_6") (pintype "passive"))
      (node (ref "X2") (pin "2") (pinfunction "2_2") (pintype "passive"))
    )
    (net (code "176") (name "SERVO2") (class "Default")
      (node (ref "R23") (pin "2") (pinfunction "2_2") (pintype "passive"))
      (node (ref "R46") (pin "2") (pinfunction "2_2") (pintype "passive"))
      (node (ref "V6") (pin "4") (pinfunction "C2_4") (pintype "passive"))
      (node (ref "X2") (pin "5") (pinfunction "5_5") (pintype "passive"))
    )
    (net (code "177") (name "SERVO3") (class "Default")
      (node (ref "R26") (pin "2") (pinfunction "2_2") (pintype "passive"))
      (node (ref "R47") (pin "2") (pinfunction "2_2") (pintype "passive"))
      (node (ref "V6") (pin "3") (pinfunction "C1_3") (pintype "passive"))
      (node (ref "X2") (pin "8") (pinfunction "8_8") (pintype "passive"))
    )
    (net (code "178") (name "SERVO_PWM_1") (class "Default")
      (node (ref "D1") (pin "42") (pinfunction "PA6_42") (pintype "bidirectional"))
      (node (ref "D2") (pin "2") (pinfunction "A1_2") (pintype "bidirectional"))
    )
    (net (code "179") (name "SERVO_PWM_2") (class "Default")
      (node (ref "D1") (pin "43") (pinfunction "PA7_43") (pintype "bidirectional"))
      (node (ref "D2") (pin "5") (pinfunction "A2_5") (pintype "bidirectional"))
    )
    (net (code "180") (name "SERVO_PWM_3") (class "Default")
      (node (ref "D1") (pin "46") (pinfunction "PB0_46") (pintype "bidirectional"))
      (node (ref "D2") (pin "9") (pinfunction "A3_9") (pintype "bidirectional"))
    )
    (net (code "181") (name "SERVO_VCC") (class "Default")
      (node (ref "C68") (pin "1") (pinfunction "1_1") (pintype "passive"))
      (node (ref "C7") (pin "1") (pinfunction "1_1") (pintype "passive"))
      (node (ref "L5") (pin "1") (pinfunction "1_1") (pintype "passive"))
      (node (ref "X2") (pin "1") (pinfunction "1_1") (pintype "passive"))
      (node (ref "X2") (pin "4") (pinfunction "4_4") (pintype "passive"))
      (node (ref "X2") (pin "7") (pinfunction "7_7") (pintype "passive"))
    )
    (net (code "182") (name "SPARE1") (class "Default")
      (node (ref "R95") (pin "2") (pinfunction "2_2") (pintype "passive"))
      (node (ref "V25") (pin "3") (pinfunction "C1_3") (pintype "passive"))
      (node (ref "X12") (pin "3") (pinfunction "3_3") (pintype "passive"))
    )
    (net (code "183") (name "SPARE2") (class "Default")
      (node (ref "R96") (pin "2") (pinfunction "2_2") (pintype "passive"))
      (node (ref "V25") (pin "1") (pinfunction "C_1") (pintype "passive"))
      (node (ref "X12") (pin "4") (pinfunction "4_4") (pintype "passive"))
    )
    (net (code "184") (name "SPARE_1") (class "Default")
      (node (ref "D1") (pin "91") (pinfunction "PG6_91") (pintype "bidirectional"))
      (node (ref "D14") (pin "9") (pinfunction "A3_9") (pintype "bidirectional"))
    )
    (net (code "185") (name "SPARE_2") (class "Default")
      (node (ref "D1") (pin "92") (pinfunction "PG7_92") (pintype "bidirectional"))
      (node (ref "D14") (pin "12") (pinfunction "A4_12") (pintype "bidirectional"))
    )
    (net (code "186") (name "SPI1CLK") (class "Default")
      (node (ref "D1") (pin "133") (pinfunction "PB3/TDO_133") (pintype "bidirectional"))
      (node (ref "R88") (pin "2") (pinfunction "2_2") (pintype "passive"))
    )
    (net (code "187") (name "SPI1MISO") (class "Default")
      (node (ref "D1") (pin "134") (pinfunction "PB4/TRSTL_134") (pintype "bidirectional"))
      (node (ref "R35") (pin "2") (pinfunction "2_2") (pintype "passive"))
    )
    (net (code "188") (name "SPI1MOSI") (class "Default")
      (node (ref "D1") (pin "135") (pinfunction "PB5_135") (pintype "bidirectional"))
      (node (ref "R86") (pin "2") (pinfunction "2_2") (pintype "passive"))
    )
    (net (code "189") (name "SPI_CS_PS2_N") (class "Default")
      (node (ref "D1") (pin "35") (pinfunction "PA1_35") (pintype "bidirectional"))
      (node (ref "R87") (pin "2") (pinfunction "2_2") (pintype "passive"))
    )
    (net (code "190") (name "SWCLK") (class "Default")
      (node (ref "R4") (pin "1") (pinfunction "1_1") (pintype "passive"))
      (node (ref "X1") (pin "A3") (pinfunction "3_A3") (pintype "passive"))
    )
    (net (code "191") (name "SWDIO") (class "Default")
      (node (ref "R3") (pin "1") (pinfunction "1_1") (pintype "passive"))
      (node (ref "X1") (pin "A2") (pinfunction "2_A2") (pintype "passive"))
    )
    (net (code "192") (name "USART1RX") (class "Default")
      (node (ref "D1") (pin "102") (pinfunction "PA10_102") (pintype "bidirectional"))
      (node (ref "D8") (pin "1") (pinfunction "RO_1") (pintype "output"))
    )
    (net (code "193") (name "USART1TX") (class "Default")
      (node (ref "D1") (pin "101") (pinfunction "PA9_101") (pintype "bidirectional"))
      (node (ref "D8") (pin "4") (pinfunction "DI_4") (pintype "input"))
    )
    (net (code "194") (name "USART1TXE") (class "Default")
      (node (ref "D1") (pin "86") (pinfunction "PD15_86") (pintype "bidirectional"))
      (node (ref "D8") (pin "2") (pinfunction "RE~{}_2") (pintype "input"))
      (node (ref "D8") (pin "3") (pinfunction "DE_3") (pintype "input"))
      (node (ref "R59") (pin "2") (pinfunction "2_2") (pintype "passive"))
    )
    (net (code "195") (name "USART2TX") (class "Default")
      (node (ref "D1") (pin "36") (pinfunction "PA2_36") (pintype "bidirectional"))
      (node (ref "D2") (pin "12") (pinfunction "A4_12") (pintype "bidirectional"))
    )
    (net (code "196") (name "USART3RX") (class "Default")
      (node (ref "D1") (pin "78") (pinfunction "PD9_78") (pintype "bidirectional"))
      (node (ref "X1") (pin "A4") (pinfunction "4_A4") (pintype "passive"))
    )
    (net (code "197") (name "USART3TX") (class "Default")
      (node (ref "D1") (pin "77") (pinfunction "PD8_77") (pintype "bidirectional"))
      (node (ref "X1") (pin "A5") (pinfunction "5_A5") (pintype "passive"))
    )
    (net (code "198") (name "USBRENUM") (class "Default")
      (node (ref "D1") (pin "76") (pinfunction "PB15_76") (pintype "bidirectional"))
      (node (ref "R5") (pin "2") (pinfunction "2_2") (pintype "passive"))
    )
    (net (code "199") (name "USB_DM") (class "Default")
      (node (ref "D1") (pin "103") (pinfunction "PA11_103") (pintype "bidirectional"))
      (node (ref "V26") (pin "4") (pinfunction "D_4") (pintype "bidirectional"))
      (node (ref "X18") (pin "2") (pinfunction "2_2") (pintype "passive"))
    )
    (net (code "200") (name "USB_DP") (class "Default")
      (node (ref "D1") (pin "104") (pinfunction "PA12_104") (pintype "bidirectional"))
      (node (ref "R21") (pin "1") (pinfunction "1_1") (pintype "passive"))
      (node (ref "V26") (pin "3") (pinfunction "C_3") (pintype "bidirectional"))
      (node (ref "X18") (pin "3") (pinfunction "3_3") (pintype "passive"))
    )
    (net (code "201") (name "VDDA") (class "Default")
      (node (ref "C10") (pin "1") (pinfunction "1_1") (pintype "passive"))
      (node (ref "C11") (pin "1") (pinfunction "1_1") (pintype "passive"))
      (node (ref "D1") (pin "33") (pinfunction "VDDA_33") (pintype "bidirectional"))
      (node (ref "L2") (pin "1") (pinfunction "1_1") (pintype "passive"))
    )
    (net (code "202") (name "VDDAREF") (class "Default")
      (node (ref "C54") (pin "1") (pinfunction "1_1") (pintype "passive"))
      (node (ref "C55") (pin "1") (pinfunction "1_1") (pintype "passive"))
      (node (ref "L3") (pin "1") (pinfunction "1_1") (pintype "passive"))
      (node (ref "N3") (pin "1") (pinfunction "VDD_1") (pintype "bidirectional"))
      (node (ref "N3") (pin "3") (pinfunction "SHDNL_3") (pintype "power_in"))
    )
    (net (code "203") (name "VREF25") (class "Default")
      (node (ref "D1") (pin "32") (pinfunction "VREF+_32") (pintype "bidirectional"))
      (node (ref "N3") (pin "7") (pinfunction "OUT_7") (pintype "bidirectional"))
      (node (ref "N3") (pin "8") (pinfunction "FEEDBACK_8") (pintype "input"))
      (node (ref "R17") (pin "2") (pinfunction "2_2") (pintype "passive"))
    )
    (net (code "204") (name "VUSB") (class "Default")
      (node (ref "R7") (pin "2") (pinfunction "2_2") (pintype "passive"))
      (node (ref "V26") (pin "5") (pinfunction "VCC_5") (pintype "bidirectional"))
      (node (ref "X18") (pin "1") (pinfunction "1_1") (pintype "passive"))
    )
    (net (code "205") (name "unconnected-(D1A-PA15{slash}TDI-Pad110)") (class "Default")
      (node (ref "D1") (pin "110") (pinfunction "PA15/TDI_110") (pintype "bidirectional"))
    )
    (net (code "206") (name "unconnected-(D1B-PA3-Pad37)") (class "Default")
      (node (ref "D1") (pin "37") (pinfunction "PA3_37") (pintype "bidirectional"))
    )
    (net (code "207") (name "unconnected-(D1B-PA4-Pad40)") (class "Default")
      (node (ref "D1") (pin "40") (pinfunction "PA4_40") (pintype "bidirectional"))
    )
    (net (code "208") (name "unconnected-(D1B-PA5-Pad41)") (class "Default")
      (node (ref "D1") (pin "41") (pinfunction "PA5_41") (pintype "bidirectional"))
    )
    (net (code "209") (name "unconnected-(D1B-PA8-Pad100)") (class "Default")
      (node (ref "D1") (pin "100") (pinfunction "PA8_100") (pintype "bidirectional"))
    )
    (net (code "210") (name "unconnected-(D1B-PB1-Pad47)") (class "Default")
      (node (ref "D1") (pin "47") (pinfunction "PB1_47") (pintype "bidirectional"))
    )
    (net (code "211") (name "unconnected-(D1B-PB12-Pad73)") (class "Default")
      (node (ref "D1") (pin "73") (pinfunction "PB12_73") (pintype "bidirectional"))
    )
    (net (code "212") (name "unconnected-(D1B-PB13-Pad74)") (class "Default")
      (node (ref "D1") (pin "74") (pinfunction "PB13_74") (pintype "bidirectional"))
    )
    (net (code "213") (name "unconnected-(D1B-PB14-Pad75)") (class "Default")
      (node (ref "D1") (pin "75") (pinfunction "PB14_75") (pintype "bidirectional"))
    )
    (net (code "214") (name "unconnected-(D1B-PC5-Pad45)") (class "Default")
      (node (ref "D1") (pin "45") (pinfunction "PC5_45") (pintype "bidirectional"))
    )
    (net (code "215") (name "unconnected-(D1B-PC7-Pad97)") (class "Default")
      (node (ref "D1") (pin "97") (pinfunction "PC7_97") (pintype "bidirectional"))
    )
    (net (code "216") (name "unconnected-(D1B-PD10-Pad79)") (class "Default")
      (node (ref "D1") (pin "79") (pinfunction "PD10_79") (pintype "bidirectional"))
    )
    (net (code "217") (name "unconnected-(D1B-PD11-Pad80)") (class "Default")
      (node (ref "D1") (pin "80") (pinfunction "PD11_80") (pintype "bidirectional"))
    )
    (net (code "218") (name "unconnected-(D1B-PD13-Pad82)") (class "Default")
      (node (ref "D1") (pin "82") (pinfunction "PD13_82") (pintype "bidirectional"))
    )
    (net (code "219") (name "unconnected-(D1B-PD14-Pad85)") (class "Default")
      (node (ref "D1") (pin "85") (pinfunction "PD14_85") (pintype "bidirectional"))
    )
    (net (code "220") (name "unconnected-(D1C-PE0-Pad141)") (class "Default")
      (node (ref "D1") (pin "141") (pinfunction "PE0_141") (pintype "bidirectional"))
    )
    (net (code "221") (name "unconnected-(D1C-PE1-Pad142)") (class "Default")
      (node (ref "D1") (pin "142") (pinfunction "PE1_142") (pintype "bidirectional"))
    )
    (net (code "222") (name "unconnected-(D1C-PE2-Pad1)") (class "Default")
      (node (ref "D1") (pin "1") (pinfunction "PE2_1") (pintype "bidirectional"))
    )
    (net (code "223") (name "unconnected-(D1C-PE3-Pad2)") (class "Default")
      (node (ref "D1") (pin "2") (pinfunction "PE3_2") (pintype "bidirectional"))
    )
    (net (code "224") (name "unconnected-(D1C-PE4-Pad3)") (class "Default")
      (node (ref "D1") (pin "3") (pinfunction "PE4_3") (pintype "bidirectional"))
    )
    (net (code "225") (name "unconnected-(D1C-PE6-Pad5)") (class "Default")
      (node (ref "D1") (pin "5") (pinfunction "PE6_5") (pintype "bidirectional"))
    )
    (net (code "226") (name "unconnected-(D1C-PE7-Pad58)") (class "Default")
      (node (ref "D1") (pin "58") (pinfunction "PE7_58") (pintype "bidirectional"))
    )
    (net (code "227") (name "unconnected-(D1C-PE15-Pad68)") (class "Default")
      (node (ref "D1") (pin "68") (pinfunction "PE15_68") (pintype "bidirectional"))
    )
    (net (code "228") (name "unconnected-(D1C-PF0-Pad10)") (class "Default")
      (node (ref "D1") (pin "10") (pinfunction "PF0_10") (pintype "bidirectional"))
    )
    (net (code "229") (name "unconnected-(D1C-PF1-Pad11)") (class "Default")
      (node (ref "D1") (pin "11") (pinfunction "PF1_11") (pintype "bidirectional"))
    )
    (net (code "230") (name "unconnected-(D1C-PF2-Pad12)") (class "Default")
      (node (ref "D1") (pin "12") (pinfunction "PF2_12") (pintype "bidirectional"))
    )
    (net (code "231") (name "unconnected-(D1C-PF3-Pad13)") (class "Default")
      (node (ref "D1") (pin "13") (pinfunction "PF3_13") (pintype "bidirectional"))
    )
    (net (code "232") (name "unconnected-(D1C-PF4-Pad14)") (class "Default")
      (node (ref "D1") (pin "14") (pinfunction "PF4_14") (pintype "bidirectional"))
    )
    (net (code "233") (name "unconnected-(D1C-PF5-Pad15)") (class "Default")
      (node (ref "D1") (pin "15") (pinfunction "PF5_15") (pintype "bidirectional"))
    )
    (net (code "234") (name "unconnected-(D1C-PF6-Pad18)") (class "Default")
      (node (ref "D1") (pin "18") (pinfunction "PF6_18") (pintype "bidirectional"))
    )
    (net (code "235") (name "unconnected-(D1C-PF7-Pad19)") (class "Default")
      (node (ref "D1") (pin "19") (pinfunction "PF7_19") (pintype "bidirectional"))
    )
    (net (code "236") (name "unconnected-(D1C-PF8-Pad20)") (class "Default")
      (node (ref "D1") (pin "20") (pinfunction "PF8_20") (pintype "bidirectional"))
    )
    (net (code "237") (name "unconnected-(D1C-PF9-Pad21)") (class "Default")
      (node (ref "D1") (pin "21") (pinfunction "PF9_21") (pintype "bidirectional"))
    )
    (net (code "238") (name "unconnected-(D1C-PF10-Pad22)") (class "Default")
      (node (ref "D1") (pin "22") (pinfunction "PF10_22") (pintype "bidirectional"))
    )
    (net (code "239") (name "unconnected-(D1C-PF11-Pad49)") (class "Default")
      (node (ref "D1") (pin "49") (pinfunction "PF11_49") (pintype "bidirectional"))
    )
    (net (code "240") (name "unconnected-(D1C-PF12-Pad50)") (class "Default")
      (node (ref "D1") (pin "50") (pinfunction "PF12_50") (pintype "bidirectional"))
    )
    (net (code "241") (name "unconnected-(D1C-PF13-Pad53)") (class "Default")
      (node (ref "D1") (pin "53") (pinfunction "PF13_53") (pintype "bidirectional"))
    )
    (net (code "242") (name "unconnected-(D1C-PF14-Pad54)") (class "Default")
      (node (ref "D1") (pin "54") (pinfunction "PF14_54") (pintype "bidirectional"))
    )
    (net (code "243") (name "unconnected-(D1C-PF15-Pad55)") (class "Default")
      (node (ref "D1") (pin "55") (pinfunction "PF15_55") (pintype "bidirectional"))
    )
    (net (code "244") (name "unconnected-(D1C-PG8-Pad93)") (class "Default")
      (node (ref "D1") (pin "93") (pinfunction "PG8_93") (pintype "bidirectional"))
    )
    (net (code "245") (name "unconnected-(D1C-PG10-Pad125)") (class "Default")
      (node (ref "D1") (pin "125") (pinfunction "PG10_125") (pintype "bidirectional"))
    )
    (net (code "246") (name "unconnected-(D1C-PG11-Pad126)") (class "Default")
      (node (ref "D1") (pin "126") (pinfunction "PG11_126") (pintype "bidirectional"))
    )
    (net (code "247") (name "unconnected-(D1C-PG12-Pad127)") (class "Default")
      (node (ref "D1") (pin "127") (pinfunction "PG12_127") (pintype "bidirectional"))
    )
    (net (code "248") (name "unconnected-(D1C-PG13-Pad128)") (class "Default")
      (node (ref "D1") (pin "128") (pinfunction "PG13_128") (pintype "bidirectional"))
    )
    (net (code "249") (name "unconnected-(D1C-PG14-Pad129)") (class "Default")
      (node (ref "D1") (pin "129") (pinfunction "PG14_129") (pintype "bidirectional"))
    )
    (net (code "250") (name "unconnected-(D1C-PG15-Pad132)") (class "Default")
      (node (ref "D1") (pin "132") (pinfunction "PG15_132") (pintype "bidirectional"))
    )
    (net (code "251") (name "unconnected-(D6-OS-Pad3)") (class "Default")
      (node (ref "D6") (pin "3") (pinfunction "OS_3") (pintype "bidirectional"))
    )
    (net (code "252") (name "unconnected-(D7-INT1-Pad7)") (class "Default")
      (node (ref "D7") (pin "7") (pinfunction "INT1_7") (pintype "bidirectional"))
    )
    (net (code "253") (name "unconnected-(D7-INT2-Pad3)") (class "Default")
      (node (ref "D7") (pin "3") (pinfunction "INT2_3") (pintype "bidirectional"))
    )
    (net (code "254") (name "unconnected-(D12E-Y-Pad10)") (class "Default")
      (node (ref "D12") (pin "10") (pinfunction "Y_10") (pintype "bidirectional"))
    )
    (net (code "255") (name "unconnected-(D12F-Y-Pad12)") (class "Default")
      (node (ref "D12") (pin "12") (pinfunction "Y_12") (pintype "bidirectional"))
    )
    (net (code "256") (name "unconnected-(N1-ENA-Pad5)") (class "Default")
      (node (ref "N1") (pin "5") (pinfunction "ENA_5") (pintype "bidirectional"))
    )
    (net (code "257") (name "unconnected-(N2-ENA-Pad5)") (class "Default")
      (node (ref "N2") (pin "5") (pinfunction "ENA_5") (pintype "bidirectional"))
    )
    (net (code "258") (name "unconnected-(V26-A-Pad1)") (class "Default")
      (node (ref "V26") (pin "1") (pinfunction "A_1") (pintype "bidirectional"))
    )
    (net (code "259") (name "unconnected-(V26-B-Pad6)") (class "Default")
      (node (ref "V26") (pin "6") (pinfunction "B_6") (pintype "bidirectional"))
    )
    (net (code "260") (name "unconnected-(V27-C-Pad1)") (class "Default")
      (node (ref "V27") (pin "1") (pinfunction "C_1") (pintype "passive"))
    )
    (net (code "261") (name "unconnected-(X1B-1-PadB1)") (class "Default")
      (node (ref "X1") (pin "B1") (pinfunction "1_B1") (pintype "passive"))
    )
    (net (code "262") (name "unconnected-(X8-ACK-Pad9)") (class "Default")
      (node (ref "X8") (pin "9") (pinfunction "ACK_9") (pintype "passive"))
    )
    (net (code "263") (name "unconnected-(X8-NC1-Pad3)") (class "Default")
      (node (ref "X8") (pin "3") (pinfunction "NC1_3") (pintype "passive"))
    )
    (net (code "264") (name "unconnected-(X8-NC2-Pad8)") (class "Default")
      (node (ref "X8") (pin "8") (pinfunction "NC2_8") (pintype "passive"))
    )
    (net (code "265") (name "unconnected-(X15-Pad1)") (class "Default")
      (node (ref "X15") (pin "1") (pinfunction "1_1") (pintype "passive"))
    )
    (net (code "266") (name "unconnected-(X15-Pad2)") (class "Default")
      (node (ref "X15") (pin "2") (pinfunction "2_2") (pintype "passive"))
    )
    (net (code "267") (name "unconnected-(X18-Pad4)") (class "Default")
      (node (ref "X18") (pin "4") (pinfunction "4_4") (pintype "passive"))
    )
  )
)
